# Module_AIO.net
KiCad netlist of a schematic drawn in EAGLE
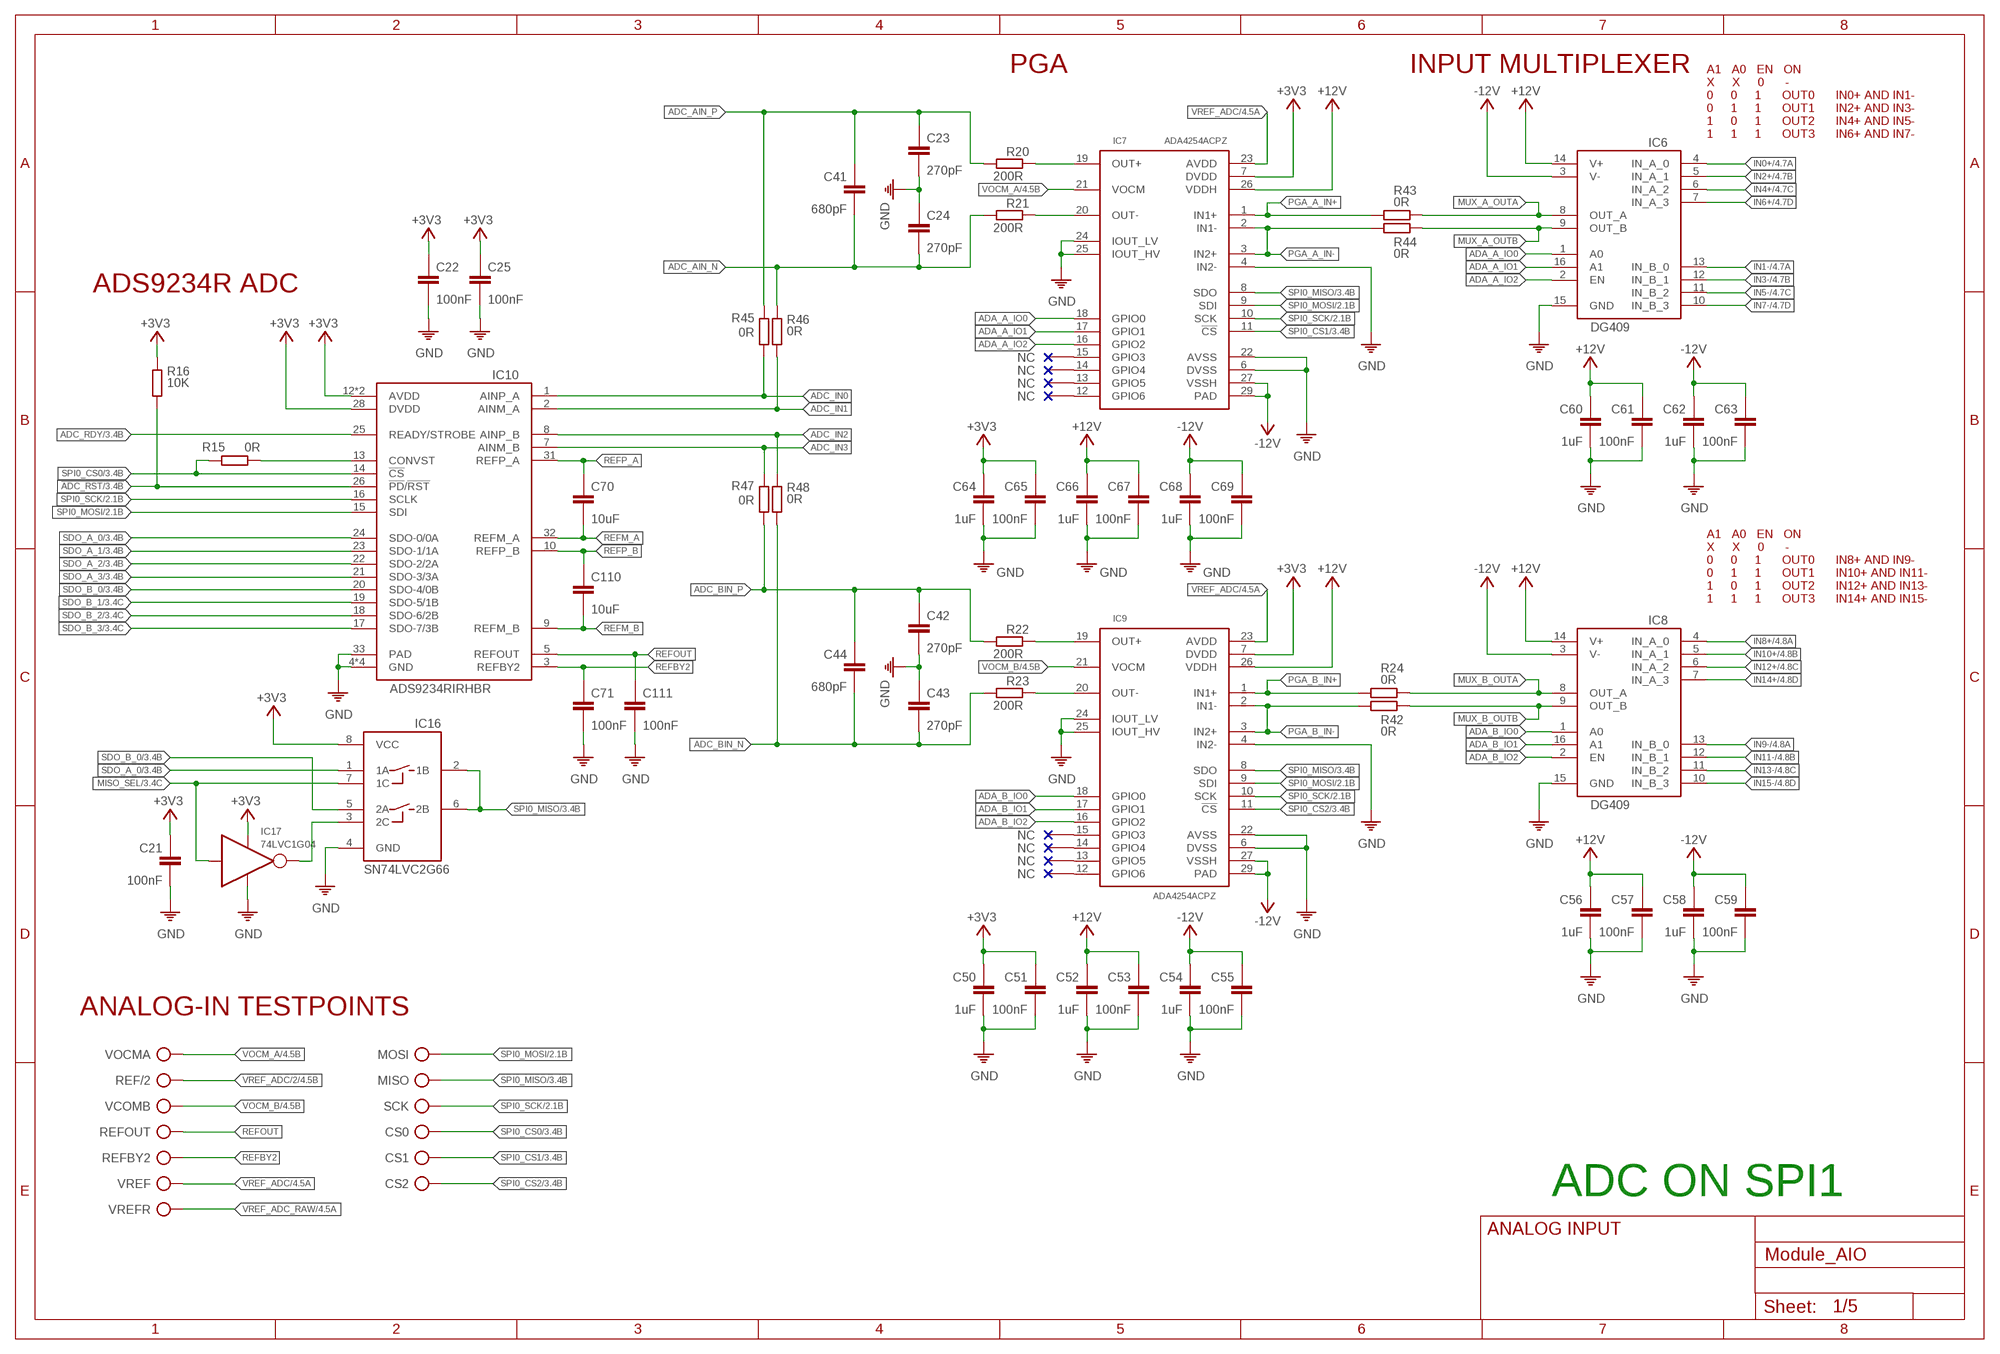
[diagram p0: schematic, sheet 1]
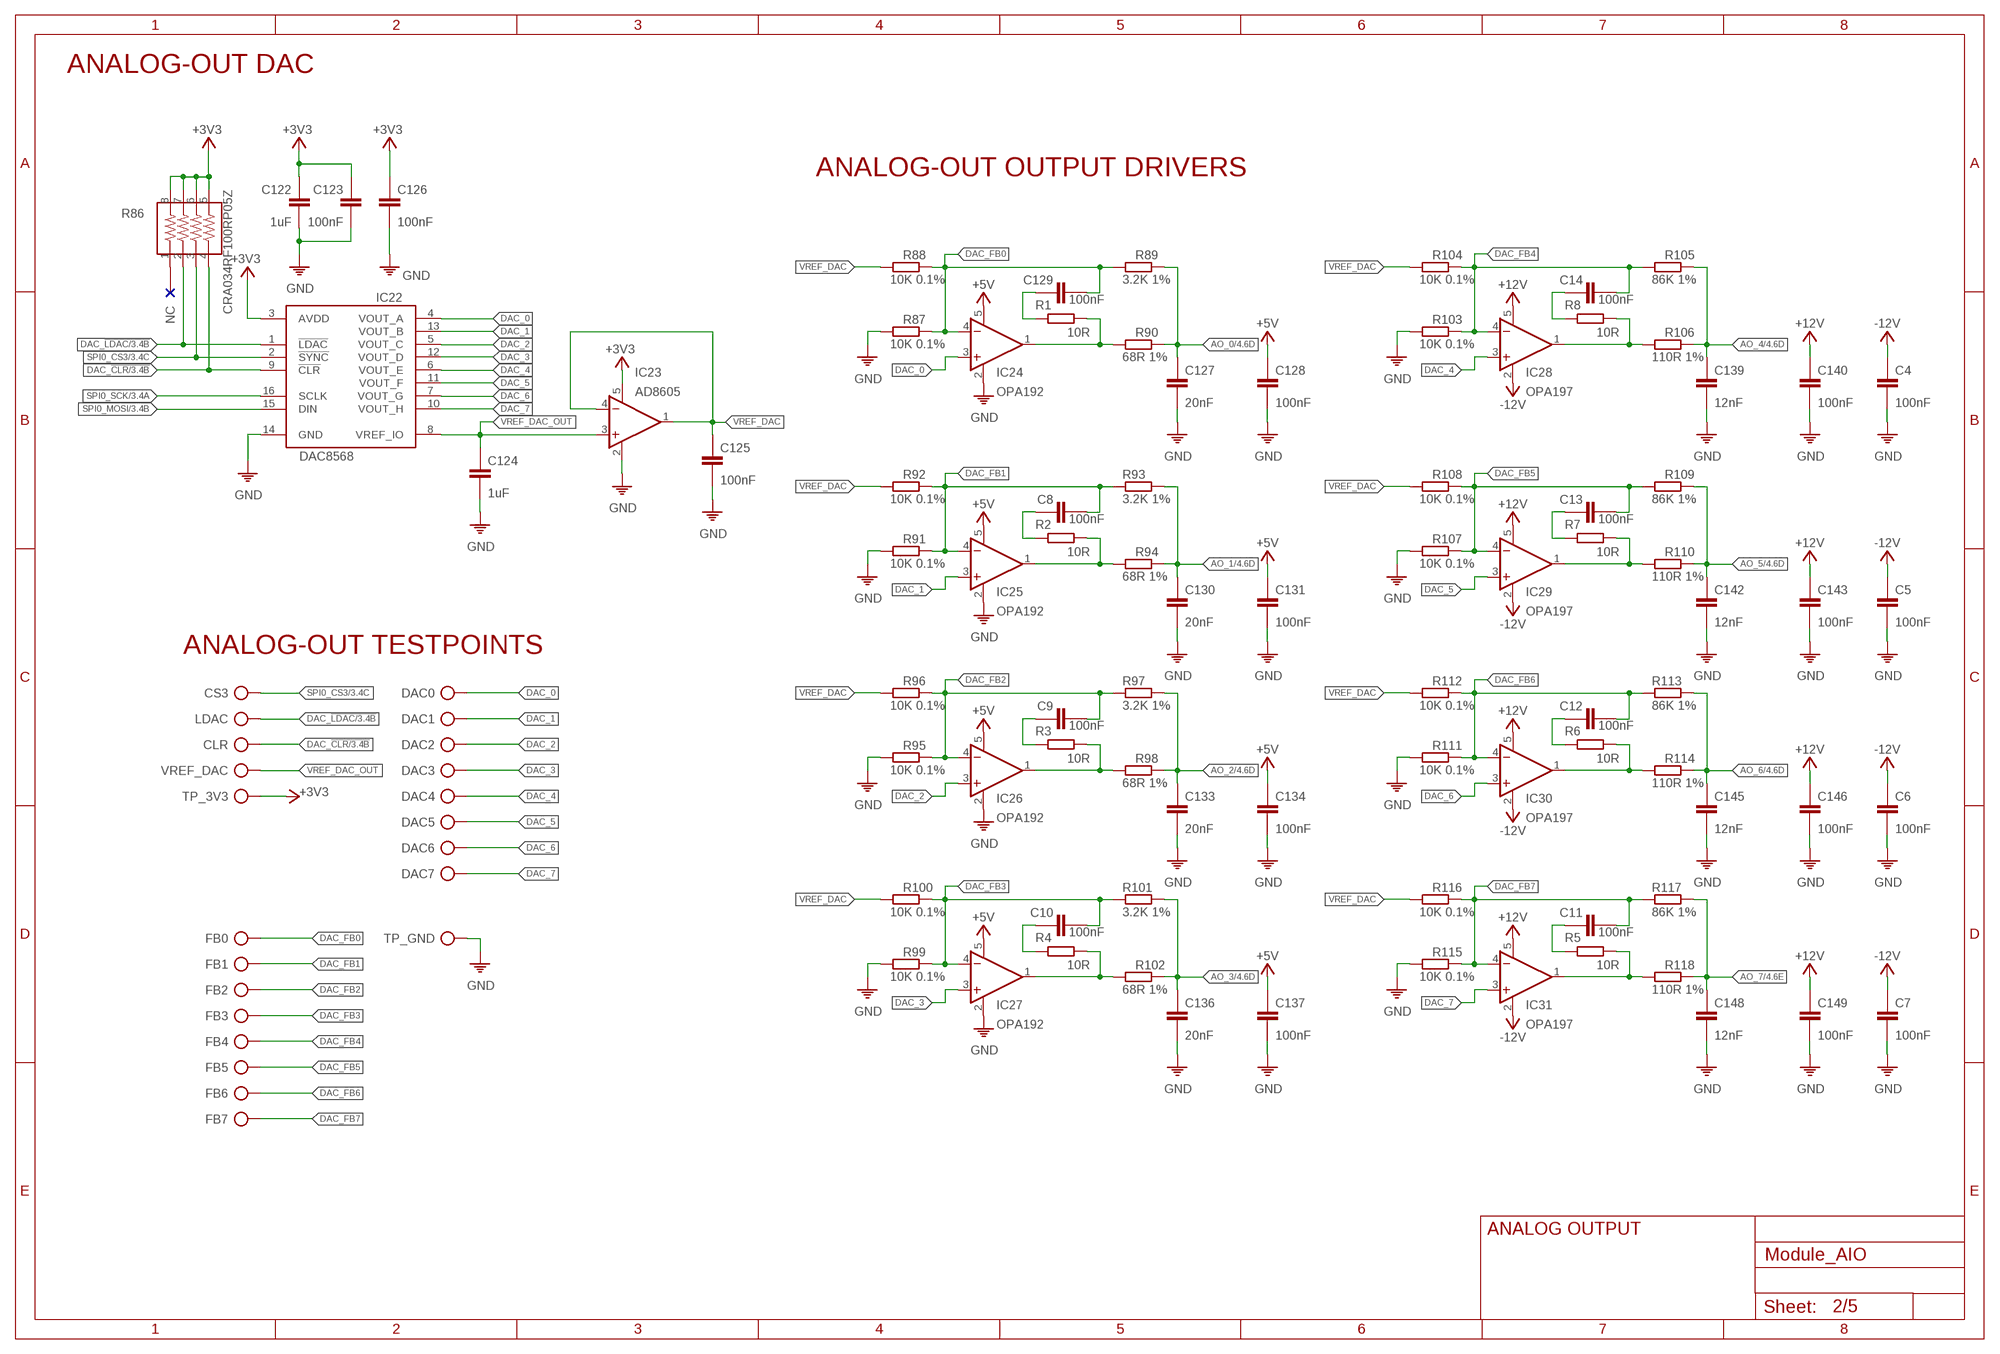
[diagram p1: schematic, sheet 2]
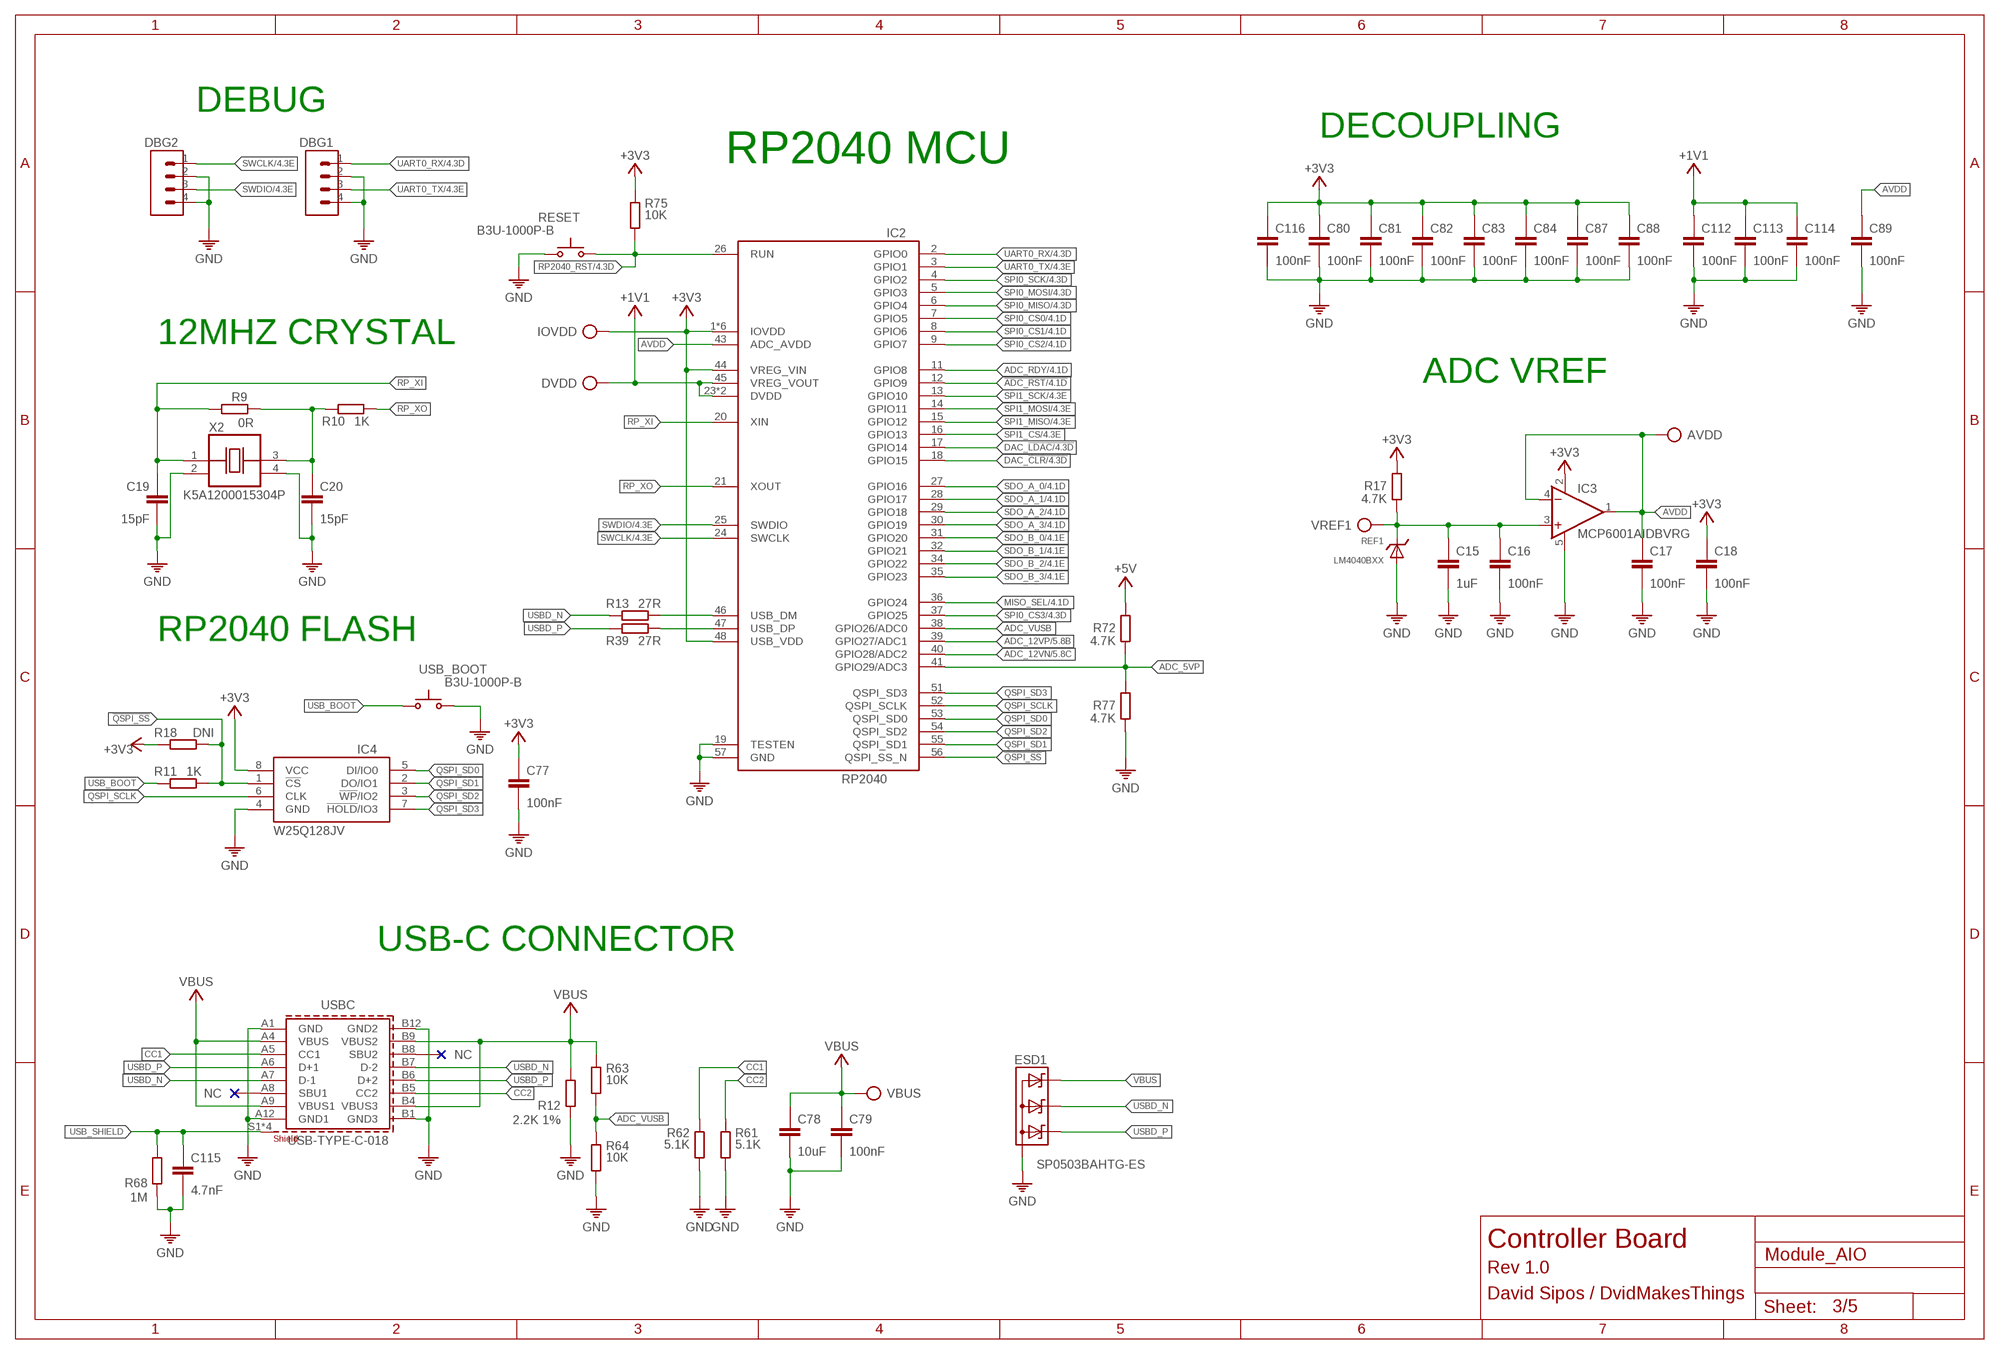
[diagram p2: schematic, sheet 3]
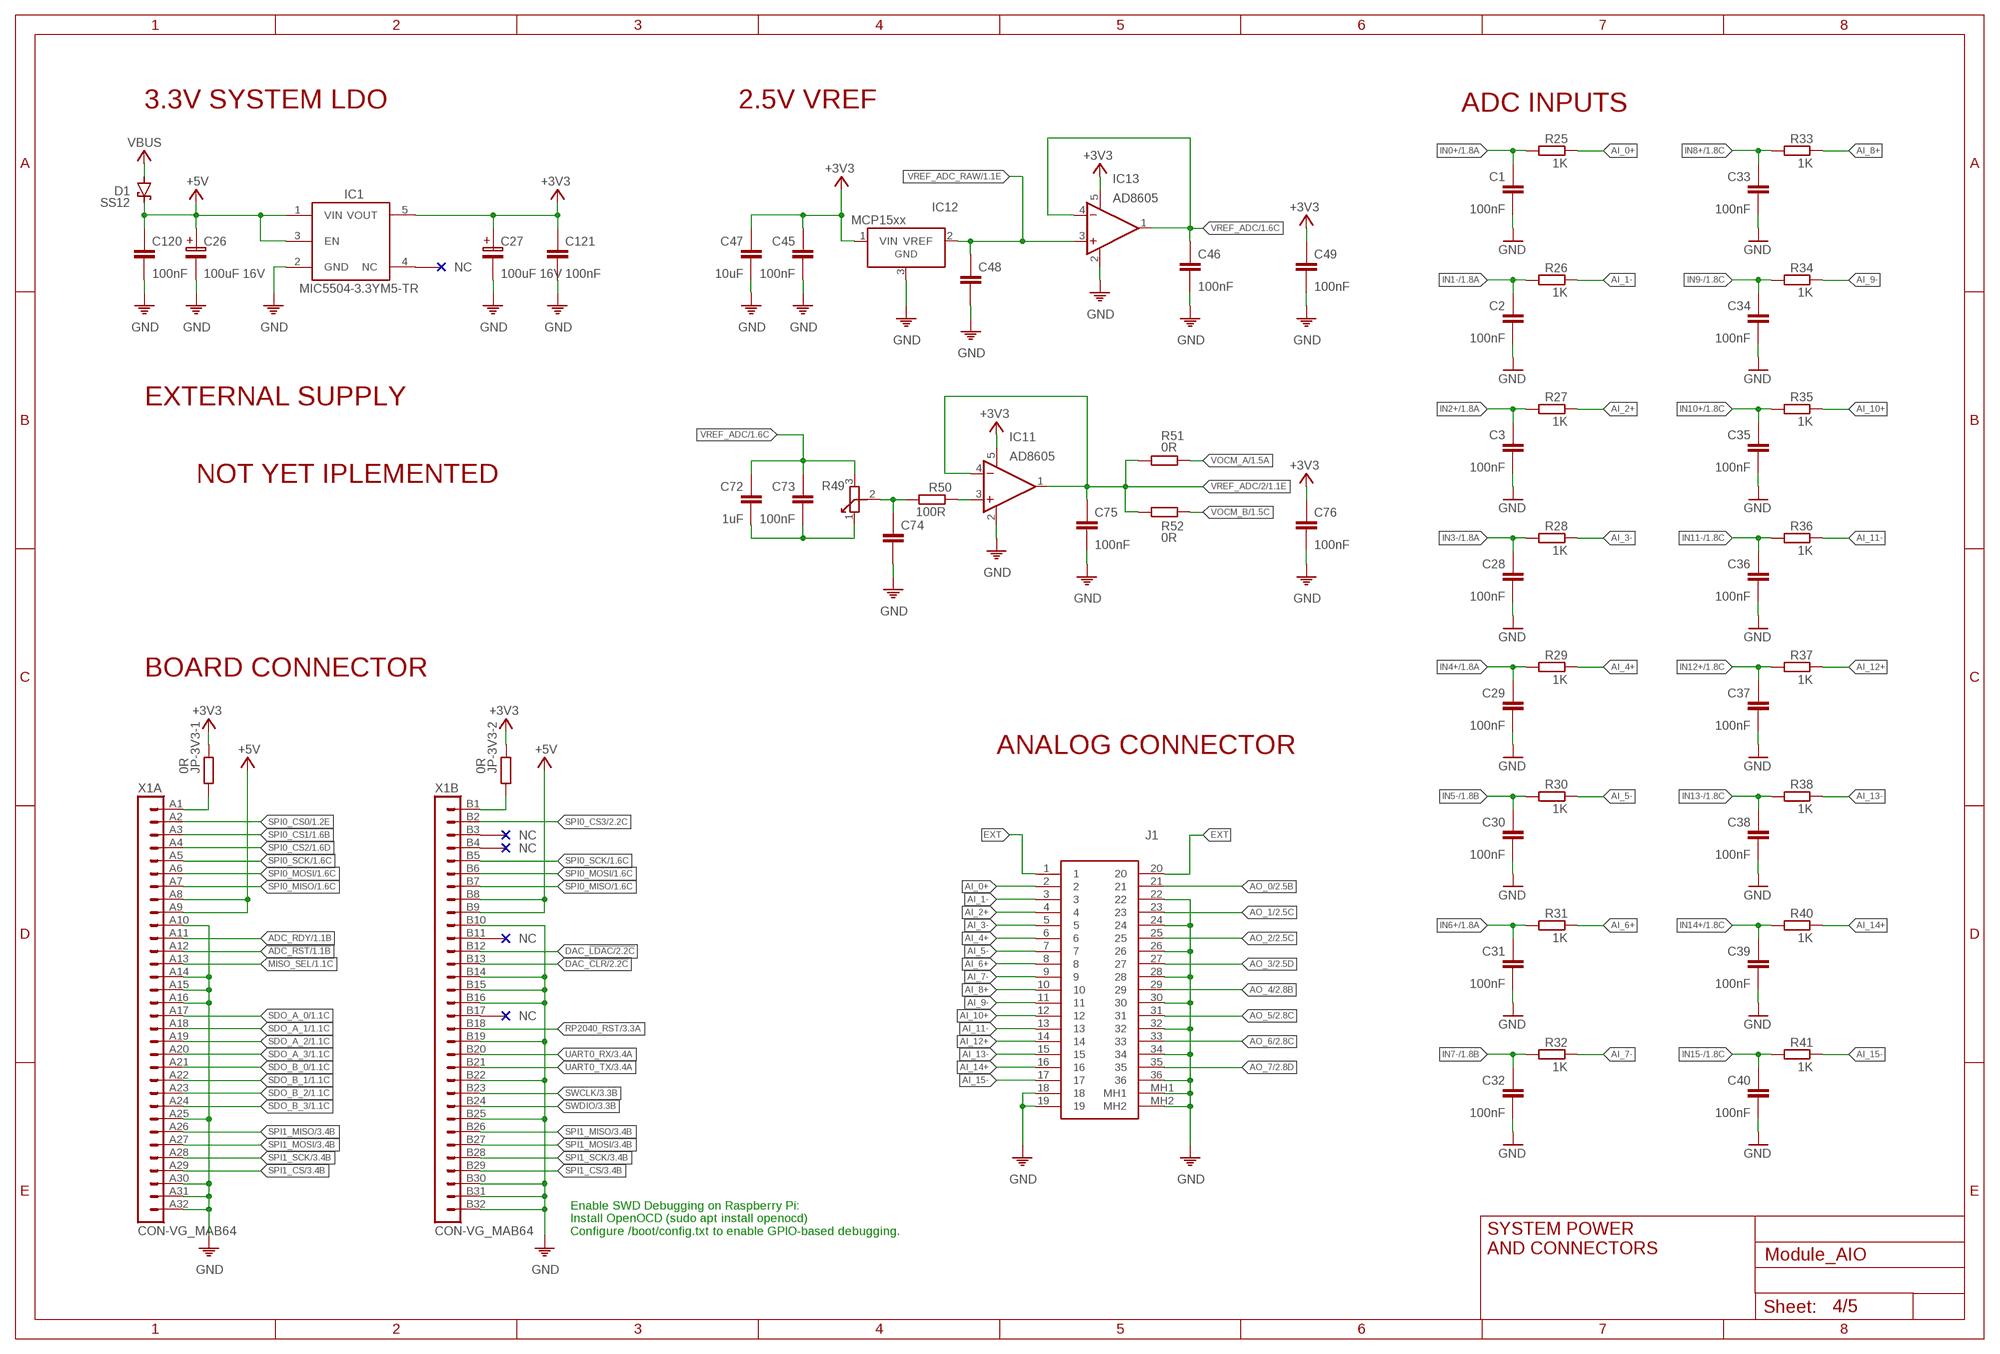
[diagram p3: schematic, sheet 4]
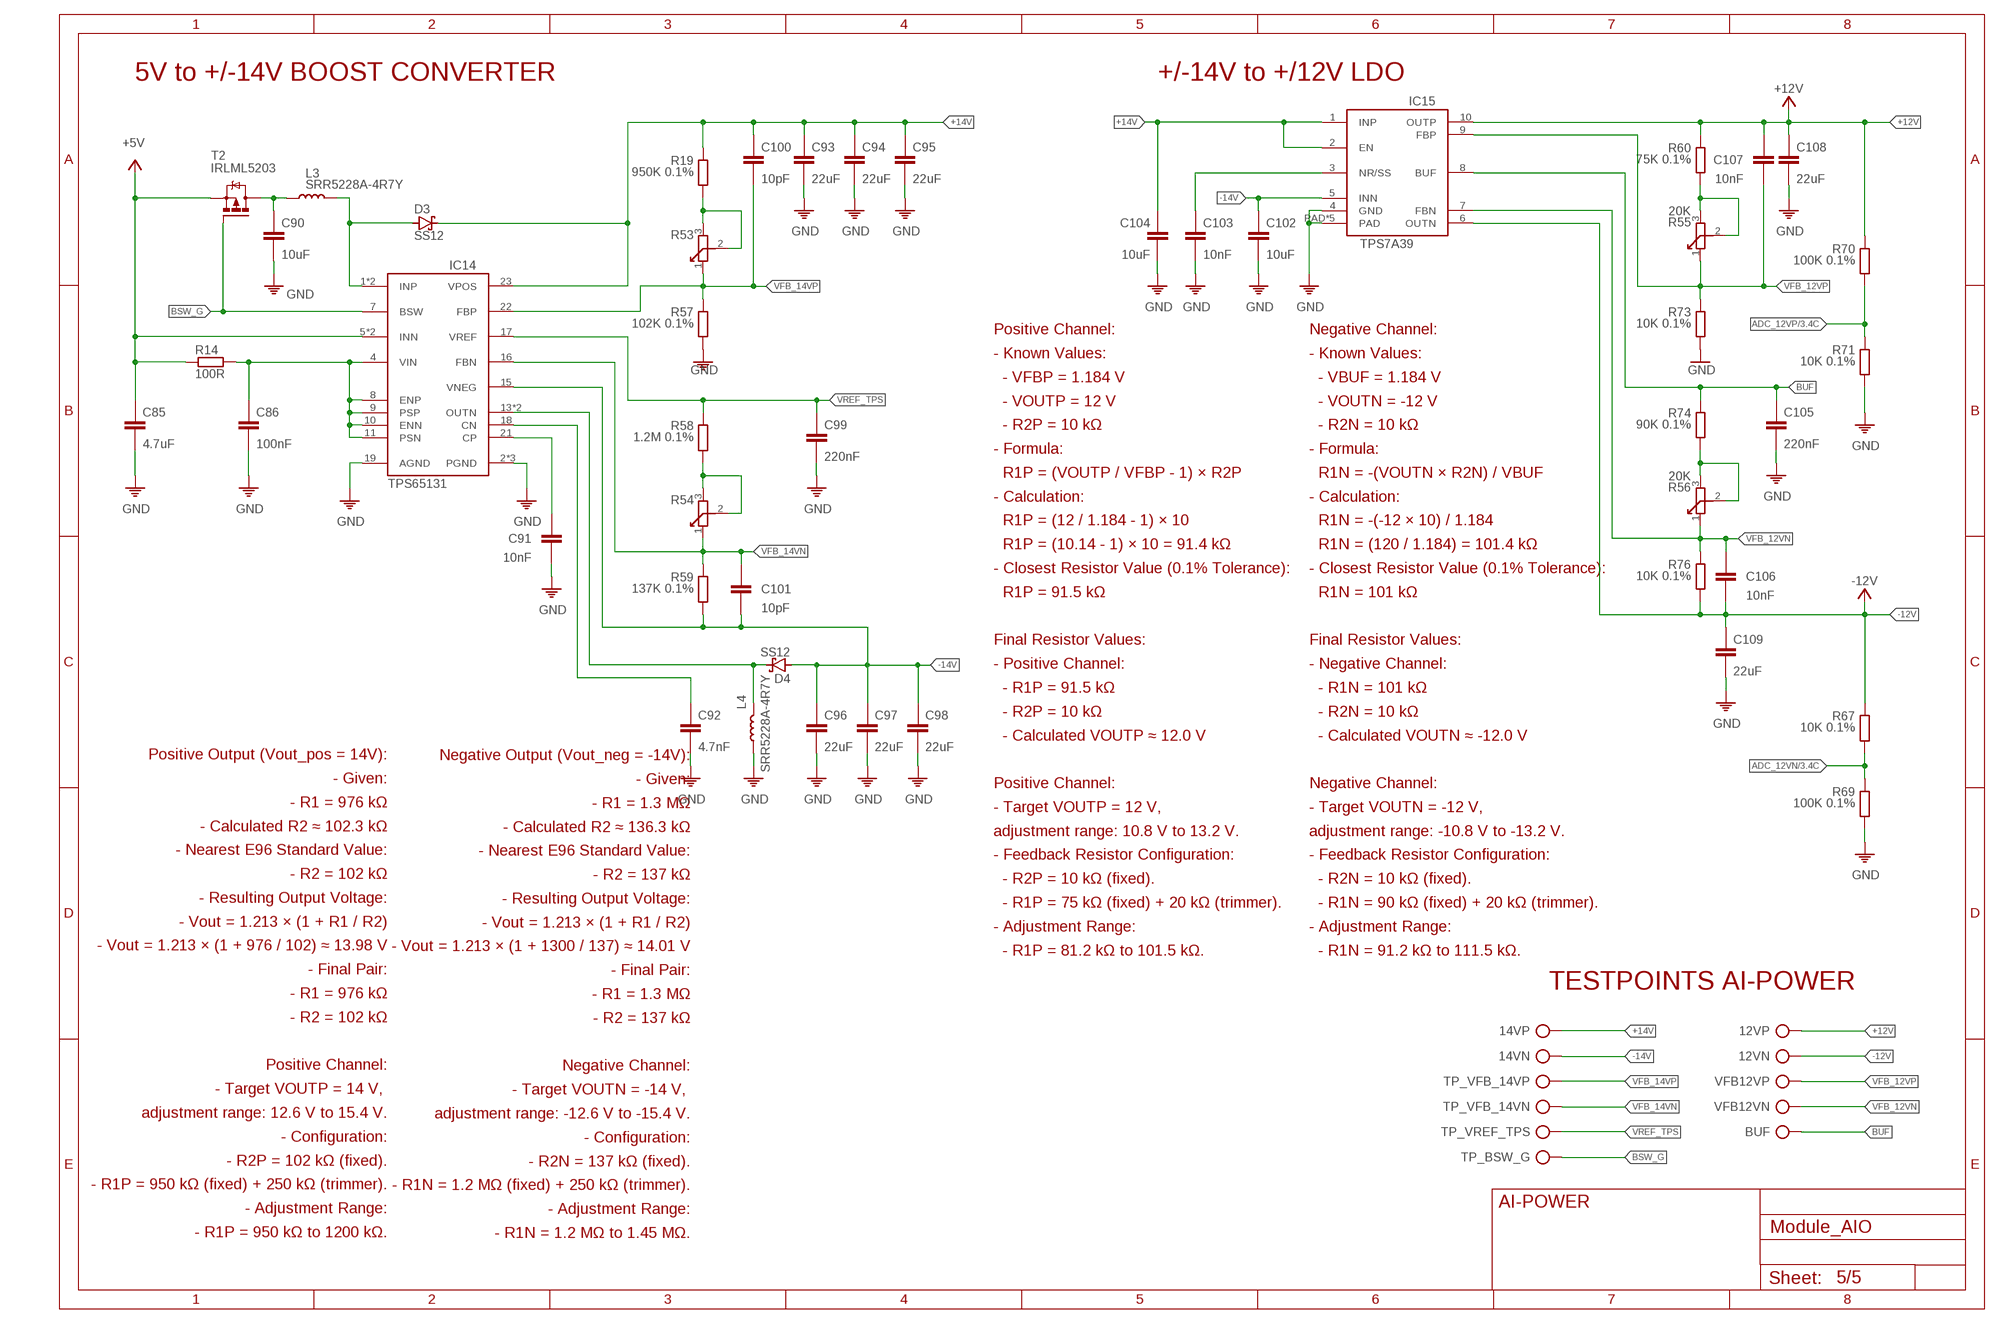
[diagram p4: schematic, sheet 5]

(export (version "E")
  (design (tool "Eeschema 10.0.6"))
  (components
    (comp (ref "C1")
      (value "100nF")
      (footprint "eagle-import:C0402")
      (libsource (lib "eagle-import") (part "C-0402"))
    )
    (comp (ref "C2")
      (value "100nF")
      (footprint "eagle-import:C0402")
      (libsource (lib "eagle-import") (part "C-0402"))
    )
    (comp (ref "C3")
      (value "100nF")
      (footprint "eagle-import:C0402")
      (libsource (lib "eagle-import") (part "C-0402"))
    )
    (comp (ref "C26")
      (value "100uF 16V")
      (footprint "eagle-import:100UF-16V")
      (libsource (lib "eagle-import") (part "CPOL"))
    )
    (comp (ref "C27")
      (value "100uF 16V")
      (footprint "eagle-import:100UF-16V")
      (libsource (lib "eagle-import") (part "CPOL"))
    )
    (comp (ref "C28")
      (value "100nF")
      (footprint "eagle-import:C0402")
      (libsource (lib "eagle-import") (part "C-0402"))
    )
    (comp (ref "C29")
      (value "100nF")
      (footprint "eagle-import:C0402")
      (libsource (lib "eagle-import") (part "C-0402"))
    )
    (comp (ref "C30")
      (value "100nF")
      (footprint "eagle-import:C0402")
      (libsource (lib "eagle-import") (part "C-0402"))
    )
    (comp (ref "C31")
      (value "100nF")
      (footprint "eagle-import:C0402")
      (libsource (lib "eagle-import") (part "C-0402"))
    )
    (comp (ref "C32")
      (value "100nF")
      (footprint "eagle-import:C0402")
      (libsource (lib "eagle-import") (part "C-0402"))
    )
    (comp (ref "C33")
      (value "100nF")
      (footprint "eagle-import:C0402")
      (libsource (lib "eagle-import") (part "C-0402"))
    )
    (comp (ref "C34")
      (value "100nF")
      (footprint "eagle-import:C0402")
      (libsource (lib "eagle-import") (part "C-0402"))
    )
    (comp (ref "C35")
      (value "100nF")
      (footprint "eagle-import:C0402")
      (libsource (lib "eagle-import") (part "C-0402"))
    )
    (comp (ref "C36")
      (value "100nF")
      (footprint "eagle-import:C0402")
      (libsource (lib "eagle-import") (part "C-0402"))
    )
    (comp (ref "C37")
      (value "100nF")
      (footprint "eagle-import:C0402")
      (libsource (lib "eagle-import") (part "C-0402"))
    )
    (comp (ref "C38")
      (value "100nF")
      (footprint "eagle-import:C0402")
      (libsource (lib "eagle-import") (part "C-0402"))
    )
    (comp (ref "C39")
      (value "100nF")
      (footprint "eagle-import:C0402")
      (libsource (lib "eagle-import") (part "C-0402"))
    )
    (comp (ref "C40")
      (value "100nF")
      (footprint "eagle-import:C0402")
      (libsource (lib "eagle-import") (part "C-0402"))
    )
    (comp (ref "C45")
      (value "100nF")
      (footprint "eagle-import:C0402")
      (libsource (lib "eagle-import") (part "C-0402"))
    )
    (comp (ref "C46")
      (value "100nF")
      (footprint "eagle-import:C0402")
      (libsource (lib "eagle-import") (part "C-0402"))
    )
    (comp (ref "C47")
      (value "10uF")
      (footprint "eagle-import:C0402")
      (libsource (lib "eagle-import") (part "C-0402"))
    )
    (comp (ref "C48")
      (value "C-0402")
      (footprint "eagle-import:C0402")
      (libsource (lib "eagle-import") (part "C-0402"))
    )
    (comp (ref "C49")
      (value "100nF")
      (footprint "eagle-import:C0402")
      (libsource (lib "eagle-import") (part "C-0402"))
    )
    (comp (ref "C72")
      (value "1uF")
      (footprint "eagle-import:C0402")
      (libsource (lib "eagle-import") (part "C-0402"))
    )
    (comp (ref "C73")
      (value "100nF")
      (footprint "eagle-import:C0402")
      (libsource (lib "eagle-import") (part "C-0402"))
    )
    (comp (ref "C74")
      (value "C-0402")
      (footprint "eagle-import:C0402")
      (libsource (lib "eagle-import") (part "C-0402"))
    )
    (comp (ref "C75")
      (value "100nF")
      (footprint "eagle-import:C0402")
      (libsource (lib "eagle-import") (part "C-0402"))
    )
    (comp (ref "C76")
      (value "100nF")
      (footprint "eagle-import:C0402")
      (libsource (lib "eagle-import") (part "C-0402"))
    )
    (comp (ref "C120")
      (value "100nF")
      (footprint "eagle-import:C0402")
      (libsource (lib "eagle-import") (part "C-0402"))
    )
    (comp (ref "C121")
      (value "100nF")
      (footprint "eagle-import:C0402")
      (libsource (lib "eagle-import") (part "C-0402"))
    )
    (comp (ref "D1")
      (value "SS12")
      (footprint "eagle-import:SMA")
      (fields
        (field (name "DIGIKEY_PART_NUMBER") "SS12FSCT-ND")
        (field (name "MANUFACTURER") "ON Semiconductor")
        (field (name "CREATED_BY") "PCBLayout.com")
      )
      (libsource (lib "eagle-import") (part "SS12"))
    )
    (comp (ref "IC1")
      (value "MIC5504-3.3YM5-TR")
      (footprint "eagle-import:SOT23-5")
      (libsource (lib "eagle-import") (part "MIC5504-3.3YM5-TR"))
    )
    (comp (ref "IC11")
      (value "AD8605")
      (footprint "eagle-import:SOT23-5")
      (libsource (lib "eagle-import") (part "AD8605"))
    )
    (comp (ref "IC12")
      (value "MCP1525T-I/TT")
      (footprint "eagle-import:SOT23")
      (libsource (lib "eagle-import") (part "MCP1525T-I/TT"))
    )
    (comp (ref "IC13")
      (value "AD8605")
      (footprint "eagle-import:SOT23-5")
      (libsource (lib "eagle-import") (part "AD8605"))
    )
    (comp (ref "J1")
      (value "N10236-52B3PC")
      (footprint "eagle-import:MDB36")
      (libsource (lib "eagle-import") (part "N10236-52B3PC"))
    )
    (comp (ref "JP-3V3-1")
      (value "0R")
      (footprint "eagle-import:0603")
      (libsource (lib "eagle-import") (part "R0603"))
    )
    (comp (ref "JP-3V3-2")
      (value "0R")
      (footprint "eagle-import:0603")
      (libsource (lib "eagle-import") (part "R0603"))
    )
    (comp (ref "R25")
      (value "1K")
      (footprint "eagle-import:0402")
      (libsource (lib "eagle-import") (part "R0402"))
    )
    (comp (ref "R26")
      (value "1K")
      (footprint "eagle-import:0402")
      (libsource (lib "eagle-import") (part "R0402"))
    )
    (comp (ref "R27")
      (value "1K")
      (footprint "eagle-import:0402")
      (libsource (lib "eagle-import") (part "R0402"))
    )
    (comp (ref "R28")
      (value "1K")
      (footprint "eagle-import:0402")
      (libsource (lib "eagle-import") (part "R0402"))
    )
    (comp (ref "R29")
      (value "1K")
      (footprint "eagle-import:0402")
      (libsource (lib "eagle-import") (part "R0402"))
    )
    (comp (ref "R30")
      (value "1K")
      (footprint "eagle-import:0402")
      (libsource (lib "eagle-import") (part "R0402"))
    )
    (comp (ref "R31")
      (value "1K")
      (footprint "eagle-import:0402")
      (libsource (lib "eagle-import") (part "R0402"))
    )
    (comp (ref "R32")
      (value "1K")
      (footprint "eagle-import:0402")
      (libsource (lib "eagle-import") (part "R0402"))
    )
    (comp (ref "R33")
      (value "1K")
      (footprint "eagle-import:0402")
      (libsource (lib "eagle-import") (part "R0402"))
    )
    (comp (ref "R34")
      (value "1K")
      (footprint "eagle-import:0402")
      (libsource (lib "eagle-import") (part "R0402"))
    )
    (comp (ref "R35")
      (value "1K")
      (footprint "eagle-import:0402")
      (libsource (lib "eagle-import") (part "R0402"))
    )
    (comp (ref "R36")
      (value "1K")
      (footprint "eagle-import:0402")
      (libsource (lib "eagle-import") (part "R0402"))
    )
    (comp (ref "R37")
      (value "1K")
      (footprint "eagle-import:0402")
      (libsource (lib "eagle-import") (part "R0402"))
    )
    (comp (ref "R38")
      (value "1K")
      (footprint "eagle-import:0402")
      (libsource (lib "eagle-import") (part "R0402"))
    )
    (comp (ref "R40")
      (value "1K")
      (footprint "eagle-import:0402")
      (libsource (lib "eagle-import") (part "R0402"))
    )
    (comp (ref "R41")
      (value "1K")
      (footprint "eagle-import:0402")
      (libsource (lib "eagle-import") (part "R0402"))
    )
    (comp (ref "R49")
      (value "R-TRIM")
      (footprint "eagle-import:TC33X")
      (libsource (lib "eagle-import") (part "R-TRIM"))
    )
    (comp (ref "R50")
      (value "100R")
      (footprint "eagle-import:0402")
      (libsource (lib "eagle-import") (part "R0402"))
    )
    (comp (ref "R51")
      (value "0R")
      (footprint "eagle-import:0603")
      (libsource (lib "eagle-import") (part "R0603"))
    )
    (comp (ref "R52")
      (value "0R")
      (footprint "eagle-import:0603")
      (libsource (lib "eagle-import") (part "R0603"))
    )
    (comp (ref "X1")
      (value "CON-VG_MAB64")
      (footprint "eagle-import:CON-VG_MAB64")
      (libsource (lib "eagle-import") (part "CON-VG_MAB64"))
    )
    (comp (ref "C21")
      (value "100nF")
      (footprint "eagle-import:C0402")
      (libsource (lib "eagle-import") (part "C-0402"))
    )
    (comp (ref "C22")
      (value "100nF")
      (footprint "eagle-import:C0402")
      (libsource (lib "eagle-import") (part "C-0402"))
    )
    (comp (ref "C23")
      (value "270pF")
      (footprint "eagle-import:C0402")
      (libsource (lib "eagle-import") (part "C-0402"))
    )
    (comp (ref "C24")
      (value "270pF")
      (footprint "eagle-import:C0402")
      (libsource (lib "eagle-import") (part "C-0402"))
    )
    (comp (ref "C25")
      (value "100nF")
      (footprint "eagle-import:C0402")
      (libsource (lib "eagle-import") (part "C-0402"))
    )
    (comp (ref "C41")
      (value "680pF")
      (footprint "eagle-import:C0402")
      (libsource (lib "eagle-import") (part "C-0402"))
    )
    (comp (ref "C42")
      (value "270pF")
      (footprint "eagle-import:C0402")
      (libsource (lib "eagle-import") (part "C-0402"))
    )
    (comp (ref "C43")
      (value "270pF")
      (footprint "eagle-import:C0402")
      (libsource (lib "eagle-import") (part "C-0402"))
    )
    (comp (ref "C44")
      (value "680pF")
      (footprint "eagle-import:C0402")
      (libsource (lib "eagle-import") (part "C-0402"))
    )
    (comp (ref "C50")
      (value "1uF")
      (footprint "eagle-import:C0402")
      (libsource (lib "eagle-import") (part "C-0402"))
    )
    (comp (ref "C51")
      (value "100nF")
      (footprint "eagle-import:C0402")
      (libsource (lib "eagle-import") (part "C-0402"))
    )
    (comp (ref "C52")
      (value "1uF")
      (footprint "eagle-import:C0402")
      (libsource (lib "eagle-import") (part "C-0402"))
    )
    (comp (ref "C53")
      (value "100nF")
      (footprint "eagle-import:C0402")
      (libsource (lib "eagle-import") (part "C-0402"))
    )
    (comp (ref "C54")
      (value "1uF")
      (footprint "eagle-import:C0402")
      (libsource (lib "eagle-import") (part "C-0402"))
    )
    (comp (ref "C55")
      (value "100nF")
      (footprint "eagle-import:C0402")
      (libsource (lib "eagle-import") (part "C-0402"))
    )
    (comp (ref "C56")
      (value "1uF")
      (footprint "eagle-import:C0402")
      (libsource (lib "eagle-import") (part "C-0402"))
    )
    (comp (ref "C57")
      (value "100nF")
      (footprint "eagle-import:C0402")
      (libsource (lib "eagle-import") (part "C-0402"))
    )
    (comp (ref "C58")
      (value "1uF")
      (footprint "eagle-import:C0402")
      (libsource (lib "eagle-import") (part "C-0402"))
    )
    (comp (ref "C59")
      (value "100nF")
      (footprint "eagle-import:C0402")
      (libsource (lib "eagle-import") (part "C-0402"))
    )
    (comp (ref "C60")
      (value "1uF")
      (footprint "eagle-import:C0402")
      (libsource (lib "eagle-import") (part "C-0402"))
    )
    (comp (ref "C61")
      (value "100nF")
      (footprint "eagle-import:C0402")
      (libsource (lib "eagle-import") (part "C-0402"))
    )
    (comp (ref "C62")
      (value "1uF")
      (footprint "eagle-import:C0402")
      (libsource (lib "eagle-import") (part "C-0402"))
    )
    (comp (ref "C63")
      (value "100nF")
      (footprint "eagle-import:C0402")
      (libsource (lib "eagle-import") (part "C-0402"))
    )
    (comp (ref "C64")
      (value "1uF")
      (footprint "eagle-import:C0402")
      (libsource (lib "eagle-import") (part "C-0402"))
    )
    (comp (ref "C65")
      (value "100nF")
      (footprint "eagle-import:C0402")
      (libsource (lib "eagle-import") (part "C-0402"))
    )
    (comp (ref "C66")
      (value "1uF")
      (footprint "eagle-import:C0402")
      (libsource (lib "eagle-import") (part "C-0402"))
    )
    (comp (ref "C67")
      (value "100nF")
      (footprint "eagle-import:C0402")
      (libsource (lib "eagle-import") (part "C-0402"))
    )
    (comp (ref "C68")
      (value "1uF")
      (footprint "eagle-import:C0402")
      (libsource (lib "eagle-import") (part "C-0402"))
    )
    (comp (ref "C69")
      (value "100nF")
      (footprint "eagle-import:C0402")
      (libsource (lib "eagle-import") (part "C-0402"))
    )
    (comp (ref "C70")
      (value "10uF")
      (footprint "eagle-import:C0402")
      (libsource (lib "eagle-import") (part "C-0402"))
    )
    (comp (ref "C71")
      (value "100nF")
      (footprint "eagle-import:C0402")
      (libsource (lib "eagle-import") (part "C-0402"))
    )
    (comp (ref "C110")
      (value "10uF")
      (footprint "eagle-import:C0402")
      (libsource (lib "eagle-import") (part "C-0402"))
    )
    (comp (ref "C111")
      (value "100nF")
      (footprint "eagle-import:C0402")
      (libsource (lib "eagle-import") (part "C-0402"))
    )
    (comp (ref "CS0") (value "TP") (footprint "eagle-import:TP") (libsource (lib "eagle-import") (part "TP")))
    (comp (ref "CS1") (value "TP") (footprint "eagle-import:TP") (libsource (lib "eagle-import") (part "TP")))
    (comp (ref "CS2") (value "TP") (footprint "eagle-import:TP") (libsource (lib "eagle-import") (part "TP")))
    (comp (ref "IC6")
      (value "DG409")
      (footprint "eagle-import:TSSOP2")
      (libsource (lib "eagle-import") (part "DG409EUE+"))
    )
    (comp (ref "IC7")
      (value "ADA4254ACPZ")
      (footprint "eagle-import:QFN50P500X500X75-29T314N")
      (libsource (lib "eagle-import") (part "ADA4254ACPZ"))
    )
    (comp (ref "IC8")
      (value "DG409")
      (footprint "eagle-import:TSSOP2")
      (libsource (lib "eagle-import") (part "DG409EUE+"))
    )
    (comp (ref "IC9")
      (value "ADA4254ACPZ")
      (footprint "eagle-import:QFN50P500X500X75-29T314N")
      (libsource (lib "eagle-import") (part "ADA4254ACPZ"))
    )
    (comp (ref "IC10")
      (value "ADS9234RIRHBR")
      (footprint "eagle-import:VQFN32-5X5")
      (libsource (lib "eagle-import") (part "ADS9234RIRHBR"))
    )
    (comp (ref "IC16")
      (value "SN74LVC2G66")
      (footprint "eagle-import:SOP50P310X90-8N")
      (libsource (lib "eagle-import") (part "SN74LVC2G66"))
    )
    (comp (ref "IC17")
      (value "74LVC1G04")
      (footprint "eagle-import:SOT95P280X145-5N")
      (libsource (lib "eagle-import") (part "74LVC1G04"))
    )
    (comp (ref "MISO")
      (value "TP")
      (footprint "eagle-import:TP")
      (libsource (lib "eagle-import") (part "TP"))
    )
    (comp (ref "MOSI")
      (value "TP")
      (footprint "eagle-import:TP")
      (libsource (lib "eagle-import") (part "TP"))
    )
    (comp (ref "R15")
      (value "0R")
      (footprint "eagle-import:0402")
      (libsource (lib "eagle-import") (part "R0402"))
    )
    (comp (ref "R16")
      (value "10K")
      (footprint "eagle-import:0402")
      (libsource (lib "eagle-import") (part "R0402"))
    )
    (comp (ref "R20")
      (value "200R")
      (footprint "eagle-import:0402")
      (libsource (lib "eagle-import") (part "R0402"))
    )
    (comp (ref "R21")
      (value "200R")
      (footprint "eagle-import:0402")
      (libsource (lib "eagle-import") (part "R0402"))
    )
    (comp (ref "R22")
      (value "200R")
      (footprint "eagle-import:0402")
      (libsource (lib "eagle-import") (part "R0402"))
    )
    (comp (ref "R23")
      (value "200R")
      (footprint "eagle-import:0402")
      (libsource (lib "eagle-import") (part "R0402"))
    )
    (comp (ref "R24")
      (value "0R")
      (footprint "eagle-import:0402")
      (libsource (lib "eagle-import") (part "R0402"))
    )
    (comp (ref "R42")
      (value "0R")
      (footprint "eagle-import:0402")
      (libsource (lib "eagle-import") (part "R0402"))
    )
    (comp (ref "R43")
      (value "0R")
      (footprint "eagle-import:0402")
      (libsource (lib "eagle-import") (part "R0402"))
    )
    (comp (ref "R44")
      (value "0R")
      (footprint "eagle-import:0402")
      (libsource (lib "eagle-import") (part "R0402"))
    )
    (comp (ref "R45")
      (value "0R")
      (footprint "eagle-import:0402")
      (libsource (lib "eagle-import") (part "R0402"))
    )
    (comp (ref "R46")
      (value "0R")
      (footprint "eagle-import:0402")
      (libsource (lib "eagle-import") (part "R0402"))
    )
    (comp (ref "R47")
      (value "0R")
      (footprint "eagle-import:0402")
      (libsource (lib "eagle-import") (part "R0402"))
    )
    (comp (ref "R48")
      (value "0R")
      (footprint "eagle-import:0402")
      (libsource (lib "eagle-import") (part "R0402"))
    )
    (comp (ref "REF/2")
      (value "TP")
      (footprint "eagle-import:TP")
      (libsource (lib "eagle-import") (part "TP"))
    )
    (comp (ref "REFBY2")
      (value "TP")
      (footprint "eagle-import:TP")
      (libsource (lib "eagle-import") (part "TP"))
    )
    (comp (ref "REFOUT")
      (value "TP")
      (footprint "eagle-import:TP")
      (libsource (lib "eagle-import") (part "TP"))
    )
    (comp (ref "SCK") (value "TP") (footprint "eagle-import:TP") (libsource (lib "eagle-import") (part "TP")))
    (comp (ref "VCOMB")
      (value "TP")
      (footprint "eagle-import:TP")
      (libsource (lib "eagle-import") (part "TP"))
    )
    (comp (ref "VOCMA")
      (value "TP")
      (footprint "eagle-import:TP")
      (libsource (lib "eagle-import") (part "TP"))
    )
    (comp (ref "VREF")
      (value "TP")
      (footprint "eagle-import:TP")
      (libsource (lib "eagle-import") (part "TP"))
    )
    (comp (ref "VREFR")
      (value "TP")
      (footprint "eagle-import:TP")
      (libsource (lib "eagle-import") (part "TP"))
    )
    (comp (ref "AVDD")
      (value "TP")
      (footprint "eagle-import:TP")
      (libsource (lib "eagle-import") (part "TP"))
    )
    (comp (ref "C15")
      (value "1uF")
      (footprint "eagle-import:C0402")
      (libsource (lib "eagle-import") (part "C-0402"))
    )
    (comp (ref "C16")
      (value "100nF")
      (footprint "eagle-import:C0402")
      (libsource (lib "eagle-import") (part "C-0402"))
    )
    (comp (ref "C17")
      (value "100nF")
      (footprint "eagle-import:C0402")
      (libsource (lib "eagle-import") (part "C-0402"))
    )
    (comp (ref "C18")
      (value "100nF")
      (footprint "eagle-import:C0402")
      (libsource (lib "eagle-import") (part "C-0402"))
    )
    (comp (ref "C19")
      (value "15pF")
      (footprint "eagle-import:C0402")
      (libsource (lib "eagle-import") (part "C-0402"))
    )
    (comp (ref "C20")
      (value "15pF")
      (footprint "eagle-import:C0402")
      (libsource (lib "eagle-import") (part "C-0402"))
    )
    (comp (ref "C77")
      (value "100nF")
      (footprint "eagle-import:C0402")
      (libsource (lib "eagle-import") (part "C-0402"))
    )
    (comp (ref "C78")
      (value "10uF")
      (footprint "eagle-import:0805")
      (libsource (lib "eagle-import") (part "C0805"))
    )
    (comp (ref "C79")
      (value "100nF")
      (footprint "eagle-import:0402")
      (libsource (lib "eagle-import") (part "C0402"))
    )
    (comp (ref "C80")
      (value "100nF")
      (footprint "eagle-import:C0402")
      (libsource (lib "eagle-import") (part "C-0402"))
    )
    (comp (ref "C81")
      (value "100nF")
      (footprint "eagle-import:C0402")
      (libsource (lib "eagle-import") (part "C-0402"))
    )
    (comp (ref "C82")
      (value "100nF")
      (footprint "eagle-import:C0402")
      (libsource (lib "eagle-import") (part "C-0402"))
    )
    (comp (ref "C83")
      (value "100nF")
      (footprint "eagle-import:C0402")
      (libsource (lib "eagle-import") (part "C-0402"))
    )
    (comp (ref "C84")
      (value "100nF")
      (footprint "eagle-import:C0402")
      (libsource (lib "eagle-import") (part "C-0402"))
    )
    (comp (ref "C87")
      (value "100nF")
      (footprint "eagle-import:C0402")
      (libsource (lib "eagle-import") (part "C-0402"))
    )
    (comp (ref "C88")
      (value "100nF")
      (footprint "eagle-import:C0402")
      (libsource (lib "eagle-import") (part "C-0402"))
    )
    (comp (ref "C89")
      (value "100nF")
      (footprint "eagle-import:C0402")
      (libsource (lib "eagle-import") (part "C-0402"))
    )
    (comp (ref "C112")
      (value "100nF")
      (footprint "eagle-import:C0402")
      (libsource (lib "eagle-import") (part "C-0402"))
    )
    (comp (ref "C113")
      (value "100nF")
      (footprint "eagle-import:C0402")
      (libsource (lib "eagle-import") (part "C-0402"))
    )
    (comp (ref "C114")
      (value "100nF")
      (footprint "eagle-import:C0402")
      (libsource (lib "eagle-import") (part "C-0402"))
    )
    (comp (ref "C115")
      (value "4.7nF")
      (footprint "eagle-import:0402")
      (libsource (lib "eagle-import") (part "C0402"))
    )
    (comp (ref "C116")
      (value "100nF")
      (footprint "eagle-import:C0402")
      (libsource (lib "eagle-import") (part "C-0402"))
    )
    (comp (ref "DBG1")
      (value "CON-1X4")
      (footprint "eagle-import:1X4")
      (libsource (lib "eagle-import") (part "CON-1X4"))
    )
    (comp (ref "DBG2")
      (value "CON-1X4")
      (footprint "eagle-import:1X4")
      (libsource (lib "eagle-import") (part "CON-1X4"))
    )
    (comp (ref "DVDD")
      (value "TP")
      (footprint "eagle-import:TP")
      (libsource (lib "eagle-import") (part "TP"))
    )
    (comp (ref "ESD1")
      (value "SP0503BAHTG-ES")
      (footprint "eagle-import:SOT143")
      (libsource (lib "eagle-import") (part "SP0503BAHT"))
    )
    (comp (ref "IC2")
      (value "RP2040")
      (footprint "eagle-import:QFN40P700X700X100-57T510")
      (libsource (lib "eagle-import") (part "RP2040"))
    )
    (comp (ref "IC3")
      (value "MCP6001AIDBVRG")
      (footprint "eagle-import:SOT23-5")
      (libsource (lib "eagle-import") (part "MCP6001RT"))
    )
    (comp (ref "IC4")
      (value "W25Q128JVPIQ")
      (footprint "eagle-import:SON127P600X500X75-8N")
      (libsource (lib "eagle-import") (part "W25Q128JVP"))
    )
    (comp (ref "IOVDD")
      (value "TP")
      (footprint "eagle-import:TP")
      (libsource (lib "eagle-import") (part "TP"))
    )
    (comp (ref "R9")
      (value "0R")
      (footprint "eagle-import:0402")
      (libsource (lib "eagle-import") (part "R0402"))
    )
    (comp (ref "R10")
      (value "1K")
      (footprint "eagle-import:0402")
      (libsource (lib "eagle-import") (part "R0402"))
    )
    (comp (ref "R11")
      (value "1K")
      (footprint "eagle-import:0402")
      (libsource (lib "eagle-import") (part "R0402"))
    )
    (comp (ref "R12")
      (value "2.2K 1%")
      (footprint "eagle-import:0402")
      (libsource (lib "eagle-import") (part "ds_passive_46685041_R0402"))
    )
    (comp (ref "R13")
      (value "27R")
      (footprint "eagle-import:0402")
      (libsource (lib "eagle-import") (part "R0402"))
    )
    (comp (ref "R17")
      (value "4.7K")
      (footprint "eagle-import:0402")
      (libsource (lib "eagle-import") (part "R0402"))
    )
    (comp (ref "R18")
      (value "DNI")
      (footprint "eagle-import:0402")
      (libsource (lib "eagle-import") (part "R0402"))
    )
    (comp (ref "R39")
      (value "27R")
      (footprint "eagle-import:0402")
      (libsource (lib "eagle-import") (part "R0402"))
    )
    (comp (ref "R61")
      (value "5.1K")
      (footprint "eagle-import:0402")
      (libsource (lib "eagle-import") (part "ds_passive_46685041_R0402"))
    )
    (comp (ref "R62")
      (value "5.1K")
      (footprint "eagle-import:0402")
      (libsource (lib "eagle-import") (part "ds_passive_46685041_R0402"))
    )
    (comp (ref "R63")
      (value "10K")
      (footprint "eagle-import:0402")
      (libsource (lib "eagle-import") (part "ds_passive_46685041_R0402"))
    )
    (comp (ref "R64")
      (value "10K")
      (footprint "eagle-import:0402")
      (libsource (lib "eagle-import") (part "ds_passive_46685041_R0402"))
    )
    (comp (ref "R68")
      (value "1M")
      (footprint "eagle-import:0402")
      (libsource (lib "eagle-import") (part "ds_passive_46685041_R0402"))
    )
    (comp (ref "R72")
      (value "4.7K")
      (footprint "eagle-import:0402")
      (libsource (lib "eagle-import") (part "R0402"))
    )
    (comp (ref "R75")
      (value "10K")
      (footprint "eagle-import:0402")
      (libsource (lib "eagle-import") (part "ds_passive_46685041_R0402"))
    )
    (comp (ref "R77")
      (value "4.7K")
      (footprint "eagle-import:0402")
      (libsource (lib "eagle-import") (part "R0402"))
    )
    (comp (ref "REF1")
      (value "LM4040BXX")
      (footprint "eagle-import:SOT23")
      (libsource (lib "eagle-import") (part "LM4040BXX"))
    )
    (comp (ref "RESET")
      (value "B3U-1000P-B")
      (footprint "eagle-import:SWITCH-OMRON_B3U-1000P")
      (libsource (lib "eagle-import") (part "SWITCH-OMRON_B3U-1000P"))
    )
    (comp (ref "USBC")
      (value "USB-TYPE-C-018")
      (footprint "eagle-import:629722000214")
      (libsource (lib "eagle-import") (part "629722000214"))
    )
    (comp (ref "USB_BOOT")
      (value "B3U-1000P-B")
      (footprint "eagle-import:SWITCH-OMRON_B3U-1000P")
      (libsource (lib "eagle-import") (part "SWITCH-OMRON_B3U-1000P"))
    )
    (comp (ref "VBUS")
      (value "TP")
      (footprint "eagle-import:TP")
      (libsource (lib "eagle-import") (part "TP"))
    )
    (comp (ref "VREF1")
      (value "TP")
      (footprint "eagle-import:TP")
      (libsource (lib "eagle-import") (part "TP"))
    )
    (comp (ref "X2")
      (value "K5A1200015304P")
      (footprint "eagle-import:OSCCC500X320X130")
      (libsource (lib "eagle-import") (part "CRYSTAL"))
    )
    (comp (ref "C4")
      (value "100nF")
      (footprint "eagle-import:C0402")
      (libsource (lib "eagle-import") (part "C-0402"))
    )
    (comp (ref "C5")
      (value "100nF")
      (footprint "eagle-import:C0402")
      (libsource (lib "eagle-import") (part "C-0402"))
    )
    (comp (ref "C6")
      (value "100nF")
      (footprint "eagle-import:C0402")
      (libsource (lib "eagle-import") (part "C-0402"))
    )
    (comp (ref "C7")
      (value "100nF")
      (footprint "eagle-import:C0402")
      (libsource (lib "eagle-import") (part "C-0402"))
    )
    (comp (ref "C8")
      (value "100nF")
      (footprint "eagle-import:C0402")
      (libsource (lib "eagle-import") (part "C-0402"))
    )
    (comp (ref "C9")
      (value "100nF")
      (footprint "eagle-import:C0402")
      (libsource (lib "eagle-import") (part "C-0402"))
    )
    (comp (ref "C10")
      (value "100nF")
      (footprint "eagle-import:C0402")
      (libsource (lib "eagle-import") (part "C-0402"))
    )
    (comp (ref "C11")
      (value "100nF")
      (footprint "eagle-import:C0402")
      (libsource (lib "eagle-import") (part "C-0402"))
    )
    (comp (ref "C12")
      (value "100nF")
      (footprint "eagle-import:C0402")
      (libsource (lib "eagle-import") (part "C-0402"))
    )
    (comp (ref "C13")
      (value "100nF")
      (footprint "eagle-import:C0402")
      (libsource (lib "eagle-import") (part "C-0402"))
    )
    (comp (ref "C14")
      (value "100nF")
      (footprint "eagle-import:C0402")
      (libsource (lib "eagle-import") (part "C-0402"))
    )
    (comp (ref "C122")
      (value "1uF")
      (footprint "eagle-import:C0402")
      (libsource (lib "eagle-import") (part "C-0402"))
    )
    (comp (ref "C123")
      (value "100nF")
      (footprint "eagle-import:C0402")
      (libsource (lib "eagle-import") (part "C-0402"))
    )
    (comp (ref "C124")
      (value "1uF")
      (footprint "eagle-import:C0402")
      (libsource (lib "eagle-import") (part "C-0402"))
    )
    (comp (ref "C125")
      (value "100nF")
      (footprint "eagle-import:C0402")
      (libsource (lib "eagle-import") (part "C-0402"))
    )
    (comp (ref "C126")
      (value "100nF")
      (footprint "eagle-import:C0402")
      (libsource (lib "eagle-import") (part "C-0402"))
    )
    (comp (ref "C127")
      (value "20nF")
      (footprint "eagle-import:C0402")
      (libsource (lib "eagle-import") (part "C-0402"))
    )
    (comp (ref "C128")
      (value "100nF")
      (footprint "eagle-import:C0402")
      (libsource (lib "eagle-import") (part "C-0402"))
    )
    (comp (ref "C129")
      (value "100nF")
      (footprint "eagle-import:C0402")
      (libsource (lib "eagle-import") (part "C-0402"))
    )
    (comp (ref "C130")
      (value "20nF")
      (footprint "eagle-import:C0402")
      (libsource (lib "eagle-import") (part "C-0402"))
    )
    (comp (ref "C131")
      (value "100nF")
      (footprint "eagle-import:C0402")
      (libsource (lib "eagle-import") (part "C-0402"))
    )
    (comp (ref "C133")
      (value "20nF")
      (footprint "eagle-import:C0402")
      (libsource (lib "eagle-import") (part "C-0402"))
    )
    (comp (ref "C134")
      (value "100nF")
      (footprint "eagle-import:C0402")
      (libsource (lib "eagle-import") (part "C-0402"))
    )
    (comp (ref "C136")
      (value "20nF")
      (footprint "eagle-import:C0402")
      (libsource (lib "eagle-import") (part "C-0402"))
    )
    (comp (ref "C137")
      (value "100nF")
      (footprint "eagle-import:C0402")
      (libsource (lib "eagle-import") (part "C-0402"))
    )
    (comp (ref "C139")
      (value "12nF")
      (footprint "eagle-import:C0402")
      (libsource (lib "eagle-import") (part "C-0402"))
    )
    (comp (ref "C140")
      (value "100nF")
      (footprint "eagle-import:C0402")
      (libsource (lib "eagle-import") (part "C-0402"))
    )
    (comp (ref "C142")
      (value "12nF")
      (footprint "eagle-import:C0402")
      (libsource (lib "eagle-import") (part "C-0402"))
    )
    (comp (ref "C143")
      (value "100nF")
      (footprint "eagle-import:C0402")
      (libsource (lib "eagle-import") (part "C-0402"))
    )
    (comp (ref "C145")
      (value "12nF")
      (footprint "eagle-import:C0402")
      (libsource (lib "eagle-import") (part "C-0402"))
    )
    (comp (ref "C146")
      (value "100nF")
      (footprint "eagle-import:C0402")
      (libsource (lib "eagle-import") (part "C-0402"))
    )
    (comp (ref "C148")
      (value "12nF")
      (footprint "eagle-import:C0402")
      (libsource (lib "eagle-import") (part "C-0402"))
    )
    (comp (ref "C149")
      (value "100nF")
      (footprint "eagle-import:C0402")
      (libsource (lib "eagle-import") (part "C-0402"))
    )
    (comp (ref "CLR") (value "TP") (footprint "eagle-import:TP") (libsource (lib "eagle-import") (part "TP")))
    (comp (ref "CS3") (value "TP") (footprint "eagle-import:TP") (libsource (lib "eagle-import") (part "TP")))
    (comp (ref "DAC0")
      (value "TP")
      (footprint "eagle-import:TP")
      (libsource (lib "eagle-import") (part "TP"))
    )
    (comp (ref "DAC1")
      (value "TP")
      (footprint "eagle-import:TP")
      (libsource (lib "eagle-import") (part "TP"))
    )
    (comp (ref "DAC2")
      (value "TP")
      (footprint "eagle-import:TP")
      (libsource (lib "eagle-import") (part "TP"))
    )
    (comp (ref "DAC3")
      (value "TP")
      (footprint "eagle-import:TP")
      (libsource (lib "eagle-import") (part "TP"))
    )
    (comp (ref "DAC4")
      (value "TP")
      (footprint "eagle-import:TP")
      (libsource (lib "eagle-import") (part "TP"))
    )
    (comp (ref "DAC5")
      (value "TP")
      (footprint "eagle-import:TP")
      (libsource (lib "eagle-import") (part "TP"))
    )
    (comp (ref "DAC6")
      (value "TP")
      (footprint "eagle-import:TP")
      (libsource (lib "eagle-import") (part "TP"))
    )
    (comp (ref "DAC7")
      (value "TP")
      (footprint "eagle-import:TP")
      (libsource (lib "eagle-import") (part "TP"))
    )
    (comp (ref "FB0") (value "TP") (footprint "eagle-import:TP") (libsource (lib "eagle-import") (part "TP")))
    (comp (ref "FB1") (value "TP") (footprint "eagle-import:TP") (libsource (lib "eagle-import") (part "TP")))
    (comp (ref "FB2") (value "TP") (footprint "eagle-import:TP") (libsource (lib "eagle-import") (part "TP")))
    (comp (ref "FB3") (value "TP") (footprint "eagle-import:TP") (libsource (lib "eagle-import") (part "TP")))
    (comp (ref "FB4") (value "TP") (footprint "eagle-import:TP") (libsource (lib "eagle-import") (part "TP")))
    (comp (ref "FB5") (value "TP") (footprint "eagle-import:TP") (libsource (lib "eagle-import") (part "TP")))
    (comp (ref "FB6") (value "TP") (footprint "eagle-import:TP") (libsource (lib "eagle-import") (part "TP")))
    (comp (ref "FB7") (value "TP") (footprint "eagle-import:TP") (libsource (lib "eagle-import") (part "TP")))
    (comp (ref "IC22")
      (value "DAC8568")
      (footprint "eagle-import:TSSOP16")
      (libsource (lib "eagle-import") (part "DAC8568"))
    )
    (comp (ref "IC23")
      (value "AD8605")
      (footprint "eagle-import:SOT23-5")
      (libsource (lib "eagle-import") (part "AD8605"))
    )
    (comp (ref "IC24")
      (value "OPA192")
      (footprint "eagle-import:SOT23-5")
      (libsource (lib "eagle-import") (part "OPA192"))
    )
    (comp (ref "IC25")
      (value "OPA192")
      (footprint "eagle-import:SOT23-5")
      (libsource (lib "eagle-import") (part "OPA192"))
    )
    (comp (ref "IC26")
      (value "OPA192")
      (footprint "eagle-import:SOT23-5")
      (libsource (lib "eagle-import") (part "OPA192"))
    )
    (comp (ref "IC27")
      (value "OPA192")
      (footprint "eagle-import:SOT23-5")
      (libsource (lib "eagle-import") (part "OPA192"))
    )
    (comp (ref "IC28")
      (value "OPA197")
      (footprint "eagle-import:SOT23-5")
      (libsource (lib "eagle-import") (part "OPA197"))
    )
    (comp (ref "IC29")
      (value "OPA197")
      (footprint "eagle-import:SOT23-5")
      (libsource (lib "eagle-import") (part "OPA197"))
    )
    (comp (ref "IC30")
      (value "OPA197")
      (footprint "eagle-import:SOT23-5")
      (libsource (lib "eagle-import") (part "OPA197"))
    )
    (comp (ref "IC31")
      (value "OPA197")
      (footprint "eagle-import:SOT23-5")
      (libsource (lib "eagle-import") (part "OPA197"))
    )
    (comp (ref "LDAC")
      (value "TP")
      (footprint "eagle-import:TP")
      (libsource (lib "eagle-import") (part "TP"))
    )
    (comp (ref "R1")
      (value "10R")
      (footprint "eagle-import:0402")
      (libsource (lib "eagle-import") (part "R0402"))
    )
    (comp (ref "R2")
      (value "10R")
      (footprint "eagle-import:0402")
      (libsource (lib "eagle-import") (part "R0402"))
    )
    (comp (ref "R3")
      (value "10R")
      (footprint "eagle-import:0402")
      (libsource (lib "eagle-import") (part "R0402"))
    )
    (comp (ref "R4")
      (value "10R")
      (footprint "eagle-import:0402")
      (libsource (lib "eagle-import") (part "R0402"))
    )
    (comp (ref "R5")
      (value "10R")
      (footprint "eagle-import:0402")
      (libsource (lib "eagle-import") (part "R0402"))
    )
    (comp (ref "R6")
      (value "10R")
      (footprint "eagle-import:0402")
      (libsource (lib "eagle-import") (part "R0402"))
    )
    (comp (ref "R7")
      (value "10R")
      (footprint "eagle-import:0402")
      (libsource (lib "eagle-import") (part "R0402"))
    )
    (comp (ref "R8")
      (value "10R")
      (footprint "eagle-import:0402")
      (libsource (lib "eagle-import") (part "R0402"))
    )
    (comp (ref "R86")
      (value "CRA034RF100RP05Z")
      (footprint "eagle-import:YC164-JR-0733RL")
      (fields
        (field (name "MANUFACTURER") "Yageo")
        (field (name "MPN") "YC164-JR-0733RL")
        (field (name "CREATED_BY") "PCBLayout.com")
      )
      (libsource (lib "eagle-import") (part "YC164-JR-0733RL"))
    )
    (comp (ref "R87")
      (value "10K 0.1%")
      (footprint "eagle-import:0402")
      (libsource (lib "eagle-import") (part "R0402"))
    )
    (comp (ref "R88")
      (value "10K 0.1%")
      (footprint "eagle-import:0402")
      (libsource (lib "eagle-import") (part "R0402"))
    )
    (comp (ref "R89")
      (value "3.2K 1%")
      (footprint "eagle-import:0402")
      (libsource (lib "eagle-import") (part "R0402"))
    )
    (comp (ref "R90")
      (value "68R 1%")
      (footprint "eagle-import:0402")
      (libsource (lib "eagle-import") (part "R0402"))
    )
    (comp (ref "R91")
      (value "10K 0.1%")
      (footprint "eagle-import:0402")
      (libsource (lib "eagle-import") (part "R0402"))
    )
    (comp (ref "R92")
      (value "10K 0.1%")
      (footprint "eagle-import:0402")
      (libsource (lib "eagle-import") (part "R0402"))
    )
    (comp (ref "R93")
      (value "3.2K 1%")
      (footprint "eagle-import:0402")
      (libsource (lib "eagle-import") (part "R0402"))
    )
    (comp (ref "R94")
      (value "68R 1%")
      (footprint "eagle-import:0402")
      (libsource (lib "eagle-import") (part "R0402"))
    )
    (comp (ref "R95")
      (value "10K 0.1%")
      (footprint "eagle-import:0402")
      (libsource (lib "eagle-import") (part "R0402"))
    )
    (comp (ref "R96")
      (value "10K 0.1%")
      (footprint "eagle-import:0402")
      (libsource (lib "eagle-import") (part "R0402"))
    )
    (comp (ref "R97")
      (value "3.2K 1%")
      (footprint "eagle-import:0402")
      (libsource (lib "eagle-import") (part "R0402"))
    )
    (comp (ref "R98")
      (value "68R 1%")
      (footprint "eagle-import:0402")
      (libsource (lib "eagle-import") (part "R0402"))
    )
    (comp (ref "R99")
      (value "10K 0.1%")
      (footprint "eagle-import:0402")
      (libsource (lib "eagle-import") (part "R0402"))
    )
    (comp (ref "R100")
      (value "10K 0.1%")
      (footprint "eagle-import:0402")
      (libsource (lib "eagle-import") (part "R0402"))
    )
    (comp (ref "R101")
      (value "3.2K 1%")
      (footprint "eagle-import:0402")
      (libsource (lib "eagle-import") (part "R0402"))
    )
    (comp (ref "R102")
      (value "68R 1%")
      (footprint "eagle-import:0402")
      (libsource (lib "eagle-import") (part "R0402"))
    )
    (comp (ref "R103")
      (value "10K 0.1%")
      (footprint "eagle-import:0402")
      (libsource (lib "eagle-import") (part "R0402"))
    )
    (comp (ref "R104")
      (value "10K 0.1%")
      (footprint "eagle-import:0402")
      (libsource (lib "eagle-import") (part "R0402"))
    )
    (comp (ref "R105")
      (value "86K 1%")
      (footprint "eagle-import:0402")
      (libsource (lib "eagle-import") (part "R0402"))
    )
    (comp (ref "R106")
      (value "110R 1%")
      (footprint "eagle-import:0402")
      (libsource (lib "eagle-import") (part "R0402"))
    )
    (comp (ref "R107")
      (value "10K 0.1%")
      (footprint "eagle-import:0402")
      (libsource (lib "eagle-import") (part "R0402"))
    )
    (comp (ref "R108")
      (value "10K 0.1%")
      (footprint "eagle-import:0402")
      (libsource (lib "eagle-import") (part "R0402"))
    )
    (comp (ref "R109")
      (value "86K 1%")
      (footprint "eagle-import:0402")
      (libsource (lib "eagle-import") (part "R0402"))
    )
    (comp (ref "R110")
      (value "110R 1%")
      (footprint "eagle-import:0402")
      (libsource (lib "eagle-import") (part "R0402"))
    )
    (comp (ref "R111")
      (value "10K 0.1%")
      (footprint "eagle-import:0402")
      (libsource (lib "eagle-import") (part "R0402"))
    )
    (comp (ref "R112")
      (value "10K 0.1%")
      (footprint "eagle-import:0402")
      (libsource (lib "eagle-import") (part "R0402"))
    )
    (comp (ref "R113")
      (value "86K 1%")
      (footprint "eagle-import:0402")
      (libsource (lib "eagle-import") (part "R0402"))
    )
    (comp (ref "R114")
      (value "110R 1%")
      (footprint "eagle-import:0402")
      (libsource (lib "eagle-import") (part "R0402"))
    )
    (comp (ref "R115")
      (value "10K 0.1%")
      (footprint "eagle-import:0402")
      (libsource (lib "eagle-import") (part "R0402"))
    )
    (comp (ref "R116")
      (value "10K 0.1%")
      (footprint "eagle-import:0402")
      (libsource (lib "eagle-import") (part "R0402"))
    )
    (comp (ref "R117")
      (value "86K 1%")
      (footprint "eagle-import:0402")
      (libsource (lib "eagle-import") (part "R0402"))
    )
    (comp (ref "R118")
      (value "110R 1%")
      (footprint "eagle-import:0402")
      (libsource (lib "eagle-import") (part "R0402"))
    )
    (comp (ref "TP_3V3")
      (value "TP")
      (footprint "eagle-import:TP")
      (libsource (lib "eagle-import") (part "TP"))
    )
    (comp (ref "TP_GND")
      (value "TP")
      (footprint "eagle-import:TP")
      (libsource (lib "eagle-import") (part "TP"))
    )
    (comp (ref "VREF_DAC")
      (value "TP")
      (footprint "eagle-import:TP")
      (libsource (lib "eagle-import") (part "TP"))
    )
    (comp (ref "12VN")
      (value "TP")
      (footprint "eagle-import:TP")
      (libsource (lib "eagle-import") (part "TP"))
    )
    (comp (ref "12VP")
      (value "TP")
      (footprint "eagle-import:TP")
      (libsource (lib "eagle-import") (part "TP"))
    )
    (comp (ref "14VN")
      (value "TP")
      (footprint "eagle-import:TP")
      (libsource (lib "eagle-import") (part "TP"))
    )
    (comp (ref "14VP")
      (value "TP")
      (footprint "eagle-import:TP")
      (libsource (lib "eagle-import") (part "TP"))
    )
    (comp (ref "BUF") (value "TP") (footprint "eagle-import:TP") (libsource (lib "eagle-import") (part "TP")))
    (comp (ref "C85")
      (value "4.7uF")
      (footprint "eagle-import:C0402")
      (libsource (lib "eagle-import") (part "C-0402"))
    )
    (comp (ref "C86")
      (value "100nF")
      (footprint "eagle-import:C0402")
      (libsource (lib "eagle-import") (part "C-0402"))
    )
    (comp (ref "C90")
      (value "10uF")
      (footprint "eagle-import:C0402")
      (libsource (lib "eagle-import") (part "C-0402"))
    )
    (comp (ref "C91")
      (value "10nF")
      (footprint "eagle-import:C0402")
      (libsource (lib "eagle-import") (part "C-0402"))
    )
    (comp (ref "C92")
      (value "4.7nF")
      (footprint "eagle-import:C0402")
      (libsource (lib "eagle-import") (part "C-0402"))
    )
    (comp (ref "C93")
      (value "22uF")
      (footprint "eagle-import:C0805")
      (libsource (lib "eagle-import") (part "C-0805"))
    )
    (comp (ref "C94")
      (value "22uF")
      (footprint "eagle-import:C0805")
      (libsource (lib "eagle-import") (part "C-0805"))
    )
    (comp (ref "C95")
      (value "22uF")
      (footprint "eagle-import:C0805")
      (libsource (lib "eagle-import") (part "C-0805"))
    )
    (comp (ref "C96")
      (value "22uF")
      (footprint "eagle-import:C0805")
      (libsource (lib "eagle-import") (part "C-0805"))
    )
    (comp (ref "C97")
      (value "22uF")
      (footprint "eagle-import:C0805")
      (libsource (lib "eagle-import") (part "C-0805"))
    )
    (comp (ref "C98")
      (value "22uF")
      (footprint "eagle-import:C0805")
      (libsource (lib "eagle-import") (part "C-0805"))
    )
    (comp (ref "C99")
      (value "220nF")
      (footprint "eagle-import:C0402")
      (libsource (lib "eagle-import") (part "C-0402"))
    )
    (comp (ref "C100")
      (value "10pF")
      (footprint "eagle-import:C0402")
      (libsource (lib "eagle-import") (part "C-0402"))
    )
    (comp (ref "C101")
      (value "10pF")
      (footprint "eagle-import:C0402")
      (libsource (lib "eagle-import") (part "C-0402"))
    )
    (comp (ref "C102")
      (value "10uF")
      (footprint "eagle-import:C0805")
      (libsource (lib "eagle-import") (part "C-0805"))
    )
    (comp (ref "C103")
      (value "10nF")
      (footprint "eagle-import:C0402")
      (libsource (lib "eagle-import") (part "C-0402"))
    )
    (comp (ref "C104")
      (value "10uF")
      (footprint "eagle-import:C0805")
      (libsource (lib "eagle-import") (part "C-0805"))
    )
    (comp (ref "C105")
      (value "220nF")
      (footprint "eagle-import:C0402")
      (libsource (lib "eagle-import") (part "C-0402"))
    )
    (comp (ref "C106")
      (value "10nF")
      (footprint "eagle-import:C0402")
      (libsource (lib "eagle-import") (part "C-0402"))
    )
    (comp (ref "C107")
      (value "10nF")
      (footprint "eagle-import:C0402")
      (libsource (lib "eagle-import") (part "C-0402"))
    )
    (comp (ref "C108")
      (value "22uF")
      (footprint "eagle-import:C0805")
      (libsource (lib "eagle-import") (part "C-0805"))
    )
    (comp (ref "C109")
      (value "22uF")
      (footprint "eagle-import:C0805")
      (libsource (lib "eagle-import") (part "C-0805"))
    )
    (comp (ref "D3")
      (value "SS12")
      (footprint "eagle-import:SMA")
      (fields
        (field (name "DIGIKEY_PART_NUMBER") "SS12FSCT-ND")
        (field (name "MANUFACTURER") "ON Semiconductor")
        (field (name "CREATED_BY") "PCBLayout.com")
      )
      (libsource (lib "eagle-import") (part "SS12"))
    )
    (comp (ref "D4")
      (value "SS12")
      (footprint "eagle-import:SMA")
      (fields
        (field (name "DIGIKEY_PART_NUMBER") "SS12FSCT-ND")
        (field (name "MANUFACTURER") "ON Semiconductor")
        (field (name "CREATED_BY") "PCBLayout.com")
      )
      (libsource (lib "eagle-import") (part "SS12"))
    )
    (comp (ref "IC14")
      (value "TPS65131")
      (footprint "eagle-import:VQFN24-4X4-THERMAL2.5X2.5")
      (libsource (lib "eagle-import") (part "TPS65131TRGERQ1"))
    )
    (comp (ref "IC15")
      (value "TPS7A39")
      (footprint "eagle-import:WSON10-3X3")
      (libsource (lib "eagle-import") (part "TPS7A3901DSCR"))
    )
    (comp (ref "L3")
      (value "SRR5228A-4R7Y")
      (footprint "eagle-import:SRR5228A")
      (libsource (lib "eagle-import") (part "L"))
    )
    (comp (ref "L4")
      (value "SRR5228A-4R7Y")
      (footprint "eagle-import:SRR5228A")
      (libsource (lib "eagle-import") (part "L"))
    )
    (comp (ref "R14")
      (value "100R")
      (footprint "eagle-import:1206")
      (libsource (lib "eagle-import") (part "R1206"))
    )
    (comp (ref "R19")
      (value "950K 0.1%")
      (footprint "eagle-import:0402")
      (libsource (lib "eagle-import") (part "R0402"))
    )
    (comp (ref "R53")
      (value "R-TRIM")
      (footprint "eagle-import:TC33X")
      (libsource (lib "eagle-import") (part "R-TRIM"))
    )
    (comp (ref "R54")
      (value "R-TRIM")
      (footprint "eagle-import:TC33X")
      (libsource (lib "eagle-import") (part "R-TRIM"))
    )
    (comp (ref "R55")
      (value "20K")
      (footprint "eagle-import:TC33X")
      (libsource (lib "eagle-import") (part "R-TRIM"))
    )
    (comp (ref "R56")
      (value "20K")
      (footprint "eagle-import:TC33X")
      (libsource (lib "eagle-import") (part "R-TRIM"))
    )
    (comp (ref "R57")
      (value "102K 0.1%")
      (footprint "eagle-import:0402")
      (libsource (lib "eagle-import") (part "R0402"))
    )
    (comp (ref "R58")
      (value "1.2M 0.1%")
      (footprint "eagle-import:0402")
      (libsource (lib "eagle-import") (part "R0402"))
    )
    (comp (ref "R59")
      (value "137K 0.1%")
      (footprint "eagle-import:0402")
      (libsource (lib "eagle-import") (part "R0402"))
    )
    (comp (ref "R60")
      (value "75K 0.1%")
      (footprint "eagle-import:0402")
      (libsource (lib "eagle-import") (part "R0402"))
    )
    (comp (ref "R67")
      (value "10K 0.1%")
      (footprint "eagle-import:0402")
      (libsource (lib "eagle-import") (part "R0402"))
    )
    (comp (ref "R69")
      (value "100K 0.1%")
      (footprint "eagle-import:0402")
      (libsource (lib "eagle-import") (part "R0402"))
    )
    (comp (ref "R70")
      (value "100K 0.1%")
      (footprint "eagle-import:0402")
      (libsource (lib "eagle-import") (part "R0402"))
    )
    (comp (ref "R71")
      (value "10K 0.1%")
      (footprint "eagle-import:0402")
      (libsource (lib "eagle-import") (part "R0402"))
    )
    (comp (ref "R73")
      (value "10K 0.1%")
      (footprint "eagle-import:0402")
      (libsource (lib "eagle-import") (part "R0402"))
    )
    (comp (ref "R74")
      (value "90K 0.1%")
      (footprint "eagle-import:0402")
      (libsource (lib "eagle-import") (part "R0402"))
    )
    (comp (ref "R76")
      (value "10K 0.1%")
      (footprint "eagle-import:0402")
      (libsource (lib "eagle-import") (part "R0402"))
    )
    (comp (ref "T2")
      (value "IRLML5203")
      (footprint "eagle-import:MICRO3")
      (libsource (lib "eagle-import") (part "IRLML5203"))
    )
    (comp (ref "TP_BSW_G")
      (value "TP")
      (footprint "eagle-import:TP")
      (libsource (lib "eagle-import") (part "TP"))
    )
    (comp (ref "TP_VFB_14VN")
      (value "TP")
      (footprint "eagle-import:TP")
      (libsource (lib "eagle-import") (part "TP"))
    )
    (comp (ref "TP_VFB_14VP")
      (value "TP")
      (footprint "eagle-import:TP")
      (libsource (lib "eagle-import") (part "TP"))
    )
    (comp (ref "TP_VREF_TPS")
      (value "TP")
      (footprint "eagle-import:TP")
      (libsource (lib "eagle-import") (part "TP"))
    )
    (comp (ref "VFB12VN")
      (value "TP")
      (footprint "eagle-import:TP")
      (libsource (lib "eagle-import") (part "TP"))
    )
    (comp (ref "VFB12VP")
      (value "TP")
      (footprint "eagle-import:TP")
      (libsource (lib "eagle-import") (part "TP"))
    )
  )
  (nets
    (net (code "1") (name "+1V1") (class "Default")
      (node (ref "C112") (pin "1") (pinfunction "1_1") (pintype "passive"))
      (node (ref "C113") (pin "1") (pinfunction "1_1") (pintype "passive"))
      (node (ref "C114") (pin "1") (pinfunction "1_1") (pintype "passive"))
      (node (ref "DVDD") (pin "TP") (pinfunction "P$1_TP") (pintype "bidirectional"))
      (node (ref "IC2") (pin "23") (pinfunction "DVDD_23") (pintype "bidirectional"))
      (node (ref "IC2") (pin "45") (pinfunction "VREG_VOUT_45") (pintype "bidirectional"))
      (node (ref "IC2") (pin "50") (pinfunction "DVDD_50") (pintype "bidirectional"))
    )
    (net (code "2") (name "+3V3") (class "Default")
      (node (ref "C116") (pin "1") (pinfunction "1_1") (pintype "passive"))
      (node (ref "C121") (pin "1") (pinfunction "1_1") (pintype "passive"))
      (node (ref "C122") (pin "1") (pinfunction "1_1") (pintype "passive"))
      (node (ref "C123") (pin "1") (pinfunction "1_1") (pintype "passive"))
      (node (ref "C126") (pin "1") (pinfunction "1_1") (pintype "passive"))
      (node (ref "C18") (pin "1") (pinfunction "1_1") (pintype "passive"))
      (node (ref "C21") (pin "1") (pinfunction "1_1") (pintype "passive"))
      (node (ref "C22") (pin "1") (pinfunction "1_1") (pintype "passive"))
      (node (ref "C25") (pin "1") (pinfunction "1_1") (pintype "passive"))
      (node (ref "C27") (pin "1") (pinfunction "1_1") (pintype "passive"))
      (node (ref "C45") (pin "1") (pinfunction "1_1") (pintype "passive"))
      (node (ref "C47") (pin "1") (pinfunction "1_1") (pintype "passive"))
      (node (ref "C49") (pin "1") (pinfunction "1_1") (pintype "passive"))
      (node (ref "C50") (pin "1") (pinfunction "1_1") (pintype "passive"))
      (node (ref "C51") (pin "1") (pinfunction "1_1") (pintype "passive"))
      (node (ref "C64") (pin "1") (pinfunction "1_1") (pintype "passive"))
      (node (ref "C65") (pin "1") (pinfunction "1_1") (pintype "passive"))
      (node (ref "C76") (pin "1") (pinfunction "1_1") (pintype "passive"))
      (node (ref "C77") (pin "1") (pinfunction "1_1") (pintype "passive"))
      (node (ref "C80") (pin "1") (pinfunction "1_1") (pintype "passive"))
      (node (ref "C81") (pin "1") (pinfunction "1_1") (pintype "passive"))
      (node (ref "C82") (pin "1") (pinfunction "1_1") (pintype "passive"))
      (node (ref "C83") (pin "1") (pinfunction "1_1") (pintype "passive"))
      (node (ref "C84") (pin "1") (pinfunction "1_1") (pintype "passive"))
      (node (ref "C87") (pin "1") (pinfunction "1_1") (pintype "passive"))
      (node (ref "C88") (pin "1") (pinfunction "1_1") (pintype "passive"))
      (node (ref "IC1") (pin "5") (pinfunction "VOUT_5") (pintype "bidirectional"))
      (node (ref "IC10") (pin "12") (pinfunction "AVDD_12") (pintype "power_in"))
      (node (ref "IC10") (pin "28") (pinfunction "DVDD_28") (pintype "power_in"))
      (node (ref "IC10") (pin "29") (pinfunction "AVDD_29") (pintype "power_in"))
      (node (ref "IC11") (pin "5") (pinfunction "V+_5") (pintype "power_in"))
      (node (ref "IC12") (pin "1") (pinfunction "VIN_1") (pintype "bidirectional"))
      (node (ref "IC13") (pin "5") (pinfunction "V+_5") (pintype "power_in"))
      (node (ref "IC16") (pin "8") (pinfunction "VCC_8") (pintype "power_in"))
      (node (ref "IC17") (pin "5") (pinfunction "V+_5") (pintype "bidirectional"))
      (node (ref "IC2") (pin "1") (pinfunction "IOVDD_1") (pintype "bidirectional"))
      (node (ref "IC2") (pin "10") (pinfunction "IOVDD_10") (pintype "bidirectional"))
      (node (ref "IC2") (pin "22") (pinfunction "IOVDD_22") (pintype "bidirectional"))
      (node (ref "IC2") (pin "33") (pinfunction "IOVDD_33") (pintype "bidirectional"))
      (node (ref "IC2") (pin "42") (pinfunction "IOVDD_42") (pintype "bidirectional"))
      (node (ref "IC2") (pin "44") (pinfunction "VREG_VIN_44") (pintype "bidirectional"))
      (node (ref "IC2") (pin "48") (pinfunction "USB_VDD_48") (pintype "bidirectional"))
      (node (ref "IC2") (pin "49") (pinfunction "IOVDD_49") (pintype "bidirectional"))
      (node (ref "IC22") (pin "3") (pinfunction "AVDD_3") (pintype "power_in"))
      (node (ref "IC23") (pin "5") (pinfunction "V+_5") (pintype "power_in"))
      (node (ref "IC3") (pin "2") (pinfunction "V+_2") (pintype "power_in"))
      (node (ref "IC4") (pin "8") (pinfunction "VCC_8") (pintype "power_in"))
      (node (ref "IC7") (pin "7") (pinfunction "DVDD_7") (pintype "power_in"))
      (node (ref "IC9") (pin "7") (pinfunction "DVDD_7") (pintype "power_in"))
      (node (ref "IOVDD") (pin "TP") (pinfunction "P$1_TP") (pintype "bidirectional"))
      (node (ref "JP-3V3-1") (pin "1") (pinfunction "1_1") (pintype "passive"))
      (node (ref "JP-3V3-2") (pin "1") (pinfunction "1_1") (pintype "passive"))
      (node (ref "R16") (pin "1") (pinfunction "1_1") (pintype "passive"))
      (node (ref "R17") (pin "2") (pinfunction "2_2") (pintype "passive"))
      (node (ref "R18") (pin "2") (pinfunction "2_2") (pintype "passive"))
      (node (ref "R75") (pin "1") (pinfunction "1_1") (pintype "passive"))
      (node (ref "R86") (pin "5") (pinfunction "5_5") (pintype "passive"))
      (node (ref "R86") (pin "6") (pinfunction "6_6") (pintype "passive"))
      (node (ref "R86") (pin "7") (pinfunction "7_7") (pintype "passive"))
      (node (ref "R86") (pin "8") (pinfunction "8_8") (pintype "passive"))
      (node (ref "TP_3V3") (pin "TP") (pinfunction "P$1_TP") (pintype "bidirectional"))
    )
    (net (code "3") (name "+5V") (class "Default")
      (node (ref "C120") (pin "1") (pinfunction "1_1") (pintype "passive"))
      (node (ref "C128") (pin "1") (pinfunction "1_1") (pintype "passive"))
      (node (ref "C131") (pin "1") (pinfunction "1_1") (pintype "passive"))
      (node (ref "C134") (pin "1") (pinfunction "1_1") (pintype "passive"))
      (node (ref "C137") (pin "1") (pinfunction "1_1") (pintype "passive"))
      (node (ref "C26") (pin "1") (pinfunction "1_1") (pintype "passive"))
      (node (ref "C85") (pin "1") (pinfunction "1_1") (pintype "passive"))
      (node (ref "D1") (pin "C") (pinfunction "C_C") (pintype "passive"))
      (node (ref "IC1") (pin "1") (pinfunction "VIN_1") (pintype "bidirectional"))
      (node (ref "IC1") (pin "3") (pinfunction "EN_3") (pintype "bidirectional"))
      (node (ref "IC14") (pin "5") (pinfunction "INN_5") (pintype "power_in"))
      (node (ref "IC14") (pin "6") (pinfunction "INN_6") (pintype "power_in"))
      (node (ref "IC24") (pin "5") (pinfunction "V+_5") (pintype "power_in"))
      (node (ref "IC25") (pin "5") (pinfunction "V+_5") (pintype "power_in"))
      (node (ref "IC26") (pin "5") (pinfunction "V+_5") (pintype "power_in"))
      (node (ref "IC27") (pin "5") (pinfunction "V+_5") (pintype "power_in"))
      (node (ref "R14") (pin "2") (pinfunction "2_2") (pintype "passive"))
      (node (ref "R72") (pin "2") (pinfunction "2_2") (pintype "passive"))
      (node (ref "T2") (pin "2") (pinfunction "S_2") (pintype "passive"))
      (node (ref "X1") (pin "A8") (pinfunction "8_A8") (pintype "passive"))
      (node (ref "X1") (pin "A9") (pinfunction "9_A9") (pintype "passive"))
      (node (ref "X1") (pin "B8") (pinfunction "8_B8") (pintype "passive"))
      (node (ref "X1") (pin "B9") (pinfunction "9_B9") (pintype "passive"))
    )
    (net (code "4") (name "+12V") (class "Default")
      (node (ref "12VP") (pin "TP") (pinfunction "P$1_TP") (pintype "bidirectional"))
      (node (ref "C107") (pin "2") (pinfunction "2_2") (pintype "passive"))
      (node (ref "C108") (pin "1") (pinfunction "1_1") (pintype "passive"))
      (node (ref "C140") (pin "1") (pinfunction "1_1") (pintype "passive"))
      (node (ref "C143") (pin "1") (pinfunction "1_1") (pintype "passive"))
      (node (ref "C146") (pin "1") (pinfunction "1_1") (pintype "passive"))
      (node (ref "C149") (pin "1") (pinfunction "1_1") (pintype "passive"))
      (node (ref "C52") (pin "1") (pinfunction "1_1") (pintype "passive"))
      (node (ref "C53") (pin "1") (pinfunction "1_1") (pintype "passive"))
      (node (ref "C56") (pin "1") (pinfunction "1_1") (pintype "passive"))
      (node (ref "C57") (pin "1") (pinfunction "1_1") (pintype "passive"))
      (node (ref "C60") (pin "1") (pinfunction "1_1") (pintype "passive"))
      (node (ref "C61") (pin "1") (pinfunction "1_1") (pintype "passive"))
      (node (ref "C66") (pin "1") (pinfunction "1_1") (pintype "passive"))
      (node (ref "C67") (pin "1") (pinfunction "1_1") (pintype "passive"))
      (node (ref "IC15") (pin "10") (pinfunction "OUTP_10") (pintype "power_in"))
      (node (ref "IC28") (pin "5") (pinfunction "V+_5") (pintype "power_in"))
      (node (ref "IC29") (pin "5") (pinfunction "V+_5") (pintype "power_in"))
      (node (ref "IC30") (pin "5") (pinfunction "V+_5") (pintype "power_in"))
      (node (ref "IC31") (pin "5") (pinfunction "V+_5") (pintype "power_in"))
      (node (ref "IC6") (pin "14") (pinfunction "V+_14") (pintype "power_in"))
      (node (ref "IC7") (pin "26") (pinfunction "VDDH_26") (pintype "power_in"))
      (node (ref "IC8") (pin "14") (pinfunction "V+_14") (pintype "power_in"))
      (node (ref "IC9") (pin "26") (pinfunction "VDDH_26") (pintype "power_in"))
      (node (ref "R60") (pin "1") (pinfunction "1_1") (pintype "passive"))
      (node (ref "R70") (pin "1") (pinfunction "1_1") (pintype "passive"))
    )
    (net (code "5") (name "+14V") (class "Default")
      (node (ref "14VP") (pin "TP") (pinfunction "P$1_TP") (pintype "bidirectional"))
      (node (ref "C100") (pin "1") (pinfunction "1_1") (pintype "passive"))
      (node (ref "C104") (pin "1") (pinfunction "1_1") (pintype "passive"))
      (node (ref "C93") (pin "1") (pinfunction "1_1") (pintype "passive"))
      (node (ref "C94") (pin "1") (pinfunction "1_1") (pintype "passive"))
      (node (ref "C95") (pin "1") (pinfunction "1_1") (pintype "passive"))
      (node (ref "D3") (pin "C") (pinfunction "C_C") (pintype "passive"))
      (node (ref "IC14") (pin "23") (pinfunction "VPOS_23") (pintype "power_in"))
      (node (ref "IC15") (pin "1") (pinfunction "INP_1") (pintype "power_in"))
      (node (ref "IC15") (pin "2") (pinfunction "EN_2") (pintype "input"))
      (node (ref "R19") (pin "1") (pinfunction "1_1") (pintype "passive"))
    )
    (net (code "6") (name "-12V") (class "Default")
      (node (ref "12VN") (pin "TP") (pinfunction "P$1_TP") (pintype "bidirectional"))
      (node (ref "C106") (pin "1") (pinfunction "1_1") (pintype "passive"))
      (node (ref "C109") (pin "1") (pinfunction "1_1") (pintype "passive"))
      (node (ref "C4") (pin "1") (pinfunction "1_1") (pintype "passive"))
      (node (ref "C5") (pin "1") (pinfunction "1_1") (pintype "passive"))
      (node (ref "C54") (pin "1") (pinfunction "1_1") (pintype "passive"))
      (node (ref "C55") (pin "1") (pinfunction "1_1") (pintype "passive"))
      (node (ref "C58") (pin "1") (pinfunction "1_1") (pintype "passive"))
      (node (ref "C59") (pin "1") (pinfunction "1_1") (pintype "passive"))
      (node (ref "C6") (pin "1") (pinfunction "1_1") (pintype "passive"))
      (node (ref "C62") (pin "1") (pinfunction "1_1") (pintype "passive"))
      (node (ref "C63") (pin "1") (pinfunction "1_1") (pintype "passive"))
      (node (ref "C68") (pin "1") (pinfunction "1_1") (pintype "passive"))
      (node (ref "C69") (pin "1") (pinfunction "1_1") (pintype "passive"))
      (node (ref "C7") (pin "1") (pinfunction "1_1") (pintype "passive"))
      (node (ref "IC15") (pin "6") (pinfunction "OUTN_6") (pintype "power_in"))
      (node (ref "IC28") (pin "2") (pinfunction "V-_2") (pintype "power_in"))
      (node (ref "IC29") (pin "2") (pinfunction "V-_2") (pintype "power_in"))
      (node (ref "IC30") (pin "2") (pinfunction "V-_2") (pintype "power_in"))
      (node (ref "IC31") (pin "2") (pinfunction "V-_2") (pintype "power_in"))
      (node (ref "IC6") (pin "3") (pinfunction "V-_3") (pintype "power_in"))
      (node (ref "IC7") (pin "27") (pinfunction "VSSH_27") (pintype "power_in"))
      (node (ref "IC7") (pin "29") (pinfunction "PAD_29") (pintype "power_in"))
      (node (ref "IC8") (pin "3") (pinfunction "V-_3") (pintype "power_in"))
      (node (ref "IC9") (pin "27") (pinfunction "VSSH_27") (pintype "power_in"))
      (node (ref "IC9") (pin "29") (pinfunction "PAD_29") (pintype "power_in"))
      (node (ref "R67") (pin "1") (pinfunction "1_1") (pintype "passive"))
      (node (ref "R76") (pin "2") (pinfunction "2_2") (pintype "passive"))
    )
    (net (code "7") (name "-14V") (class "Default")
      (node (ref "14VN") (pin "TP") (pinfunction "P$1_TP") (pintype "bidirectional"))
      (node (ref "C101") (pin "1") (pinfunction "1_1") (pintype "passive"))
      (node (ref "C102") (pin "1") (pinfunction "1_1") (pintype "passive"))
      (node (ref "C96") (pin "1") (pinfunction "1_1") (pintype "passive"))
      (node (ref "C97") (pin "1") (pinfunction "1_1") (pintype "passive"))
      (node (ref "C98") (pin "1") (pinfunction "1_1") (pintype "passive"))
      (node (ref "D4") (pin "A") (pinfunction "A_A") (pintype "passive"))
      (node (ref "IC14") (pin "15") (pinfunction "VNEG_15") (pintype "power_in"))
      (node (ref "IC15") (pin "5") (pinfunction "INN_5") (pintype "power_in"))
      (node (ref "R59") (pin "2") (pinfunction "2_2") (pintype "passive"))
    )
    (net (code "8") (name "ADA_A_IO0") (class "Default")
      (node (ref "IC6") (pin "1") (pinfunction "A0_1") (pintype "input"))
      (node (ref "IC7") (pin "18") (pinfunction "GPIO0_18") (pintype "bidirectional"))
    )
    (net (code "9") (name "ADA_A_IO1") (class "Default")
      (node (ref "IC6") (pin "16") (pinfunction "A1_16") (pintype "input"))
      (node (ref "IC7") (pin "17") (pinfunction "GPIO1_17") (pintype "bidirectional"))
    )
    (net (code "10") (name "ADA_A_IO2") (class "Default")
      (node (ref "IC6") (pin "2") (pinfunction "EN_2") (pintype "input"))
      (node (ref "IC7") (pin "16") (pinfunction "GPIO2_16") (pintype "bidirectional"))
    )
    (net (code "11") (name "ADA_B_IO0") (class "Default")
      (node (ref "IC8") (pin "1") (pinfunction "A0_1") (pintype "input"))
      (node (ref "IC9") (pin "18") (pinfunction "GPIO0_18") (pintype "bidirectional"))
    )
    (net (code "12") (name "ADA_B_IO1") (class "Default")
      (node (ref "IC8") (pin "16") (pinfunction "A1_16") (pintype "input"))
      (node (ref "IC9") (pin "17") (pinfunction "GPIO1_17") (pintype "bidirectional"))
    )
    (net (code "13") (name "ADA_B_IO2") (class "Default")
      (node (ref "IC8") (pin "2") (pinfunction "EN_2") (pintype "input"))
      (node (ref "IC9") (pin "16") (pinfunction "GPIO2_16") (pintype "bidirectional"))
    )
    (net (code "14") (name "ADC_5VP") (class "Default")
      (node (ref "IC2") (pin "41") (pinfunction "GPIO29/ADC3_41") (pintype "bidirectional"))
      (node (ref "R72") (pin "1") (pinfunction "1_1") (pintype "passive"))
      (node (ref "R77") (pin "2") (pinfunction "2_2") (pintype "passive"))
    )
    (net (code "15") (name "ADC_12VN") (class "Default")
      (node (ref "IC2") (pin "40") (pinfunction "GPIO28/ADC2_40") (pintype "bidirectional"))
      (node (ref "R67") (pin "2") (pinfunction "2_2") (pintype "passive"))
      (node (ref "R69") (pin "1") (pinfunction "1_1") (pintype "passive"))
    )
    (net (code "16") (name "ADC_12VP") (class "Default")
      (node (ref "IC2") (pin "39") (pinfunction "GPIO27/ADC1_39") (pintype "bidirectional"))
      (node (ref "R70") (pin "2") (pinfunction "2_2") (pintype "passive"))
      (node (ref "R71") (pin "1") (pinfunction "1_1") (pintype "passive"))
    )
    (net (code "17") (name "ADC_AIN_N") (class "Default")
      (node (ref "C24") (pin "2") (pinfunction "2_2") (pintype "passive"))
      (node (ref "C41") (pin "2") (pinfunction "2_2") (pintype "passive"))
      (node (ref "R21") (pin "1") (pinfunction "1_1") (pintype "passive"))
      (node (ref "R46") (pin "1") (pinfunction "1_1") (pintype "passive"))
    )
    (net (code "18") (name "ADC_AIN_P") (class "Default")
      (node (ref "C23") (pin "1") (pinfunction "1_1") (pintype "passive"))
      (node (ref "C41") (pin "1") (pinfunction "1_1") (pintype "passive"))
      (node (ref "R20") (pin "1") (pinfunction "1_1") (pintype "passive"))
      (node (ref "R45") (pin "2") (pinfunction "2_2") (pintype "passive"))
    )
    (net (code "19") (name "ADC_BIN_N") (class "Default")
      (node (ref "C43") (pin "2") (pinfunction "2_2") (pintype "passive"))
      (node (ref "C44") (pin "2") (pinfunction "2_2") (pintype "passive"))
      (node (ref "R23") (pin "1") (pinfunction "1_1") (pintype "passive"))
      (node (ref "R48") (pin "2") (pinfunction "2_2") (pintype "passive"))
    )
    (net (code "20") (name "ADC_BIN_P") (class "Default")
      (node (ref "C42") (pin "1") (pinfunction "1_1") (pintype "passive"))
      (node (ref "C44") (pin "1") (pinfunction "1_1") (pintype "passive"))
      (node (ref "R22") (pin "1") (pinfunction "1_1") (pintype "passive"))
      (node (ref "R47") (pin "1") (pinfunction "1_1") (pintype "passive"))
    )
    (net (code "21") (name "ADC_IN0") (class "Default")
      (node (ref "IC10") (pin "1") (pinfunction "AINP_A_1") (pintype "input"))
      (node (ref "R45") (pin "1") (pinfunction "1_1") (pintype "passive"))
    )
    (net (code "22") (name "ADC_IN1") (class "Default")
      (node (ref "IC10") (pin "2") (pinfunction "AINM_A_2") (pintype "input"))
      (node (ref "R46") (pin "2") (pinfunction "2_2") (pintype "passive"))
    )
    (net (code "23") (name "ADC_IN2") (class "Default")
      (node (ref "IC10") (pin "8") (pinfunction "AINP_B_8") (pintype "input"))
      (node (ref "R48") (pin "1") (pinfunction "1_1") (pintype "passive"))
    )
    (net (code "24") (name "ADC_IN3") (class "Default")
      (node (ref "IC10") (pin "7") (pinfunction "AINM_B_7") (pintype "input"))
      (node (ref "R47") (pin "2") (pinfunction "2_2") (pintype "passive"))
    )
    (net (code "25") (name "ADC_RDY") (class "Default")
      (node (ref "IC10") (pin "25") (pinfunction "READY/STROBE_25") (pintype "output"))
      (node (ref "IC2") (pin "11") (pinfunction "GPIO8_11") (pintype "bidirectional"))
      (node (ref "X1") (pin "A11") (pinfunction "11_A11") (pintype "passive"))
    )
    (net (code "26") (name "ADC_VUSB") (class "Default")
      (node (ref "IC2") (pin "38") (pinfunction "GPIO26/ADC0_38") (pintype "bidirectional"))
      (node (ref "R63") (pin "2") (pinfunction "2_2") (pintype "passive"))
      (node (ref "R64") (pin "1") (pinfunction "1_1") (pintype "passive"))
    )
    (net (code "27") (name "AI_0+") (class "Default")
      (node (ref "J1") (pin "2") (pinfunction "2_2") (pintype "bidirectional"))
      (node (ref "R25") (pin "1") (pinfunction "1_1") (pintype "passive"))
    )
    (net (code "28") (name "AI_1-") (class "Default")
      (node (ref "J1") (pin "3") (pinfunction "3_3") (pintype "bidirectional"))
      (node (ref "R26") (pin "1") (pinfunction "1_1") (pintype "passive"))
    )
    (net (code "29") (name "AI_2+") (class "Default")
      (node (ref "J1") (pin "4") (pinfunction "4_4") (pintype "bidirectional"))
      (node (ref "R27") (pin "1") (pinfunction "1_1") (pintype "passive"))
    )
    (net (code "30") (name "AI_3-") (class "Default")
      (node (ref "J1") (pin "5") (pinfunction "5_5") (pintype "bidirectional"))
      (node (ref "R28") (pin "1") (pinfunction "1_1") (pintype "passive"))
    )
    (net (code "31") (name "AI_4+") (class "Default")
      (node (ref "J1") (pin "6") (pinfunction "6_6") (pintype "bidirectional"))
      (node (ref "R29") (pin "1") (pinfunction "1_1") (pintype "passive"))
    )
    (net (code "32") (name "AI_5-") (class "Default")
      (node (ref "J1") (pin "7") (pinfunction "7_7") (pintype "bidirectional"))
      (node (ref "R30") (pin "1") (pinfunction "1_1") (pintype "passive"))
    )
    (net (code "33") (name "AI_6+") (class "Default")
      (node (ref "J1") (pin "8") (pinfunction "8_8") (pintype "bidirectional"))
      (node (ref "R31") (pin "1") (pinfunction "1_1") (pintype "passive"))
    )
    (net (code "34") (name "AI_7-") (class "Default")
      (node (ref "J1") (pin "9") (pinfunction "9_9") (pintype "bidirectional"))
      (node (ref "R32") (pin "1") (pinfunction "1_1") (pintype "passive"))
    )
    (net (code "35") (name "AI_8+") (class "Default")
      (node (ref "J1") (pin "10") (pinfunction "10_10") (pintype "bidirectional"))
      (node (ref "R33") (pin "1") (pinfunction "1_1") (pintype "passive"))
    )
    (net (code "36") (name "AI_9-") (class "Default")
      (node (ref "J1") (pin "11") (pinfunction "11_11") (pintype "bidirectional"))
      (node (ref "R34") (pin "1") (pinfunction "1_1") (pintype "passive"))
    )
    (net (code "37") (name "AI_10+") (class "Default")
      (node (ref "J1") (pin "12") (pinfunction "12_12") (pintype "bidirectional"))
      (node (ref "R35") (pin "1") (pinfunction "1_1") (pintype "passive"))
    )
    (net (code "38") (name "AI_11-") (class "Default")
      (node (ref "J1") (pin "13") (pinfunction "13_13") (pintype "bidirectional"))
      (node (ref "R36") (pin "1") (pinfunction "1_1") (pintype "passive"))
    )
    (net (code "39") (name "AI_12+") (class "Default")
      (node (ref "J1") (pin "14") (pinfunction "14_14") (pintype "bidirectional"))
      (node (ref "R37") (pin "1") (pinfunction "1_1") (pintype "passive"))
    )
    (net (code "40") (name "AI_13-") (class "Default")
      (node (ref "J1") (pin "15") (pinfunction "15_15") (pintype "bidirectional"))
      (node (ref "R38") (pin "1") (pinfunction "1_1") (pintype "passive"))
    )
    (net (code "41") (name "AI_14+") (class "Default")
      (node (ref "J1") (pin "16") (pinfunction "16_16") (pintype "bidirectional"))
      (node (ref "R40") (pin "1") (pinfunction "1_1") (pintype "passive"))
    )
    (net (code "42") (name "AI_15-") (class "Default")
      (node (ref "J1") (pin "17") (pinfunction "17_17") (pintype "bidirectional"))
      (node (ref "R41") (pin "1") (pinfunction "1_1") (pintype "passive"))
    )
    (net (code "43") (name "AO_0") (class "Default")
      (node (ref "C127") (pin "1") (pinfunction "1_1") (pintype "passive"))
      (node (ref "J1") (pin "21") (pinfunction "21_21") (pintype "bidirectional"))
      (node (ref "R89") (pin "2") (pinfunction "2_2") (pintype "passive"))
      (node (ref "R90") (pin "2") (pinfunction "2_2") (pintype "passive"))
    )
    (net (code "44") (name "AO_1") (class "Default")
      (node (ref "C130") (pin "1") (pinfunction "1_1") (pintype "passive"))
      (node (ref "J1") (pin "23") (pinfunction "23_23") (pintype "bidirectional"))
      (node (ref "R93") (pin "2") (pinfunction "2_2") (pintype "passive"))
      (node (ref "R94") (pin "2") (pinfunction "2_2") (pintype "passive"))
    )
    (net (code "45") (name "AO_2") (class "Default")
      (node (ref "C133") (pin "1") (pinfunction "1_1") (pintype "passive"))
      (node (ref "J1") (pin "25") (pinfunction "25_25") (pintype "bidirectional"))
      (node (ref "R97") (pin "2") (pinfunction "2_2") (pintype "passive"))
      (node (ref "R98") (pin "2") (pinfunction "2_2") (pintype "passive"))
    )
    (net (code "46") (name "AO_3") (class "Default")
      (node (ref "C136") (pin "1") (pinfunction "1_1") (pintype "passive"))
      (node (ref "J1") (pin "27") (pinfunction "27_27") (pintype "bidirectional"))
      (node (ref "R101") (pin "2") (pinfunction "2_2") (pintype "passive"))
      (node (ref "R102") (pin "2") (pinfunction "2_2") (pintype "passive"))
    )
    (net (code "47") (name "AO_4") (class "Default")
      (node (ref "C139") (pin "1") (pinfunction "1_1") (pintype "passive"))
      (node (ref "J1") (pin "29") (pinfunction "29_29") (pintype "bidirectional"))
      (node (ref "R105") (pin "2") (pinfunction "2_2") (pintype "passive"))
      (node (ref "R106") (pin "2") (pinfunction "2_2") (pintype "passive"))
    )
    (net (code "48") (name "AO_5") (class "Default")
      (node (ref "C142") (pin "1") (pinfunction "1_1") (pintype "passive"))
      (node (ref "J1") (pin "31") (pinfunction "31_31") (pintype "bidirectional"))
      (node (ref "R109") (pin "2") (pinfunction "2_2") (pintype "passive"))
      (node (ref "R110") (pin "2") (pinfunction "2_2") (pintype "passive"))
    )
    (net (code "49") (name "AO_6") (class "Default")
      (node (ref "C145") (pin "1") (pinfunction "1_1") (pintype "passive"))
      (node (ref "J1") (pin "33") (pinfunction "33_33") (pintype "bidirectional"))
      (node (ref "R113") (pin "2") (pinfunction "2_2") (pintype "passive"))
      (node (ref "R114") (pin "2") (pinfunction "2_2") (pintype "passive"))
    )
    (net (code "50") (name "AO_7") (class "Default")
      (node (ref "C148") (pin "1") (pinfunction "1_1") (pintype "passive"))
      (node (ref "J1") (pin "35") (pinfunction "35_35") (pintype "bidirectional"))
      (node (ref "R117") (pin "2") (pinfunction "2_2") (pintype "passive"))
      (node (ref "R118") (pin "2") (pinfunction "2_2") (pintype "passive"))
    )
    (net (code "51") (name "AVDD") (class "Default")
      (node (ref "AVDD") (pin "TP") (pinfunction "P$1_TP") (pintype "bidirectional"))
      (node (ref "C17") (pin "1") (pinfunction "1_1") (pintype "passive"))
      (node (ref "C89") (pin "1") (pinfunction "1_1") (pintype "passive"))
      (node (ref "IC2") (pin "43") (pinfunction "ADC_AVDD_43") (pintype "bidirectional"))
      (node (ref "IC3") (pin "1") (pinfunction "OUT_1") (pintype "output"))
      (node (ref "IC3") (pin "4") (pinfunction "-IN_4") (pintype "input"))
    )
    (net (code "52") (name "BSW_G") (class "Default")
      (node (ref "IC14") (pin "7") (pinfunction "BSW_7") (pintype "output"))
      (node (ref "T2") (pin "1") (pinfunction "G_1") (pintype "passive"))
      (node (ref "TP_BSW_G") (pin "TP") (pinfunction "P$1_TP") (pintype "bidirectional"))
    )
    (net (code "53") (name "BUF") (class "Default")
      (node (ref "BUF") (pin "TP") (pinfunction "P$1_TP") (pintype "bidirectional"))
      (node (ref "C105") (pin "2") (pinfunction "2_2") (pintype "passive"))
      (node (ref "IC15") (pin "8") (pinfunction "BUF_8") (pintype "input"))
      (node (ref "R74") (pin "1") (pinfunction "1_1") (pintype "passive"))
    )
    (net (code "54") (name "CC1") (class "Default")
      (node (ref "R62") (pin "1") (pinfunction "1_1") (pintype "passive"))
      (node (ref "USBC") (pin "A5") (pinfunction "CC1_A5") (pintype "passive"))
    )
    (net (code "55") (name "CC2") (class "Default")
      (node (ref "R61") (pin "1") (pinfunction "1_1") (pintype "passive"))
      (node (ref "USBC") (pin "B5") (pinfunction "CC2_B5") (pintype "passive"))
    )
    (net (code "56") (name "DAC_0") (class "Default")
      (node (ref "DAC0") (pin "TP") (pinfunction "P$1_TP") (pintype "bidirectional"))
      (node (ref "IC22") (pin "4") (pinfunction "VOUT_A_4") (pintype "output"))
      (node (ref "IC24") (pin "3") (pinfunction "+IN_3") (pintype "input"))
    )
    (net (code "57") (name "DAC_1") (class "Default")
      (node (ref "DAC1") (pin "TP") (pinfunction "P$1_TP") (pintype "bidirectional"))
      (node (ref "IC22") (pin "13") (pinfunction "VOUT_B_13") (pintype "output"))
      (node (ref "IC25") (pin "3") (pinfunction "+IN_3") (pintype "input"))
    )
    (net (code "58") (name "DAC_2") (class "Default")
      (node (ref "DAC2") (pin "TP") (pinfunction "P$1_TP") (pintype "bidirectional"))
      (node (ref "IC22") (pin "5") (pinfunction "VOUT_C_5") (pintype "output"))
      (node (ref "IC26") (pin "3") (pinfunction "+IN_3") (pintype "input"))
    )
    (net (code "59") (name "DAC_3") (class "Default")
      (node (ref "DAC3") (pin "TP") (pinfunction "P$1_TP") (pintype "bidirectional"))
      (node (ref "IC22") (pin "12") (pinfunction "VOUT_D_12") (pintype "output"))
      (node (ref "IC27") (pin "3") (pinfunction "+IN_3") (pintype "input"))
    )
    (net (code "60") (name "DAC_4") (class "Default")
      (node (ref "DAC4") (pin "TP") (pinfunction "P$1_TP") (pintype "bidirectional"))
      (node (ref "IC22") (pin "6") (pinfunction "VOUT_E_6") (pintype "output"))
      (node (ref "IC28") (pin "3") (pinfunction "+IN_3") (pintype "input"))
    )
    (net (code "61") (name "DAC_5") (class "Default")
      (node (ref "DAC5") (pin "TP") (pinfunction "P$1_TP") (pintype "bidirectional"))
      (node (ref "IC22") (pin "11") (pinfunction "VOUT_F_11") (pintype "output"))
      (node (ref "IC29") (pin "3") (pinfunction "+IN_3") (pintype "input"))
    )
    (net (code "62") (name "DAC_6") (class "Default")
      (node (ref "DAC6") (pin "TP") (pinfunction "P$1_TP") (pintype "bidirectional"))
      (node (ref "IC22") (pin "7") (pinfunction "VOUT_G_7") (pintype "output"))
      (node (ref "IC30") (pin "3") (pinfunction "+IN_3") (pintype "input"))
    )
    (net (code "63") (name "DAC_7") (class "Default")
      (node (ref "DAC7") (pin "TP") (pinfunction "P$1_TP") (pintype "bidirectional"))
      (node (ref "IC22") (pin "10") (pinfunction "VOUT_H_10") (pintype "output"))
      (node (ref "IC31") (pin "3") (pinfunction "+IN_3") (pintype "input"))
    )
    (net (code "64") (name "DAC_FB0") (class "Default")
      (node (ref "C129") (pin "2") (pinfunction "2_2") (pintype "passive"))
      (node (ref "FB0") (pin "TP") (pinfunction "P$1_TP") (pintype "bidirectional"))
      (node (ref "IC24") (pin "4") (pinfunction "-IN_4") (pintype "input"))
      (node (ref "R87") (pin "2") (pinfunction "2_2") (pintype "passive"))
      (node (ref "R88") (pin "2") (pinfunction "2_2") (pintype "passive"))
      (node (ref "R89") (pin "1") (pinfunction "1_1") (pintype "passive"))
    )
    (net (code "65") (name "DAC_FB1") (class "Default")
      (node (ref "C8") (pin "2") (pinfunction "2_2") (pintype "passive"))
      (node (ref "FB1") (pin "TP") (pinfunction "P$1_TP") (pintype "bidirectional"))
      (node (ref "IC25") (pin "4") (pinfunction "-IN_4") (pintype "input"))
      (node (ref "R91") (pin "2") (pinfunction "2_2") (pintype "passive"))
      (node (ref "R92") (pin "2") (pinfunction "2_2") (pintype "passive"))
      (node (ref "R93") (pin "1") (pinfunction "1_1") (pintype "passive"))
    )
    (net (code "66") (name "DAC_FB2") (class "Default")
      (node (ref "C9") (pin "2") (pinfunction "2_2") (pintype "passive"))
      (node (ref "FB2") (pin "TP") (pinfunction "P$1_TP") (pintype "bidirectional"))
      (node (ref "IC26") (pin "4") (pinfunction "-IN_4") (pintype "input"))
      (node (ref "R95") (pin "2") (pinfunction "2_2") (pintype "passive"))
      (node (ref "R96") (pin "2") (pinfunction "2_2") (pintype "passive"))
      (node (ref "R97") (pin "1") (pinfunction "1_1") (pintype "passive"))
    )
    (net (code "67") (name "DAC_FB3") (class "Default")
      (node (ref "C10") (pin "2") (pinfunction "2_2") (pintype "passive"))
      (node (ref "FB3") (pin "TP") (pinfunction "P$1_TP") (pintype "bidirectional"))
      (node (ref "IC27") (pin "4") (pinfunction "-IN_4") (pintype "input"))
      (node (ref "R100") (pin "2") (pinfunction "2_2") (pintype "passive"))
      (node (ref "R101") (pin "1") (pinfunction "1_1") (pintype "passive"))
      (node (ref "R99") (pin "2") (pinfunction "2_2") (pintype "passive"))
    )
    (net (code "68") (name "DAC_FB4") (class "Default")
      (node (ref "C14") (pin "2") (pinfunction "2_2") (pintype "passive"))
      (node (ref "FB4") (pin "TP") (pinfunction "P$1_TP") (pintype "bidirectional"))
      (node (ref "IC28") (pin "4") (pinfunction "-IN_4") (pintype "input"))
      (node (ref "R103") (pin "2") (pinfunction "2_2") (pintype "passive"))
      (node (ref "R104") (pin "2") (pinfunction "2_2") (pintype "passive"))
      (node (ref "R105") (pin "1") (pinfunction "1_1") (pintype "passive"))
    )
    (net (code "69") (name "DAC_FB5") (class "Default")
      (node (ref "C13") (pin "2") (pinfunction "2_2") (pintype "passive"))
      (node (ref "FB5") (pin "TP") (pinfunction "P$1_TP") (pintype "bidirectional"))
      (node (ref "IC29") (pin "4") (pinfunction "-IN_4") (pintype "input"))
      (node (ref "R107") (pin "2") (pinfunction "2_2") (pintype "passive"))
      (node (ref "R108") (pin "2") (pinfunction "2_2") (pintype "passive"))
      (node (ref "R109") (pin "1") (pinfunction "1_1") (pintype "passive"))
    )
    (net (code "70") (name "DAC_FB6") (class "Default")
      (node (ref "C12") (pin "2") (pinfunction "2_2") (pintype "passive"))
      (node (ref "FB6") (pin "TP") (pinfunction "P$1_TP") (pintype "bidirectional"))
      (node (ref "IC30") (pin "4") (pinfunction "-IN_4") (pintype "input"))
      (node (ref "R111") (pin "2") (pinfunction "2_2") (pintype "passive"))
      (node (ref "R112") (pin "2") (pinfunction "2_2") (pintype "passive"))
      (node (ref "R113") (pin "1") (pinfunction "1_1") (pintype "passive"))
    )
    (net (code "71") (name "DAC_FB7") (class "Default")
      (node (ref "C11") (pin "2") (pinfunction "2_2") (pintype "passive"))
      (node (ref "FB7") (pin "TP") (pinfunction "P$1_TP") (pintype "bidirectional"))
      (node (ref "IC31") (pin "4") (pinfunction "-IN_4") (pintype "input"))
      (node (ref "R115") (pin "2") (pinfunction "2_2") (pintype "passive"))
      (node (ref "R116") (pin "2") (pinfunction "2_2") (pintype "passive"))
      (node (ref "R117") (pin "1") (pinfunction "1_1") (pintype "passive"))
    )
    (net (code "72") (name "DAC_~{CLR}") (class "Default")
      (node (ref "CLR") (pin "TP") (pinfunction "P$1_TP") (pintype "bidirectional"))
      (node (ref "IC2") (pin "18") (pinfunction "GPIO15_18") (pintype "bidirectional"))
      (node (ref "IC22") (pin "9") (pinfunction "~{CLR}_9") (pintype "bidirectional"))
      (node (ref "R86") (pin "4") (pinfunction "4_4") (pintype "passive"))
      (node (ref "X1") (pin "B13") (pinfunction "13_B13") (pintype "passive"))
    )
    (net (code "73") (name "DAC_~{LDAC}") (class "Default")
      (node (ref "IC2") (pin "17") (pinfunction "GPIO14_17") (pintype "bidirectional"))
      (node (ref "IC22") (pin "1") (pinfunction "~{LDAC}_1") (pintype "bidirectional"))
      (node (ref "LDAC") (pin "TP") (pinfunction "P$1_TP") (pintype "bidirectional"))
      (node (ref "R86") (pin "2") (pinfunction "2_2") (pintype "passive"))
      (node (ref "X1") (pin "B12") (pinfunction "12_B12") (pintype "passive"))
    )
    (net (code "74") (name "EXT") (class "Default")
      (node (ref "J1") (pin "1") (pinfunction "1_1") (pintype "bidirectional"))
      (node (ref "J1") (pin "20") (pinfunction "20_20") (pintype "bidirectional"))
    )
    (net (code "75") (name "GND") (class "Default")
      (node (ref "C1") (pin "2") (pinfunction "2_2") (pintype "passive"))
      (node (ref "C102") (pin "2") (pinfunction "2_2") (pintype "passive"))
      (node (ref "C103") (pin "2") (pinfunction "2_2") (pintype "passive"))
      (node (ref "C104") (pin "2") (pinfunction "2_2") (pintype "passive"))
      (node (ref "C105") (pin "1") (pinfunction "1_1") (pintype "passive"))
      (node (ref "C108") (pin "2") (pinfunction "2_2") (pintype "passive"))
      (node (ref "C109") (pin "2") (pinfunction "2_2") (pintype "passive"))
      (node (ref "C111") (pin "2") (pinfunction "2_2") (pintype "passive"))
      (node (ref "C112") (pin "2") (pinfunction "2_2") (pintype "passive"))
      (node (ref "C113") (pin "2") (pinfunction "2_2") (pintype "passive"))
      (node (ref "C114") (pin "2") (pinfunction "2_2") (pintype "passive"))
      (node (ref "C115") (pin "2") (pinfunction "2_2") (pintype "passive"))
      (node (ref "C116") (pin "2") (pinfunction "2_2") (pintype "passive"))
      (node (ref "C120") (pin "2") (pinfunction "2_2") (pintype "passive"))
      (node (ref "C121") (pin "2") (pinfunction "2_2") (pintype "passive"))
      (node (ref "C122") (pin "2") (pinfunction "2_2") (pintype "passive"))
      (node (ref "C123") (pin "2") (pinfunction "2_2") (pintype "passive"))
      (node (ref "C124") (pin "2") (pinfunction "2_2") (pintype "passive"))
      (node (ref "C125") (pin "2") (pinfunction "2_2") (pintype "passive"))
      (node (ref "C126") (pin "2") (pinfunction "2_2") (pintype "passive"))
      (node (ref "C127") (pin "2") (pinfunction "2_2") (pintype "passive"))
      (node (ref "C128") (pin "2") (pinfunction "2_2") (pintype "passive"))
      (node (ref "C130") (pin "2") (pinfunction "2_2") (pintype "passive"))
      (node (ref "C131") (pin "2") (pinfunction "2_2") (pintype "passive"))
      (node (ref "C133") (pin "2") (pinfunction "2_2") (pintype "passive"))
      (node (ref "C134") (pin "2") (pinfunction "2_2") (pintype "passive"))
      (node (ref "C136") (pin "2") (pinfunction "2_2") (pintype "passive"))
      (node (ref "C137") (pin "2") (pinfunction "2_2") (pintype "passive"))
      (node (ref "C139") (pin "2") (pinfunction "2_2") (pintype "passive"))
      (node (ref "C140") (pin "2") (pinfunction "2_2") (pintype "passive"))
      (node (ref "C142") (pin "2") (pinfunction "2_2") (pintype "passive"))
      (node (ref "C143") (pin "2") (pinfunction "2_2") (pintype "passive"))
      (node (ref "C145") (pin "2") (pinfunction "2_2") (pintype "passive"))
      (node (ref "C146") (pin "2") (pinfunction "2_2") (pintype "passive"))
      (node (ref "C148") (pin "2") (pinfunction "2_2") (pintype "passive"))
      (node (ref "C149") (pin "2") (pinfunction "2_2") (pintype "passive"))
      (node (ref "C15") (pin "2") (pinfunction "2_2") (pintype "passive"))
      (node (ref "C16") (pin "2") (pinfunction "2_2") (pintype "passive"))
      (node (ref "C17") (pin "2") (pinfunction "2_2") (pintype "passive"))
      (node (ref "C18") (pin "2") (pinfunction "2_2") (pintype "passive"))
      (node (ref "C19") (pin "2") (pinfunction "2_2") (pintype "passive"))
      (node (ref "C2") (pin "2") (pinfunction "2_2") (pintype "passive"))
      (node (ref "C20") (pin "2") (pinfunction "2_2") (pintype "passive"))
      (node (ref "C21") (pin "2") (pinfunction "2_2") (pintype "passive"))
      (node (ref "C22") (pin "2") (pinfunction "2_2") (pintype "passive"))
      (node (ref "C23") (pin "2") (pinfunction "2_2") (pintype "passive"))
      (node (ref "C24") (pin "1") (pinfunction "1_1") (pintype "passive"))
      (node (ref "C25") (pin "2") (pinfunction "2_2") (pintype "passive"))
      (node (ref "C26") (pin "2") (pinfunction "2_2") (pintype "passive"))
      (node (ref "C27") (pin "2") (pinfunction "2_2") (pintype "passive"))
      (node (ref "C28") (pin "2") (pinfunction "2_2") (pintype "passive"))
      (node (ref "C29") (pin "2") (pinfunction "2_2") (pintype "passive"))
      (node (ref "C3") (pin "2") (pinfunction "2_2") (pintype "passive"))
      (node (ref "C30") (pin "2") (pinfunction "2_2") (pintype "passive"))
      (node (ref "C31") (pin "2") (pinfunction "2_2") (pintype "passive"))
      (node (ref "C32") (pin "2") (pinfunction "2_2") (pintype "passive"))
      (node (ref "C33") (pin "2") (pinfunction "2_2") (pintype "passive"))
      (node (ref "C34") (pin "2") (pinfunction "2_2") (pintype "passive"))
      (node (ref "C35") (pin "2") (pinfunction "2_2") (pintype "passive"))
      (node (ref "C36") (pin "2") (pinfunction "2_2") (pintype "passive"))
      (node (ref "C37") (pin "2") (pinfunction "2_2") (pintype "passive"))
      (node (ref "C38") (pin "2") (pinfunction "2_2") (pintype "passive"))
      (node (ref "C39") (pin "2") (pinfunction "2_2") (pintype "passive"))
      (node (ref "C4") (pin "2") (pinfunction "2_2") (pintype "passive"))
      (node (ref "C40") (pin "2") (pinfunction "2_2") (pintype "passive"))
      (node (ref "C42") (pin "2") (pinfunction "2_2") (pintype "passive"))
      (node (ref "C43") (pin "1") (pinfunction "1_1") (pintype "passive"))
      (node (ref "C45") (pin "2") (pinfunction "2_2") (pintype "passive"))
      (node (ref "C46") (pin "2") (pinfunction "2_2") (pintype "passive"))
      (node (ref "C47") (pin "2") (pinfunction "2_2") (pintype "passive"))
      (node (ref "C48") (pin "2") (pinfunction "2_2") (pintype "passive"))
      (node (ref "C49") (pin "2") (pinfunction "2_2") (pintype "passive"))
      (node (ref "C5") (pin "2") (pinfunction "2_2") (pintype "passive"))
      (node (ref "C50") (pin "2") (pinfunction "2_2") (pintype "passive"))
      (node (ref "C51") (pin "2") (pinfunction "2_2") (pintype "passive"))
      (node (ref "C52") (pin "2") (pinfunction "2_2") (pintype "passive"))
      (node (ref "C53") (pin "2") (pinfunction "2_2") (pintype "passive"))
      (node (ref "C54") (pin "2") (pinfunction "2_2") (pintype "passive"))
      (node (ref "C55") (pin "2") (pinfunction "2_2") (pintype "passive"))
      (node (ref "C56") (pin "2") (pinfunction "2_2") (pintype "passive"))
      (node (ref "C57") (pin "2") (pinfunction "2_2") (pintype "passive"))
      (node (ref "C58") (pin "2") (pinfunction "2_2") (pintype "passive"))
      (node (ref "C59") (pin "2") (pinfunction "2_2") (pintype "passive"))
      (node (ref "C6") (pin "2") (pinfunction "2_2") (pintype "passive"))
      (node (ref "C60") (pin "2") (pinfunction "2_2") (pintype "passive"))
      (node (ref "C61") (pin "2") (pinfunction "2_2") (pintype "passive"))
      (node (ref "C62") (pin "2") (pinfunction "2_2") (pintype "passive"))
      (node (ref "C63") (pin "2") (pinfunction "2_2") (pintype "passive"))
      (node (ref "C64") (pin "2") (pinfunction "2_2") (pintype "passive"))
      (node (ref "C65") (pin "2") (pinfunction "2_2") (pintype "passive"))
      (node (ref "C66") (pin "2") (pinfunction "2_2") (pintype "passive"))
      (node (ref "C67") (pin "2") (pinfunction "2_2") (pintype "passive"))
      (node (ref "C68") (pin "2") (pinfunction "2_2") (pintype "passive"))
      (node (ref "C69") (pin "2") (pinfunction "2_2") (pintype "passive"))
      (node (ref "C7") (pin "2") (pinfunction "2_2") (pintype "passive"))
      (node (ref "C71") (pin "2") (pinfunction "2_2") (pintype "passive"))
      (node (ref "C74") (pin "2") (pinfunction "2_2") (pintype "passive"))
      (node (ref "C75") (pin "2") (pinfunction "2_2") (pintype "passive"))
      (node (ref "C76") (pin "2") (pinfunction "2_2") (pintype "passive"))
      (node (ref "C77") (pin "2") (pinfunction "2_2") (pintype "passive"))
      (node (ref "C78") (pin "2") (pinfunction "2_2") (pintype "passive"))
      (node (ref "C79") (pin "2") (pinfunction "2_2") (pintype "passive"))
      (node (ref "C80") (pin "2") (pinfunction "2_2") (pintype "passive"))
      (node (ref "C81") (pin "2") (pinfunction "2_2") (pintype "passive"))
      (node (ref "C82") (pin "2") (pinfunction "2_2") (pintype "passive"))
      (node (ref "C83") (pin "2") (pinfunction "2_2") (pintype "passive"))
      (node (ref "C84") (pin "2") (pinfunction "2_2") (pintype "passive"))
      (node (ref "C85") (pin "2") (pinfunction "2_2") (pintype "passive"))
      (node (ref "C86") (pin "2") (pinfunction "2_2") (pintype "passive"))
      (node (ref "C87") (pin "2") (pinfunction "2_2") (pintype "passive"))
      (node (ref "C88") (pin "2") (pinfunction "2_2") (pintype "passive"))
      (node (ref "C89") (pin "2") (pinfunction "2_2") (pintype "passive"))
      (node (ref "C90") (pin "2") (pinfunction "2_2") (pintype "passive"))
      (node (ref "C91") (pin "2") (pinfunction "2_2") (pintype "passive"))
      (node (ref "C92") (pin "2") (pinfunction "2_2") (pintype "passive"))
      (node (ref "C93") (pin "2") (pinfunction "2_2") (pintype "passive"))
      (node (ref "C94") (pin "2") (pinfunction "2_2") (pintype "passive"))
      (node (ref "C95") (pin "2") (pinfunction "2_2") (pintype "passive"))
      (node (ref "C96") (pin "2") (pinfunction "2_2") (pintype "passive"))
      (node (ref "C97") (pin "2") (pinfunction "2_2") (pintype "passive"))
      (node (ref "C98") (pin "2") (pinfunction "2_2") (pintype "passive"))
      (node (ref "C99") (pin "1") (pinfunction "1_1") (pintype "passive"))
      (node (ref "DBG1") (pin "2") (pinfunction "P$2_2") (pintype "bidirectional"))
      (node (ref "DBG1") (pin "4") (pinfunction "P$4_4") (pintype "bidirectional"))
      (node (ref "DBG2") (pin "2") (pinfunction "P$2_2") (pintype "bidirectional"))
      (node (ref "DBG2") (pin "4") (pinfunction "P$4_4") (pintype "bidirectional"))
      (node (ref "ESD1") (pin "1") (pinfunction "A_1") (pintype "bidirectional"))
      (node (ref "IC1") (pin "2") (pinfunction "GND_2") (pintype "bidirectional"))
      (node (ref "IC10") (pin "11") (pinfunction "GND_11") (pintype "power_in"))
      (node (ref "IC10") (pin "27") (pinfunction "GND_27") (pintype "power_in"))
      (node (ref "IC10") (pin "30") (pinfunction "GND_30") (pintype "power_in"))
      (node (ref "IC10") (pin "33") (pinfunction "PAD_33") (pintype "power_in"))
      (node (ref "IC10") (pin "4") (pinfunction "GND_4") (pintype "power_in"))
      (node (ref "IC11") (pin "2") (pinfunction "V-_2") (pintype "power_in"))
      (node (ref "IC12") (pin "3") (pinfunction "GND_3") (pintype "bidirectional"))
      (node (ref "IC13") (pin "2") (pinfunction "V-_2") (pintype "power_in"))
      (node (ref "IC14") (pin "19") (pinfunction "AGND_19") (pintype "power_in"))
      (node (ref "IC14") (pin "2") (pinfunction "PGND_2") (pintype "power_in"))
      (node (ref "IC14") (pin "25") (pinfunction "PGND_25") (pintype "power_in"))
      (node (ref "IC14") (pin "3") (pinfunction "PGND_3") (pintype "power_in"))
      (node (ref "IC15") (pin "4") (pinfunction "GND_4") (pintype "power_in"))
      (node (ref "IC15") (pin "PAD") (pinfunction "PAD_PAD") (pintype "power_in"))
      (node (ref "IC15") (pin "PAD1") (pinfunction "PAD_PAD1") (pintype "power_in"))
      (node (ref "IC15") (pin "PAD2") (pinfunction "PAD_PAD2") (pintype "power_in"))
      (node (ref "IC15") (pin "PAD3") (pinfunction "PAD_PAD3") (pintype "power_in"))
      (node (ref "IC15") (pin "PAD4") (pinfunction "PAD_PAD4") (pintype "power_in"))
      (node (ref "IC16") (pin "4") (pinfunction "GND_4") (pintype "power_in"))
      (node (ref "IC17") (pin "3") (pinfunction "V-_3") (pintype "bidirectional"))
      (node (ref "IC2") (pin "19") (pinfunction "TESTEN_19") (pintype "bidirectional"))
      (node (ref "IC2") (pin "57") (pinfunction "GND_57") (pintype "bidirectional"))
      (node (ref "IC22") (pin "14") (pinfunction "GND_14") (pintype "power_in"))
      (node (ref "IC23") (pin "2") (pinfunction "V-_2") (pintype "power_in"))
      (node (ref "IC24") (pin "2") (pinfunction "V-_2") (pintype "power_in"))
      (node (ref "IC25") (pin "2") (pinfunction "V-_2") (pintype "power_in"))
      (node (ref "IC26") (pin "2") (pinfunction "V-_2") (pintype "power_in"))
      (node (ref "IC27") (pin "2") (pinfunction "V-_2") (pintype "power_in"))
      (node (ref "IC3") (pin "5") (pinfunction "V-_5") (pintype "power_in"))
      (node (ref "IC4") (pin "4") (pinfunction "GND_4") (pintype "power_in"))
      (node (ref "IC6") (pin "15") (pinfunction "GND_15") (pintype "power_in"))
      (node (ref "IC7") (pin "22") (pinfunction "AVSS_22") (pintype "power_in"))
      (node (ref "IC7") (pin "24") (pinfunction "IOUT_LV_24") (pintype "output"))
      (node (ref "IC7") (pin "25") (pinfunction "IOUT_HV_25") (pintype "output"))
      (node (ref "IC7") (pin "4") (pinfunction "IN2-_4") (pintype "input"))
      (node (ref "IC7") (pin "6") (pinfunction "DVSS_6") (pintype "power_in"))
      (node (ref "IC8") (pin "15") (pinfunction "GND_15") (pintype "power_in"))
      (node (ref "IC9") (pin "22") (pinfunction "AVSS_22") (pintype "power_in"))
      (node (ref "IC9") (pin "24") (pinfunction "IOUT_LV_24") (pintype "output"))
      (node (ref "IC9") (pin "25") (pinfunction "IOUT_HV_25") (pintype "output"))
      (node (ref "IC9") (pin "4") (pinfunction "IN2-_4") (pintype "input"))
      (node (ref "IC9") (pin "6") (pinfunction "DVSS_6") (pintype "power_in"))
      (node (ref "J1") (pin "18") (pinfunction "18_18") (pintype "bidirectional"))
      (node (ref "J1") (pin "19") (pinfunction "19_19") (pintype "bidirectional"))
      (node (ref "J1") (pin "22") (pinfunction "22_22") (pintype "bidirectional"))
      (node (ref "J1") (pin "24") (pinfunction "24_24") (pintype "bidirectional"))
      (node (ref "J1") (pin "26") (pinfunction "26_26") (pintype "bidirectional"))
      (node (ref "J1") (pin "28") (pinfunction "28_28") (pintype "bidirectional"))
      (node (ref "J1") (pin "30") (pinfunction "30_30") (pintype "bidirectional"))
      (node (ref "J1") (pin "32") (pinfunction "32_32") (pintype "bidirectional"))
      (node (ref "J1") (pin "34") (pinfunction "34_34") (pintype "bidirectional"))
      (node (ref "J1") (pin "36") (pinfunction "36_36") (pintype "bidirectional"))
      (node (ref "J1") (pin "MH1") (pinfunction "MH1_MH1") (pintype "bidirectional"))
      (node (ref "J1") (pin "MH2") (pinfunction "MH2_MH2") (pintype "bidirectional"))
      (node (ref "L4") (pin "1") (pinfunction "1_1") (pintype "passive"))
      (node (ref "R103") (pin "1") (pinfunction "1_1") (pintype "passive"))
      (node (ref "R107") (pin "1") (pinfunction "1_1") (pintype "passive"))
      (node (ref "R111") (pin "1") (pinfunction "1_1") (pintype "passive"))
      (node (ref "R115") (pin "1") (pinfunction "1_1") (pintype "passive"))
      (node (ref "R12") (pin "2") (pinfunction "2_2") (pintype "passive"))
      (node (ref "R57") (pin "2") (pinfunction "2_2") (pintype "passive"))
      (node (ref "R61") (pin "2") (pinfunction "2_2") (pintype "passive"))
      (node (ref "R62") (pin "2") (pinfunction "2_2") (pintype "passive"))
      (node (ref "R64") (pin "2") (pinfunction "2_2") (pintype "passive"))
      (node (ref "R68") (pin "2") (pinfunction "2_2") (pintype "passive"))
      (node (ref "R69") (pin "2") (pinfunction "2_2") (pintype "passive"))
      (node (ref "R71") (pin "2") (pinfunction "2_2") (pintype "passive"))
      (node (ref "R73") (pin "2") (pinfunction "2_2") (pintype "passive"))
      (node (ref "R77") (pin "1") (pinfunction "1_1") (pintype "passive"))
      (node (ref "R87") (pin "1") (pinfunction "1_1") (pintype "passive"))
      (node (ref "R91") (pin "1") (pinfunction "1_1") (pintype "passive"))
      (node (ref "R95") (pin "1") (pinfunction "1_1") (pintype "passive"))
      (node (ref "R99") (pin "1") (pinfunction "1_1") (pintype "passive"))
      (node (ref "REF1") (pin "2") (pinfunction "A_2") (pintype "passive"))
      (node (ref "REF1") (pin "3") (pinfunction "A_3") (pintype "passive"))
      (node (ref "RESET") (pin "2") (pinfunction "S_2") (pintype "passive"))
      (node (ref "TP_GND") (pin "TP") (pinfunction "P$1_TP") (pintype "bidirectional"))
      (node (ref "USBC") (pin "A1") (pinfunction "GND_A1") (pintype "passive"))
      (node (ref "USBC") (pin "A12") (pinfunction "GND1_A12") (pintype "passive"))
      (node (ref "USBC") (pin "B1") (pinfunction "GND3_B1") (pintype "passive"))
      (node (ref "USBC") (pin "B12") (pinfunction "GND2_B12") (pintype "passive"))
      (node (ref "USB_BOOT") (pin "2") (pinfunction "S_2") (pintype "passive"))
      (node (ref "X1") (pin "A10") (pinfunction "10_A10") (pintype "passive"))
      (node (ref "X1") (pin "A14") (pinfunction "14_A14") (pintype "passive"))
      (node (ref "X1") (pin "A15") (pinfunction "15_A15") (pintype "passive"))
      (node (ref "X1") (pin "A16") (pinfunction "16_A16") (pintype "passive"))
      (node (ref "X1") (pin "A25") (pinfunction "25_A25") (pintype "passive"))
      (node (ref "X1") (pin "A30") (pinfunction "30_A30") (pintype "passive"))
      (node (ref "X1") (pin "A31") (pinfunction "31_A31") (pintype "passive"))
      (node (ref "X1") (pin "A32") (pinfunction "32_A32") (pintype "passive"))
      (node (ref "X1") (pin "B10") (pinfunction "10_B10") (pintype "passive"))
      (node (ref "X1") (pin "B14") (pinfunction "14_B14") (pintype "passive"))
      (node (ref "X1") (pin "B15") (pinfunction "15_B15") (pintype "passive"))
      (node (ref "X1") (pin "B16") (pinfunction "16_B16") (pintype "passive"))
      (node (ref "X1") (pin "B19") (pinfunction "19_B19") (pintype "passive"))
      (node (ref "X1") (pin "B22") (pinfunction "22_B22") (pintype "passive"))
      (node (ref "X1") (pin "B25") (pinfunction "25_B25") (pintype "passive"))
      (node (ref "X1") (pin "B30") (pinfunction "30_B30") (pintype "passive"))
      (node (ref "X1") (pin "B31") (pinfunction "31_B31") (pintype "passive"))
      (node (ref "X1") (pin "B32") (pinfunction "32_B32") (pintype "passive"))
      (node (ref "X2") (pin "2") (pinfunction "VSS_2") (pintype "power_in"))
      (node (ref "X2") (pin "4") (pinfunction "VDD_4") (pintype "power_in"))
    )
    (net (code "76") (name "IN0+") (class "Default")
      (node (ref "C1") (pin "1") (pinfunction "1_1") (pintype "passive"))
      (node (ref "IC6") (pin "4") (pinfunction "IN_A_0_4") (pintype "input"))
      (node (ref "R25") (pin "2") (pinfunction "2_2") (pintype "passive"))
    )
    (net (code "77") (name "IN1-") (class "Default")
      (node (ref "C2") (pin "1") (pinfunction "1_1") (pintype "passive"))
      (node (ref "IC6") (pin "13") (pinfunction "IN_B_0_13") (pintype "input"))
      (node (ref "R26") (pin "2") (pinfunction "2_2") (pintype "passive"))
    )
    (net (code "78") (name "IN2+") (class "Default")
      (node (ref "C3") (pin "1") (pinfunction "1_1") (pintype "passive"))
      (node (ref "IC6") (pin "5") (pinfunction "IN_A_1_5") (pintype "input"))
      (node (ref "R27") (pin "2") (pinfunction "2_2") (pintype "passive"))
    )
    (net (code "79") (name "IN3-") (class "Default")
      (node (ref "C28") (pin "1") (pinfunction "1_1") (pintype "passive"))
      (node (ref "IC6") (pin "12") (pinfunction "IN_B_1_12") (pintype "input"))
      (node (ref "R28") (pin "2") (pinfunction "2_2") (pintype "passive"))
    )
    (net (code "80") (name "IN4+") (class "Default")
      (node (ref "C29") (pin "1") (pinfunction "1_1") (pintype "passive"))
      (node (ref "IC6") (pin "6") (pinfunction "IN_A_2_6") (pintype "input"))
      (node (ref "R29") (pin "2") (pinfunction "2_2") (pintype "passive"))
    )
    (net (code "81") (name "IN5-") (class "Default")
      (node (ref "C30") (pin "1") (pinfunction "1_1") (pintype "passive"))
      (node (ref "IC6") (pin "11") (pinfunction "IN_B_2_11") (pintype "input"))
      (node (ref "R30") (pin "2") (pinfunction "2_2") (pintype "passive"))
    )
    (net (code "82") (name "IN6+") (class "Default")
      (node (ref "C31") (pin "1") (pinfunction "1_1") (pintype "passive"))
      (node (ref "IC6") (pin "7") (pinfunction "IN_A_3_7") (pintype "input"))
      (node (ref "R31") (pin "2") (pinfunction "2_2") (pintype "passive"))
    )
    (net (code "83") (name "IN7-") (class "Default")
      (node (ref "C32") (pin "1") (pinfunction "1_1") (pintype "passive"))
      (node (ref "IC6") (pin "10") (pinfunction "IN_B_3_10") (pintype "input"))
      (node (ref "R32") (pin "2") (pinfunction "2_2") (pintype "passive"))
    )
    (net (code "84") (name "IN8+") (class "Default")
      (node (ref "C33") (pin "1") (pinfunction "1_1") (pintype "passive"))
      (node (ref "IC8") (pin "4") (pinfunction "IN_A_0_4") (pintype "input"))
      (node (ref "R33") (pin "2") (pinfunction "2_2") (pintype "passive"))
    )
    (net (code "85") (name "IN9-") (class "Default")
      (node (ref "C34") (pin "1") (pinfunction "1_1") (pintype "passive"))
      (node (ref "IC8") (pin "13") (pinfunction "IN_B_0_13") (pintype "input"))
      (node (ref "R34") (pin "2") (pinfunction "2_2") (pintype "passive"))
    )
    (net (code "86") (name "IN10+") (class "Default")
      (node (ref "C35") (pin "1") (pinfunction "1_1") (pintype "passive"))
      (node (ref "IC8") (pin "5") (pinfunction "IN_A_1_5") (pintype "input"))
      (node (ref "R35") (pin "2") (pinfunction "2_2") (pintype "passive"))
    )
    (net (code "87") (name "IN11-") (class "Default")
      (node (ref "C36") (pin "1") (pinfunction "1_1") (pintype "passive"))
      (node (ref "IC8") (pin "12") (pinfunction "IN_B_1_12") (pintype "input"))
      (node (ref "R36") (pin "2") (pinfunction "2_2") (pintype "passive"))
    )
    (net (code "88") (name "IN12+") (class "Default")
      (node (ref "C37") (pin "1") (pinfunction "1_1") (pintype "passive"))
      (node (ref "IC8") (pin "6") (pinfunction "IN_A_2_6") (pintype "input"))
      (node (ref "R37") (pin "2") (pinfunction "2_2") (pintype "passive"))
    )
    (net (code "89") (name "IN13-") (class "Default")
      (node (ref "C38") (pin "1") (pinfunction "1_1") (pintype "passive"))
      (node (ref "IC8") (pin "11") (pinfunction "IN_B_2_11") (pintype "input"))
      (node (ref "R38") (pin "2") (pinfunction "2_2") (pintype "passive"))
    )
    (net (code "90") (name "IN14+") (class "Default")
      (node (ref "C39") (pin "1") (pinfunction "1_1") (pintype "passive"))
      (node (ref "IC8") (pin "7") (pinfunction "IN_A_3_7") (pintype "input"))
      (node (ref "R40") (pin "2") (pinfunction "2_2") (pintype "passive"))
    )
    (net (code "91") (name "IN15-") (class "Default")
      (node (ref "C40") (pin "1") (pinfunction "1_1") (pintype "passive"))
      (node (ref "IC8") (pin "10") (pinfunction "IN_B_3_10") (pintype "input"))
      (node (ref "R41") (pin "2") (pinfunction "2_2") (pintype "passive"))
    )
    (net (code "92") (name "MISO_SEL") (class "Default")
      (node (ref "IC16") (pin "7") (pinfunction "1C_7") (pintype "input"))
      (node (ref "IC17") (pin "2") (pinfunction "IN_2") (pintype "bidirectional"))
      (node (ref "IC2") (pin "36") (pinfunction "GPIO24_36") (pintype "bidirectional"))
      (node (ref "X1") (pin "A13") (pinfunction "13_A13") (pintype "passive"))
    )
    (net (code "93") (name "MUX_A_OUTA") (class "Default")
      (node (ref "IC6") (pin "8") (pinfunction "OUT_A_8") (pintype "output"))
      (node (ref "R43") (pin "2") (pinfunction "2_2") (pintype "passive"))
    )
    (net (code "94") (name "MUX_A_OUTB") (class "Default")
      (node (ref "IC6") (pin "9") (pinfunction "OUT_B_9") (pintype "output"))
      (node (ref "R44") (pin "1") (pinfunction "1_1") (pintype "passive"))
    )
    (net (code "95") (name "MUX_B_OUTA") (class "Default")
      (node (ref "IC8") (pin "8") (pinfunction "OUT_A_8") (pintype "output"))
      (node (ref "R24") (pin "2") (pinfunction "2_2") (pintype "passive"))
    )
    (net (code "96") (name "MUX_B_OUTB") (class "Default")
      (node (ref "IC8") (pin "9") (pinfunction "OUT_B_9") (pintype "output"))
      (node (ref "R42") (pin "1") (pinfunction "1_1") (pintype "passive"))
    )
    (net (code "97") (name "Net-(C8-Pad1)") (class "Default")
      (node (ref "C8") (pin "1") (pinfunction "1_1") (pintype "passive"))
      (node (ref "R2") (pin "2") (pinfunction "2_2") (pintype "passive"))
    )
    (net (code "98") (name "Net-(C9-Pad1)") (class "Default")
      (node (ref "C9") (pin "1") (pinfunction "1_1") (pintype "passive"))
      (node (ref "R3") (pin "2") (pinfunction "2_2") (pintype "passive"))
    )
    (net (code "99") (name "Net-(C10-Pad1)") (class "Default")
      (node (ref "C10") (pin "1") (pinfunction "1_1") (pintype "passive"))
      (node (ref "R4") (pin "2") (pinfunction "2_2") (pintype "passive"))
    )
    (net (code "100") (name "Net-(C11-Pad1)") (class "Default")
      (node (ref "C11") (pin "1") (pinfunction "1_1") (pintype "passive"))
      (node (ref "R5") (pin "2") (pinfunction "2_2") (pintype "passive"))
    )
    (net (code "101") (name "Net-(C12-Pad1)") (class "Default")
      (node (ref "C12") (pin "1") (pinfunction "1_1") (pintype "passive"))
      (node (ref "R6") (pin "2") (pinfunction "2_2") (pintype "passive"))
    )
    (net (code "102") (name "Net-(C13-Pad1)") (class "Default")
      (node (ref "C13") (pin "1") (pinfunction "1_1") (pintype "passive"))
      (node (ref "R7") (pin "2") (pinfunction "2_2") (pintype "passive"))
    )
    (net (code "103") (name "Net-(C14-Pad1)") (class "Default")
      (node (ref "C14") (pin "1") (pinfunction "1_1") (pintype "passive"))
      (node (ref "R8") (pin "2") (pinfunction "2_2") (pintype "passive"))
    )
    (net (code "104") (name "Net-(C72-Pad2)") (class "Default")
      (node (ref "C72") (pin "2") (pinfunction "2_2") (pintype "passive"))
      (node (ref "C73") (pin "2") (pinfunction "2_2") (pintype "passive"))
      (node (ref "R49") (pin "1") (pinfunction "1_1") (pintype "passive"))
    )
    (net (code "105") (name "Net-(C74-Pad1)") (class "Default")
      (node (ref "C74") (pin "1") (pinfunction "1_1") (pintype "passive"))
      (node (ref "R49") (pin "2") (pinfunction "2_2") (pintype "bidirectional"))
      (node (ref "R50") (pin "1") (pinfunction "1_1") (pintype "passive"))
    )
    (net (code "106") (name "Net-(C129-Pad1)") (class "Default")
      (node (ref "C129") (pin "1") (pinfunction "1_1") (pintype "passive"))
      (node (ref "R1") (pin "2") (pinfunction "2_2") (pintype "passive"))
    )
    (net (code "107") (name "Net-(D3-PadA)") (class "Default")
      (node (ref "D3") (pin "A") (pinfunction "A_A") (pintype "passive"))
      (node (ref "IC14") (pin "1") (pinfunction "INP_1") (pintype "power_in"))
      (node (ref "IC14") (pin "24") (pinfunction "INP_24") (pintype "power_in"))
      (node (ref "L3") (pin "2") (pinfunction "2_2") (pintype "passive"))
    )
    (net (code "108") (name "Net-(D4-PadC)") (class "Default")
      (node (ref "D4") (pin "C") (pinfunction "C_C") (pintype "passive"))
      (node (ref "IC14") (pin "13") (pinfunction "OUTN_13") (pintype "power_in"))
      (node (ref "IC14") (pin "14") (pinfunction "OUTN_14") (pintype "power_in"))
      (node (ref "L4") (pin "2") (pinfunction "2_2") (pintype "passive"))
    )
    (net (code "109") (name "Net-(IC2-USB_DM)") (class "Default")
      (node (ref "IC2") (pin "46") (pinfunction "USB_DM_46") (pintype "bidirectional"))
      (node (ref "R13") (pin "2") (pinfunction "2_2") (pintype "passive"))
    )
    (net (code "110") (name "Net-(IC2-USB_DP)") (class "Default")
      (node (ref "IC2") (pin "47") (pinfunction "USB_DP_47") (pintype "bidirectional"))
      (node (ref "R39") (pin "2") (pinfunction "2_2") (pintype "passive"))
    )
    (net (code "111") (name "Net-(IC3-+IN)") (class "Default")
      (node (ref "C15") (pin "1") (pinfunction "1_1") (pintype "passive"))
      (node (ref "C16") (pin "1") (pinfunction "1_1") (pintype "passive"))
      (node (ref "IC3") (pin "3") (pinfunction "+IN_3") (pintype "input"))
      (node (ref "R17") (pin "1") (pinfunction "1_1") (pintype "passive"))
      (node (ref "REF1") (pin "1") (pinfunction "C_1") (pintype "passive"))
      (node (ref "VREF1") (pin "TP") (pinfunction "P$1_TP") (pintype "bidirectional"))
    )
    (net (code "112") (name "Net-(IC7-OUT+)") (class "Default")
      (node (ref "IC7") (pin "19") (pinfunction "OUT+_19") (pintype "output"))
      (node (ref "R20") (pin "2") (pinfunction "2_2") (pintype "passive"))
    )
    (net (code "113") (name "Net-(IC7-OUT-)") (class "Default")
      (node (ref "IC7") (pin "20") (pinfunction "OUT-_20") (pintype "output"))
      (node (ref "R21") (pin "2") (pinfunction "2_2") (pintype "passive"))
    )
    (net (code "114") (name "Net-(IC9-OUT+)") (class "Default")
      (node (ref "IC9") (pin "19") (pinfunction "OUT+_19") (pintype "output"))
      (node (ref "R22") (pin "2") (pinfunction "2_2") (pintype "passive"))
    )
    (net (code "115") (name "Net-(IC9-OUT-)") (class "Default")
      (node (ref "IC9") (pin "20") (pinfunction "OUT-_20") (pintype "output"))
      (node (ref "R23") (pin "2") (pinfunction "2_2") (pintype "passive"))
    )
    (net (code "116") (name "Net-(IC10-CONVST)") (class "Default")
      (node (ref "IC10") (pin "13") (pinfunction "CONVST_13") (pintype "input"))
      (node (ref "R15") (pin "2") (pinfunction "2_2") (pintype "passive"))
    )
    (net (code "117") (name "Net-(IC11-+IN)") (class "Default")
      (node (ref "IC11") (pin "3") (pinfunction "+IN_3") (pintype "input"))
      (node (ref "R50") (pin "2") (pinfunction "2_2") (pintype "passive"))
    )
    (net (code "118") (name "Net-(IC14-CN)") (class "Default")
      (node (ref "C92") (pin "1") (pinfunction "1_1") (pintype "passive"))
      (node (ref "IC14") (pin "18") (pinfunction "CN_18") (pintype "input"))
    )
    (net (code "119") (name "Net-(IC14-CP)") (class "Default")
      (node (ref "C91") (pin "1") (pinfunction "1_1") (pintype "passive"))
      (node (ref "IC14") (pin "21") (pinfunction "CP_21") (pintype "input"))
    )
    (net (code "120") (name "Net-(IC14-ENN)") (class "Default")
      (node (ref "C86") (pin "1") (pinfunction "1_1") (pintype "passive"))
      (node (ref "IC14") (pin "10") (pinfunction "ENN_10") (pintype "input"))
      (node (ref "IC14") (pin "11") (pinfunction "PSN_11") (pintype "input"))
      (node (ref "IC14") (pin "4") (pinfunction "VIN_4") (pintype "power_in"))
      (node (ref "IC14") (pin "8") (pinfunction "ENP_8") (pintype "input"))
      (node (ref "IC14") (pin "9") (pinfunction "PSP_9") (pintype "input"))
      (node (ref "R14") (pin "1") (pinfunction "1_1") (pintype "passive"))
    )
    (net (code "121") (name "Net-(IC15-NR{slash}SS)") (class "Default")
      (node (ref "C103") (pin "1") (pinfunction "1_1") (pintype "passive"))
      (node (ref "IC15") (pin "3") (pinfunction "NR/SS_3") (pintype "input"))
    )
    (net (code "122") (name "Net-(IC16-2C)") (class "Default")
      (node (ref "IC16") (pin "3") (pinfunction "2C_3") (pintype "input"))
      (node (ref "IC17") (pin "4") (pinfunction "OUT_4") (pintype "bidirectional"))
    )
    (net (code "123") (name "Net-(IC24-OUT)") (class "Default")
      (node (ref "IC24") (pin "1") (pinfunction "OUT_1") (pintype "output"))
      (node (ref "R1") (pin "1") (pinfunction "1_1") (pintype "passive"))
      (node (ref "R90") (pin "1") (pinfunction "1_1") (pintype "passive"))
    )
    (net (code "124") (name "Net-(IC25-OUT)") (class "Default")
      (node (ref "IC25") (pin "1") (pinfunction "OUT_1") (pintype "output"))
      (node (ref "R2") (pin "1") (pinfunction "1_1") (pintype "passive"))
      (node (ref "R94") (pin "1") (pinfunction "1_1") (pintype "passive"))
    )
    (net (code "125") (name "Net-(IC26-OUT)") (class "Default")
      (node (ref "IC26") (pin "1") (pinfunction "OUT_1") (pintype "output"))
      (node (ref "R3") (pin "1") (pinfunction "1_1") (pintype "passive"))
      (node (ref "R98") (pin "1") (pinfunction "1_1") (pintype "passive"))
    )
    (net (code "126") (name "Net-(IC27-OUT)") (class "Default")
      (node (ref "IC27") (pin "1") (pinfunction "OUT_1") (pintype "output"))
      (node (ref "R102") (pin "1") (pinfunction "1_1") (pintype "passive"))
      (node (ref "R4") (pin "1") (pinfunction "1_1") (pintype "passive"))
    )
    (net (code "127") (name "Net-(IC28-OUT)") (class "Default")
      (node (ref "IC28") (pin "1") (pinfunction "OUT_1") (pintype "output"))
      (node (ref "R106") (pin "1") (pinfunction "1_1") (pintype "passive"))
      (node (ref "R8") (pin "1") (pinfunction "1_1") (pintype "passive"))
    )
    (net (code "128") (name "Net-(IC29-OUT)") (class "Default")
      (node (ref "IC29") (pin "1") (pinfunction "OUT_1") (pintype "output"))
      (node (ref "R110") (pin "1") (pinfunction "1_1") (pintype "passive"))
      (node (ref "R7") (pin "1") (pinfunction "1_1") (pintype "passive"))
    )
    (net (code "129") (name "Net-(IC30-OUT)") (class "Default")
      (node (ref "IC30") (pin "1") (pinfunction "OUT_1") (pintype "output"))
      (node (ref "R114") (pin "1") (pinfunction "1_1") (pintype "passive"))
      (node (ref "R6") (pin "1") (pinfunction "1_1") (pintype "passive"))
    )
    (net (code "130") (name "Net-(IC31-OUT)") (class "Default")
      (node (ref "IC31") (pin "1") (pinfunction "OUT_1") (pintype "output"))
      (node (ref "R118") (pin "1") (pinfunction "1_1") (pintype "passive"))
      (node (ref "R5") (pin "1") (pinfunction "1_1") (pintype "passive"))
    )
    (net (code "131") (name "Net-(R19-Pad2)") (class "Default")
      (node (ref "R19") (pin "2") (pinfunction "2_2") (pintype "passive"))
      (node (ref "R53") (pin "2") (pinfunction "2_2") (pintype "bidirectional"))
      (node (ref "R53") (pin "3") (pinfunction "3_3") (pintype "passive"))
    )
    (net (code "132") (name "Net-(R54-Pad2)") (class "Default")
      (node (ref "R54") (pin "2") (pinfunction "2_2") (pintype "bidirectional"))
      (node (ref "R54") (pin "3") (pinfunction "3_3") (pintype "passive"))
      (node (ref "R58") (pin "2") (pinfunction "2_2") (pintype "passive"))
    )
    (net (code "133") (name "Net-(R55-Pad2)") (class "Default")
      (node (ref "R55") (pin "2") (pinfunction "2_2") (pintype "bidirectional"))
      (node (ref "R55") (pin "3") (pinfunction "3_3") (pintype "passive"))
      (node (ref "R60") (pin "2") (pinfunction "2_2") (pintype "passive"))
    )
    (net (code "134") (name "Net-(R56-Pad2)") (class "Default")
      (node (ref "R56") (pin "2") (pinfunction "2_2") (pintype "bidirectional"))
      (node (ref "R56") (pin "3") (pinfunction "3_3") (pintype "passive"))
      (node (ref "R74") (pin "2") (pinfunction "2_2") (pintype "passive"))
    )
    (net (code "135") (name "Net-(T2-D)") (class "Default")
      (node (ref "C90") (pin "1") (pinfunction "1_1") (pintype "passive"))
      (node (ref "L3") (pin "1") (pinfunction "1_1") (pintype "passive"))
      (node (ref "T2") (pin "3") (pinfunction "D_3") (pintype "passive"))
    )
    (net (code "136") (name "Net-(X1A-1)") (class "Default")
      (node (ref "JP-3V3-1") (pin "2") (pinfunction "2_2") (pintype "passive"))
      (node (ref "X1") (pin "A1") (pinfunction "1_A1") (pintype "passive"))
    )
    (net (code "137") (name "Net-(X1B-1)") (class "Default")
      (node (ref "JP-3V3-2") (pin "2") (pinfunction "2_2") (pintype "passive"))
      (node (ref "X1") (pin "B1") (pinfunction "1_B1") (pintype "passive"))
    )
    (net (code "138") (name "Net-(X2-OUT)") (class "Default")
      (node (ref "C20") (pin "1") (pinfunction "1_1") (pintype "passive"))
      (node (ref "R10") (pin "1") (pinfunction "1_1") (pintype "passive"))
      (node (ref "R9") (pin "2") (pinfunction "2_2") (pintype "passive"))
      (node (ref "X2") (pin "3") (pinfunction "OUT_3") (pintype "output"))
    )
    (net (code "139") (name "PGA_A_IN+") (class "Default")
      (node (ref "IC7") (pin "1") (pinfunction "IN1+_1") (pintype "input"))
      (node (ref "R43") (pin "1") (pinfunction "1_1") (pintype "passive"))
    )
    (net (code "140") (name "PGA_A_IN-") (class "Default")
      (node (ref "IC7") (pin "2") (pinfunction "IN1-_2") (pintype "input"))
      (node (ref "IC7") (pin "3") (pinfunction "IN2+_3") (pintype "input"))
      (node (ref "R44") (pin "2") (pinfunction "2_2") (pintype "passive"))
    )
    (net (code "141") (name "PGA_B_IN+") (class "Default")
      (node (ref "IC9") (pin "1") (pinfunction "IN1+_1") (pintype "input"))
      (node (ref "R24") (pin "1") (pinfunction "1_1") (pintype "passive"))
    )
    (net (code "142") (name "PGA_B_IN-") (class "Default")
      (node (ref "IC9") (pin "2") (pinfunction "IN1-_2") (pintype "input"))
      (node (ref "IC9") (pin "3") (pinfunction "IN2+_3") (pintype "input"))
      (node (ref "R42") (pin "2") (pinfunction "2_2") (pintype "passive"))
    )
    (net (code "143") (name "QSPI_SCLK") (class "Default")
      (node (ref "IC2") (pin "52") (pinfunction "QSPI_SCLK_52") (pintype "bidirectional"))
      (node (ref "IC4") (pin "6") (pinfunction "CLK_6") (pintype "bidirectional"))
    )
    (net (code "144") (name "QSPI_SD0") (class "Default")
      (node (ref "IC2") (pin "53") (pinfunction "QSPI_SD0_53") (pintype "bidirectional"))
      (node (ref "IC4") (pin "5") (pinfunction "DI/IO0_5") (pintype "bidirectional"))
    )
    (net (code "145") (name "QSPI_SD1") (class "Default")
      (node (ref "IC2") (pin "55") (pinfunction "QSPI_SD1_55") (pintype "bidirectional"))
      (node (ref "IC4") (pin "2") (pinfunction "DO/IO1_2") (pintype "bidirectional"))
    )
    (net (code "146") (name "QSPI_SD2") (class "Default")
      (node (ref "IC2") (pin "54") (pinfunction "QSPI_SD2_54") (pintype "bidirectional"))
      (node (ref "IC4") (pin "3") (pinfunction "~{WP}/IO2_3") (pintype "bidirectional"))
    )
    (net (code "147") (name "QSPI_SD3") (class "Default")
      (node (ref "IC2") (pin "51") (pinfunction "QSPI_SD3_51") (pintype "bidirectional"))
      (node (ref "IC4") (pin "7") (pinfunction "~{HOLD}/IO3_7") (pintype "bidirectional"))
    )
    (net (code "148") (name "REFBY2") (class "Default")
      (node (ref "C71") (pin "1") (pinfunction "1_1") (pintype "passive"))
      (node (ref "IC10") (pin "3") (pinfunction "REFBY2_3") (pintype "output"))
      (node (ref "REFBY2") (pin "TP") (pinfunction "P$1_TP") (pintype "bidirectional"))
    )
    (net (code "149") (name "REFM_A") (class "Default")
      (node (ref "C70") (pin "2") (pinfunction "2_2") (pintype "passive"))
      (node (ref "IC10") (pin "32") (pinfunction "REFM_A_32") (pintype "output"))
    )
    (net (code "150") (name "REFM_B") (class "Default")
      (node (ref "C110") (pin "2") (pinfunction "2_2") (pintype "passive"))
      (node (ref "IC10") (pin "9") (pinfunction "REFM_B_9") (pintype "output"))
    )
    (net (code "151") (name "REFOUT") (class "Default")
      (node (ref "C111") (pin "1") (pinfunction "1_1") (pintype "passive"))
      (node (ref "IC10") (pin "5") (pinfunction "REFOUT_5") (pintype "output"))
      (node (ref "REFOUT") (pin "TP") (pinfunction "P$1_TP") (pintype "bidirectional"))
    )
    (net (code "152") (name "REFP_A") (class "Default")
      (node (ref "C70") (pin "1") (pinfunction "1_1") (pintype "passive"))
      (node (ref "IC10") (pin "31") (pinfunction "REFP_A_31") (pintype "output"))
    )
    (net (code "153") (name "REFP_B") (class "Default")
      (node (ref "C110") (pin "1") (pinfunction "1_1") (pintype "passive"))
      (node (ref "IC10") (pin "10") (pinfunction "REFP_B_10") (pintype "output"))
    )
    (net (code "154") (name "RP2040_RST") (class "Default")
      (node (ref "IC2") (pin "26") (pinfunction "RUN_26") (pintype "bidirectional"))
      (node (ref "R75") (pin "2") (pinfunction "2_2") (pintype "passive"))
      (node (ref "RESET") (pin "1") (pinfunction "P_1") (pintype "passive"))
      (node (ref "X1") (pin "B18") (pinfunction "18_B18") (pintype "passive"))
    )
    (net (code "155") (name "RP_XI") (class "Default")
      (node (ref "C19") (pin "1") (pinfunction "1_1") (pintype "passive"))
      (node (ref "IC2") (pin "20") (pinfunction "XIN_20") (pintype "bidirectional"))
      (node (ref "R9") (pin "1") (pinfunction "1_1") (pintype "passive"))
      (node (ref "X2") (pin "1") (pinfunction "CON_1") (pintype "input"))
    )
    (net (code "156") (name "RP_XO") (class "Default")
      (node (ref "IC2") (pin "21") (pinfunction "XOUT_21") (pintype "bidirectional"))
      (node (ref "R10") (pin "2") (pinfunction "2_2") (pintype "passive"))
    )
    (net (code "157") (name "SDO_A_0") (class "Default")
      (node (ref "IC10") (pin "24") (pinfunction "SDO-0/0A_24") (pintype "output"))
      (node (ref "IC16") (pin "1") (pinfunction "1A_1") (pintype "bidirectional"))
      (node (ref "IC2") (pin "27") (pinfunction "GPIO16_27") (pintype "bidirectional"))
      (node (ref "X1") (pin "A17") (pinfunction "17_A17") (pintype "passive"))
    )
    (net (code "158") (name "SDO_A_1") (class "Default")
      (node (ref "IC10") (pin "23") (pinfunction "SDO-1/1A_23") (pintype "output"))
      (node (ref "IC2") (pin "28") (pinfunction "GPIO17_28") (pintype "bidirectional"))
      (node (ref "X1") (pin "A18") (pinfunction "18_A18") (pintype "passive"))
    )
    (net (code "159") (name "SDO_A_2") (class "Default")
      (node (ref "IC10") (pin "22") (pinfunction "SDO-2/2A_22") (pintype "output"))
      (node (ref "IC2") (pin "29") (pinfunction "GPIO18_29") (pintype "bidirectional"))
      (node (ref "X1") (pin "A19") (pinfunction "19_A19") (pintype "passive"))
    )
    (net (code "160") (name "SDO_A_3") (class "Default")
      (node (ref "IC10") (pin "21") (pinfunction "SDO-3/3A_21") (pintype "output"))
      (node (ref "IC2") (pin "30") (pinfunction "GPIO19_30") (pintype "bidirectional"))
      (node (ref "X1") (pin "A20") (pinfunction "20_A20") (pintype "passive"))
    )
    (net (code "161") (name "SDO_B_0") (class "Default")
      (node (ref "IC10") (pin "20") (pinfunction "SDO-4/0B_20") (pintype "output"))
      (node (ref "IC16") (pin "5") (pinfunction "2A_5") (pintype "bidirectional"))
      (node (ref "IC2") (pin "31") (pinfunction "GPIO20_31") (pintype "bidirectional"))
      (node (ref "X1") (pin "A21") (pinfunction "21_A21") (pintype "passive"))
    )
    (net (code "162") (name "SDO_B_1") (class "Default")
      (node (ref "IC10") (pin "19") (pinfunction "SDO-5/1B_19") (pintype "output"))
      (node (ref "IC2") (pin "32") (pinfunction "GPIO21_32") (pintype "bidirectional"))
      (node (ref "X1") (pin "A22") (pinfunction "22_A22") (pintype "passive"))
    )
    (net (code "163") (name "SDO_B_2") (class "Default")
      (node (ref "IC10") (pin "18") (pinfunction "SDO-6/2B_18") (pintype "output"))
      (node (ref "IC2") (pin "34") (pinfunction "GPIO22_34") (pintype "bidirectional"))
      (node (ref "X1") (pin "A23") (pinfunction "23_A23") (pintype "passive"))
    )
    (net (code "164") (name "SDO_B_3") (class "Default")
      (node (ref "IC10") (pin "17") (pinfunction "SDO-7/3B_17") (pintype "output"))
      (node (ref "IC2") (pin "35") (pinfunction "GPIO23_35") (pintype "bidirectional"))
      (node (ref "X1") (pin "A24") (pinfunction "24_A24") (pintype "passive"))
    )
    (net (code "165") (name "SPI0_CS0") (class "Default")
      (node (ref "CS0") (pin "TP") (pinfunction "P$1_TP") (pintype "bidirectional"))
      (node (ref "IC10") (pin "14") (pinfunction "~{CS}_14") (pintype "input"))
      (node (ref "IC2") (pin "7") (pinfunction "GPIO5_7") (pintype "bidirectional"))
      (node (ref "R15") (pin "1") (pinfunction "1_1") (pintype "passive"))
      (node (ref "X1") (pin "A2") (pinfunction "2_A2") (pintype "passive"))
    )
    (net (code "166") (name "SPI0_CS1") (class "Default")
      (node (ref "CS1") (pin "TP") (pinfunction "P$1_TP") (pintype "bidirectional"))
      (node (ref "IC2") (pin "8") (pinfunction "GPIO6_8") (pintype "bidirectional"))
      (node (ref "IC7") (pin "11") (pinfunction "~{CS}_11") (pintype "bidirectional"))
      (node (ref "X1") (pin "A3") (pinfunction "3_A3") (pintype "passive"))
    )
    (net (code "167") (name "SPI0_CS2") (class "Default")
      (node (ref "CS2") (pin "TP") (pinfunction "P$1_TP") (pintype "bidirectional"))
      (node (ref "IC2") (pin "9") (pinfunction "GPIO7_9") (pintype "bidirectional"))
      (node (ref "IC9") (pin "11") (pinfunction "~{CS}_11") (pintype "bidirectional"))
      (node (ref "X1") (pin "A4") (pinfunction "4_A4") (pintype "passive"))
    )
    (net (code "168") (name "SPI0_CS3") (class "Default")
      (node (ref "CS3") (pin "TP") (pinfunction "P$1_TP") (pintype "bidirectional"))
      (node (ref "IC2") (pin "37") (pinfunction "GPIO25_37") (pintype "bidirectional"))
      (node (ref "IC22") (pin "2") (pinfunction "~{SYNC}_2") (pintype "bidirectional"))
      (node (ref "R86") (pin "3") (pinfunction "3_3") (pintype "passive"))
      (node (ref "X1") (pin "B2") (pinfunction "2_B2") (pintype "passive"))
    )
    (net (code "169") (name "SPI0_MISO") (class "Default")
      (node (ref "IC16") (pin "2") (pinfunction "1B_2") (pintype "bidirectional"))
      (node (ref "IC16") (pin "6") (pinfunction "2B_6") (pintype "bidirectional"))
      (node (ref "IC2") (pin "6") (pinfunction "GPIO4_6") (pintype "bidirectional"))
      (node (ref "IC7") (pin "8") (pinfunction "SDO_8") (pintype "bidirectional"))
      (node (ref "IC9") (pin "8") (pinfunction "SDO_8") (pintype "bidirectional"))
      (node (ref "MISO") (pin "TP") (pinfunction "P$1_TP") (pintype "bidirectional"))
      (node (ref "X1") (pin "A7") (pinfunction "7_A7") (pintype "passive"))
      (node (ref "X1") (pin "B7") (pinfunction "7_B7") (pintype "passive"))
    )
    (net (code "170") (name "SPI0_MOSI") (class "Default")
      (node (ref "IC10") (pin "15") (pinfunction "SDI_15") (pintype "input"))
      (node (ref "IC2") (pin "5") (pinfunction "GPIO3_5") (pintype "bidirectional"))
      (node (ref "IC22") (pin "15") (pinfunction "DIN_15") (pintype "bidirectional"))
      (node (ref "IC7") (pin "9") (pinfunction "SDI_9") (pintype "bidirectional"))
      (node (ref "IC9") (pin "9") (pinfunction "SDI_9") (pintype "bidirectional"))
      (node (ref "MOSI") (pin "TP") (pinfunction "P$1_TP") (pintype "bidirectional"))
      (node (ref "X1") (pin "A6") (pinfunction "6_A6") (pintype "passive"))
      (node (ref "X1") (pin "B6") (pinfunction "6_B6") (pintype "passive"))
    )
    (net (code "171") (name "SPI0_SCK") (class "Default")
      (node (ref "IC10") (pin "16") (pinfunction "SCLK_16") (pintype "input"))
      (node (ref "IC2") (pin "4") (pinfunction "GPIO2_4") (pintype "bidirectional"))
      (node (ref "IC22") (pin "16") (pinfunction "SCLK_16") (pintype "bidirectional"))
      (node (ref "IC7") (pin "10") (pinfunction "SCK_10") (pintype "bidirectional"))
      (node (ref "IC9") (pin "10") (pinfunction "SCK_10") (pintype "bidirectional"))
      (node (ref "SCK") (pin "TP") (pinfunction "P$1_TP") (pintype "bidirectional"))
      (node (ref "X1") (pin "A5") (pinfunction "5_A5") (pintype "passive"))
      (node (ref "X1") (pin "B5") (pinfunction "5_B5") (pintype "passive"))
    )
    (net (code "172") (name "SPI1_CS") (class "Default")
      (node (ref "IC2") (pin "16") (pinfunction "GPIO13_16") (pintype "bidirectional"))
      (node (ref "X1") (pin "A29") (pinfunction "29_A29") (pintype "passive"))
      (node (ref "X1") (pin "B29") (pinfunction "29_B29") (pintype "passive"))
    )
    (net (code "173") (name "SPI1_MISO") (class "Default")
      (node (ref "IC2") (pin "15") (pinfunction "GPIO12_15") (pintype "bidirectional"))
      (node (ref "X1") (pin "A26") (pinfunction "26_A26") (pintype "passive"))
      (node (ref "X1") (pin "B26") (pinfunction "26_B26") (pintype "passive"))
    )
    (net (code "174") (name "SPI1_MOSI") (class "Default")
      (node (ref "IC2") (pin "14") (pinfunction "GPIO11_14") (pintype "bidirectional"))
      (node (ref "X1") (pin "A27") (pinfunction "27_A27") (pintype "passive"))
      (node (ref "X1") (pin "B27") (pinfunction "27_B27") (pintype "passive"))
    )
    (net (code "175") (name "SPI1_SCK") (class "Default")
      (node (ref "IC2") (pin "13") (pinfunction "GPIO10_13") (pintype "bidirectional"))
      (node (ref "X1") (pin "A28") (pinfunction "28_A28") (pintype "passive"))
      (node (ref "X1") (pin "B28") (pinfunction "28_B28") (pintype "passive"))
    )
    (net (code "176") (name "SWCLK") (class "Default")
      (node (ref "DBG2") (pin "1") (pinfunction "P$1_1") (pintype "bidirectional"))
      (node (ref "IC2") (pin "24") (pinfunction "SWCLK_24") (pintype "bidirectional"))
      (node (ref "X1") (pin "B23") (pinfunction "23_B23") (pintype "passive"))
    )
    (net (code "177") (name "SWDIO") (class "Default")
      (node (ref "DBG2") (pin "3") (pinfunction "P$3_3") (pintype "bidirectional"))
      (node (ref "IC2") (pin "25") (pinfunction "SWDIO_25") (pintype "bidirectional"))
      (node (ref "X1") (pin "B24") (pinfunction "24_B24") (pintype "passive"))
    )
    (net (code "178") (name "UART0_RX") (class "Default")
      (node (ref "DBG1") (pin "1") (pinfunction "P$1_1") (pintype "bidirectional"))
      (node (ref "IC2") (pin "2") (pinfunction "GPIO0_2") (pintype "bidirectional"))
      (node (ref "X1") (pin "B20") (pinfunction "20_B20") (pintype "passive"))
    )
    (net (code "179") (name "UART0_TX") (class "Default")
      (node (ref "DBG1") (pin "3") (pinfunction "P$3_3") (pintype "bidirectional"))
      (node (ref "IC2") (pin "3") (pinfunction "GPIO1_3") (pintype "bidirectional"))
      (node (ref "X1") (pin "B21") (pinfunction "21_B21") (pintype "passive"))
    )
    (net (code "180") (name "USBD_N") (class "Default")
      (node (ref "ESD1") (pin "3") (pinfunction "C2_3") (pintype "bidirectional"))
      (node (ref "R13") (pin "1") (pinfunction "1_1") (pintype "passive"))
      (node (ref "USBC") (pin "A7") (pinfunction "D-1_A7") (pintype "passive"))
      (node (ref "USBC") (pin "B7") (pinfunction "D-2_B7") (pintype "passive"))
    )
    (net (code "181") (name "USBD_P") (class "Default")
      (node (ref "ESD1") (pin "2") (pinfunction "C1_2") (pintype "bidirectional"))
      (node (ref "R39") (pin "1") (pinfunction "1_1") (pintype "passive"))
      (node (ref "USBC") (pin "A6") (pinfunction "D+1_A6") (pintype "passive"))
      (node (ref "USBC") (pin "B6") (pinfunction "D+2_B6") (pintype "passive"))
    )
    (net (code "182") (name "USB_BOOT") (class "Default")
      (node (ref "R11") (pin "1") (pinfunction "1_1") (pintype "passive"))
      (node (ref "USB_BOOT") (pin "1") (pinfunction "P_1") (pintype "passive"))
    )
    (net (code "183") (name "USB_SHIELD") (class "Default")
      (node (ref "C115") (pin "1") (pinfunction "1_1") (pintype "passive"))
      (node (ref "R68") (pin "1") (pinfunction "1_1") (pintype "passive"))
      (node (ref "USBC") (pin "S1") (pinfunction "SHIELD_S1") (pintype "passive"))
      (node (ref "USBC") (pin "S2") (pinfunction "SHIELD_S2") (pintype "passive"))
      (node (ref "USBC") (pin "S3") (pinfunction "SHIELD_S3") (pintype "passive"))
      (node (ref "USBC") (pin "S4") (pinfunction "SHIELD_S4") (pintype "passive"))
    )
    (net (code "184") (name "VBUS") (class "Default")
      (node (ref "C78") (pin "1") (pinfunction "1_1") (pintype "passive"))
      (node (ref "C79") (pin "1") (pinfunction "1_1") (pintype "passive"))
      (node (ref "D1") (pin "A") (pinfunction "A_A") (pintype "passive"))
      (node (ref "ESD1") (pin "4") (pinfunction "C3_4") (pintype "bidirectional"))
      (node (ref "R12") (pin "1") (pinfunction "1_1") (pintype "passive"))
      (node (ref "R63") (pin "1") (pinfunction "1_1") (pintype "passive"))
      (node (ref "USBC") (pin "A4") (pinfunction "VBUS_A4") (pintype "passive"))
      (node (ref "USBC") (pin "A9") (pinfunction "VBUS1_A9") (pintype "passive"))
      (node (ref "USBC") (pin "B4") (pinfunction "VBUS3_B4") (pintype "passive"))
      (node (ref "USBC") (pin "B9") (pinfunction "VBUS2_B9") (pintype "passive"))
      (node (ref "VBUS") (pin "TP") (pinfunction "P$1_TP") (pintype "bidirectional"))
    )
    (net (code "185") (name "VFB_12VN") (class "Default")
      (node (ref "C106") (pin "2") (pinfunction "2_2") (pintype "passive"))
      (node (ref "IC15") (pin "7") (pinfunction "FBN_7") (pintype "input"))
      (node (ref "R56") (pin "1") (pinfunction "1_1") (pintype "passive"))
      (node (ref "R76") (pin "1") (pinfunction "1_1") (pintype "passive"))
      (node (ref "VFB12VN") (pin "TP") (pinfunction "P$1_TP") (pintype "bidirectional"))
    )
    (net (code "186") (name "VFB_12VP") (class "Default")
      (node (ref "C107") (pin "1") (pinfunction "1_1") (pintype "passive"))
      (node (ref "IC15") (pin "9") (pinfunction "FBP_9") (pintype "input"))
      (node (ref "R55") (pin "1") (pinfunction "1_1") (pintype "passive"))
      (node (ref "R73") (pin "1") (pinfunction "1_1") (pintype "passive"))
      (node (ref "VFB12VP") (pin "TP") (pinfunction "P$1_TP") (pintype "bidirectional"))
    )
    (net (code "187") (name "VFB_14VN") (class "Default")
      (node (ref "C101") (pin "2") (pinfunction "2_2") (pintype "passive"))
      (node (ref "IC14") (pin "16") (pinfunction "FBN_16") (pintype "input"))
      (node (ref "R54") (pin "1") (pinfunction "1_1") (pintype "passive"))
      (node (ref "R59") (pin "1") (pinfunction "1_1") (pintype "passive"))
      (node (ref "TP_VFB_14VN") (pin "TP") (pinfunction "P$1_TP") (pintype "bidirectional"))
    )
    (net (code "188") (name "VFB_14VP") (class "Default")
      (node (ref "C100") (pin "2") (pinfunction "2_2") (pintype "passive"))
      (node (ref "IC14") (pin "22") (pinfunction "FBP_22") (pintype "input"))
      (node (ref "R53") (pin "1") (pinfunction "1_1") (pintype "passive"))
      (node (ref "R57") (pin "1") (pinfunction "1_1") (pintype "passive"))
      (node (ref "TP_VFB_14VP") (pin "TP") (pinfunction "P$1_TP") (pintype "bidirectional"))
    )
    (net (code "189") (name "VOCM_A") (class "Default")
      (node (ref "IC7") (pin "21") (pinfunction "VOCM_21") (pintype "output"))
      (node (ref "R51") (pin "2") (pinfunction "2_2") (pintype "passive"))
      (node (ref "VOCMA") (pin "TP") (pinfunction "P$1_TP") (pintype "bidirectional"))
    )
    (net (code "190") (name "VOCM_B") (class "Default")
      (node (ref "IC9") (pin "21") (pinfunction "VOCM_21") (pintype "output"))
      (node (ref "R52") (pin "1") (pinfunction "1_1") (pintype "passive"))
      (node (ref "VCOMB") (pin "TP") (pinfunction "P$1_TP") (pintype "bidirectional"))
    )
    (net (code "191") (name "VREF_ADC") (class "Default")
      (node (ref "C46") (pin "1") (pinfunction "1_1") (pintype "passive"))
      (node (ref "C72") (pin "1") (pinfunction "1_1") (pintype "passive"))
      (node (ref "C73") (pin "1") (pinfunction "1_1") (pintype "passive"))
      (node (ref "IC13") (pin "1") (pinfunction "OUT_1") (pintype "output"))
      (node (ref "IC13") (pin "4") (pinfunction "-IN_4") (pintype "input"))
      (node (ref "IC7") (pin "23") (pinfunction "AVDD_23") (pintype "power_in"))
      (node (ref "IC9") (pin "23") (pinfunction "AVDD_23") (pintype "power_in"))
      (node (ref "R49") (pin "3") (pinfunction "3_3") (pintype "passive"))
      (node (ref "VREF") (pin "TP") (pinfunction "P$1_TP") (pintype "bidirectional"))
    )
    (net (code "192") (name "VREF_ADC_RAW") (class "Default")
      (node (ref "C48") (pin "1") (pinfunction "1_1") (pintype "passive"))
      (node (ref "IC12") (pin "2") (pinfunction "VREF_2") (pintype "bidirectional"))
      (node (ref "IC13") (pin "3") (pinfunction "+IN_3") (pintype "input"))
      (node (ref "VREFR") (pin "TP") (pinfunction "P$1_TP") (pintype "bidirectional"))
    )
    (net (code "193") (name "VREF_ADC{slash}2") (class "Default")
      (node (ref "C75") (pin "1") (pinfunction "1_1") (pintype "passive"))
      (node (ref "IC11") (pin "1") (pinfunction "OUT_1") (pintype "output"))
      (node (ref "IC11") (pin "4") (pinfunction "-IN_4") (pintype "input"))
      (node (ref "R51") (pin "1") (pinfunction "1_1") (pintype "passive"))
      (node (ref "R52") (pin "2") (pinfunction "2_2") (pintype "passive"))
      (node (ref "REF/2") (pin "TP") (pinfunction "P$1_TP") (pintype "bidirectional"))
    )
    (net (code "194") (name "VREF_DAC") (class "Default")
      (node (ref "C125") (pin "1") (pinfunction "1_1") (pintype "passive"))
      (node (ref "IC23") (pin "1") (pinfunction "OUT_1") (pintype "output"))
      (node (ref "IC23") (pin "4") (pinfunction "-IN_4") (pintype "input"))
      (node (ref "R100") (pin "1") (pinfunction "1_1") (pintype "passive"))
      (node (ref "R104") (pin "1") (pinfunction "1_1") (pintype "passive"))
      (node (ref "R108") (pin "1") (pinfunction "1_1") (pintype "passive"))
      (node (ref "R112") (pin "1") (pinfunction "1_1") (pintype "passive"))
      (node (ref "R116") (pin "1") (pinfunction "1_1") (pintype "passive"))
      (node (ref "R88") (pin "1") (pinfunction "1_1") (pintype "passive"))
      (node (ref "R92") (pin "1") (pinfunction "1_1") (pintype "passive"))
      (node (ref "R96") (pin "1") (pinfunction "1_1") (pintype "passive"))
    )
    (net (code "195") (name "VREF_DAC_OUT") (class "Default")
      (node (ref "C124") (pin "1") (pinfunction "1_1") (pintype "passive"))
      (node (ref "IC22") (pin "8") (pinfunction "VREF_IO_8") (pintype "power_in"))
      (node (ref "IC23") (pin "3") (pinfunction "+IN_3") (pintype "input"))
      (node (ref "VREF_DAC") (pin "TP") (pinfunction "P$1_TP") (pintype "bidirectional"))
    )
    (net (code "196") (name "VREF_TPS") (class "Default")
      (node (ref "C99") (pin "2") (pinfunction "2_2") (pintype "passive"))
      (node (ref "IC14") (pin "17") (pinfunction "VREF_17") (pintype "input"))
      (node (ref "R58") (pin "1") (pinfunction "1_1") (pintype "passive"))
      (node (ref "TP_VREF_TPS") (pin "TP") (pinfunction "P$1_TP") (pintype "bidirectional"))
    )
    (net (code "197") (name "unconnected-(IC1-NC-Pad4)") (class "Default")
      (node (ref "IC1") (pin "4") (pinfunction "NC_4") (pintype "bidirectional"))
    )
    (net (code "198") (name "unconnected-(IC7-GPIO3-Pad15)") (class "Default")
      (node (ref "IC7") (pin "15") (pinfunction "GPIO3_15") (pintype "bidirectional"))
    )
    (net (code "199") (name "unconnected-(IC7-GPIO4-Pad14)") (class "Default")
      (node (ref "IC7") (pin "14") (pinfunction "GPIO4_14") (pintype "bidirectional"))
    )
    (net (code "200") (name "unconnected-(IC7-GPIO5-Pad13)") (class "Default")
      (node (ref "IC7") (pin "13") (pinfunction "GPIO5_13") (pintype "bidirectional"))
    )
    (net (code "201") (name "unconnected-(IC7-GPIO6-Pad12)") (class "Default")
      (node (ref "IC7") (pin "12") (pinfunction "GPIO6_12") (pintype "bidirectional"))
    )
    (net (code "202") (name "unconnected-(IC9-GPIO3-Pad15)") (class "Default")
      (node (ref "IC9") (pin "15") (pinfunction "GPIO3_15") (pintype "bidirectional"))
    )
    (net (code "203") (name "unconnected-(IC9-GPIO4-Pad14)") (class "Default")
      (node (ref "IC9") (pin "14") (pinfunction "GPIO4_14") (pintype "bidirectional"))
    )
    (net (code "204") (name "unconnected-(IC9-GPIO5-Pad13)") (class "Default")
      (node (ref "IC9") (pin "13") (pinfunction "GPIO5_13") (pintype "bidirectional"))
    )
    (net (code "205") (name "unconnected-(IC9-GPIO6-Pad12)") (class "Default")
      (node (ref "IC9") (pin "12") (pinfunction "GPIO6_12") (pintype "bidirectional"))
    )
    (net (code "206") (name "unconnected-(R86-Pad1)") (class "Default")
      (node (ref "R86") (pin "1") (pinfunction "1_1") (pintype "passive"))
    )
    (net (code "207") (name "unconnected-(USBC-SBU1-PadA8)") (class "Default")
      (node (ref "USBC") (pin "A8") (pinfunction "SBU1_A8") (pintype "passive"))
    )
    (net (code "208") (name "unconnected-(USBC-SBU2-PadB8)") (class "Default")
      (node (ref "USBC") (pin "B8") (pinfunction "SBU2_B8") (pintype "passive"))
    )
    (net (code "209") (name "unconnected-(X1B-3-PadB3)") (class "Default")
      (node (ref "X1") (pin "B3") (pinfunction "3_B3") (pintype "passive"))
    )
    (net (code "210") (name "unconnected-(X1B-4-PadB4)") (class "Default")
      (node (ref "X1") (pin "B4") (pinfunction "4_B4") (pintype "passive"))
    )
    (net (code "211") (name "unconnected-(X1B-11-PadB11)") (class "Default")
      (node (ref "X1") (pin "B11") (pinfunction "11_B11") (pintype "passive"))
    )
    (net (code "212") (name "unconnected-(X1B-17-PadB17)") (class "Default")
      (node (ref "X1") (pin "B17") (pinfunction "17_B17") (pintype "passive"))
    )
    (net (code "213") (name "~{ADC_RST}") (class "Default")
      (node (ref "IC10") (pin "26") (pinfunction "~{PD}/~{RST}_26") (pintype "input"))
      (node (ref "IC2") (pin "12") (pinfunction "GPIO9_12") (pintype "bidirectional"))
      (node (ref "R16") (pin "2") (pinfunction "2_2") (pintype "passive"))
      (node (ref "X1") (pin "A12") (pinfunction "12_A12") (pintype "passive"))
    )
    (net (code "214") (name "~{QSPI_SS}") (class "Default")
      (node (ref "IC2") (pin "56") (pinfunction "QSPI_SS_N_56") (pintype "bidirectional"))
      (node (ref "IC4") (pin "1") (pinfunction "~{CS}_1") (pintype "bidirectional"))
      (node (ref "R11") (pin "2") (pinfunction "2_2") (pintype "passive"))
      (node (ref "R18") (pin "1") (pinfunction "1_1") (pintype "passive"))
    )
  )
)
